# BeagleBone_Blue.net
KiCad netlist of a schematic drawn in EAGLE
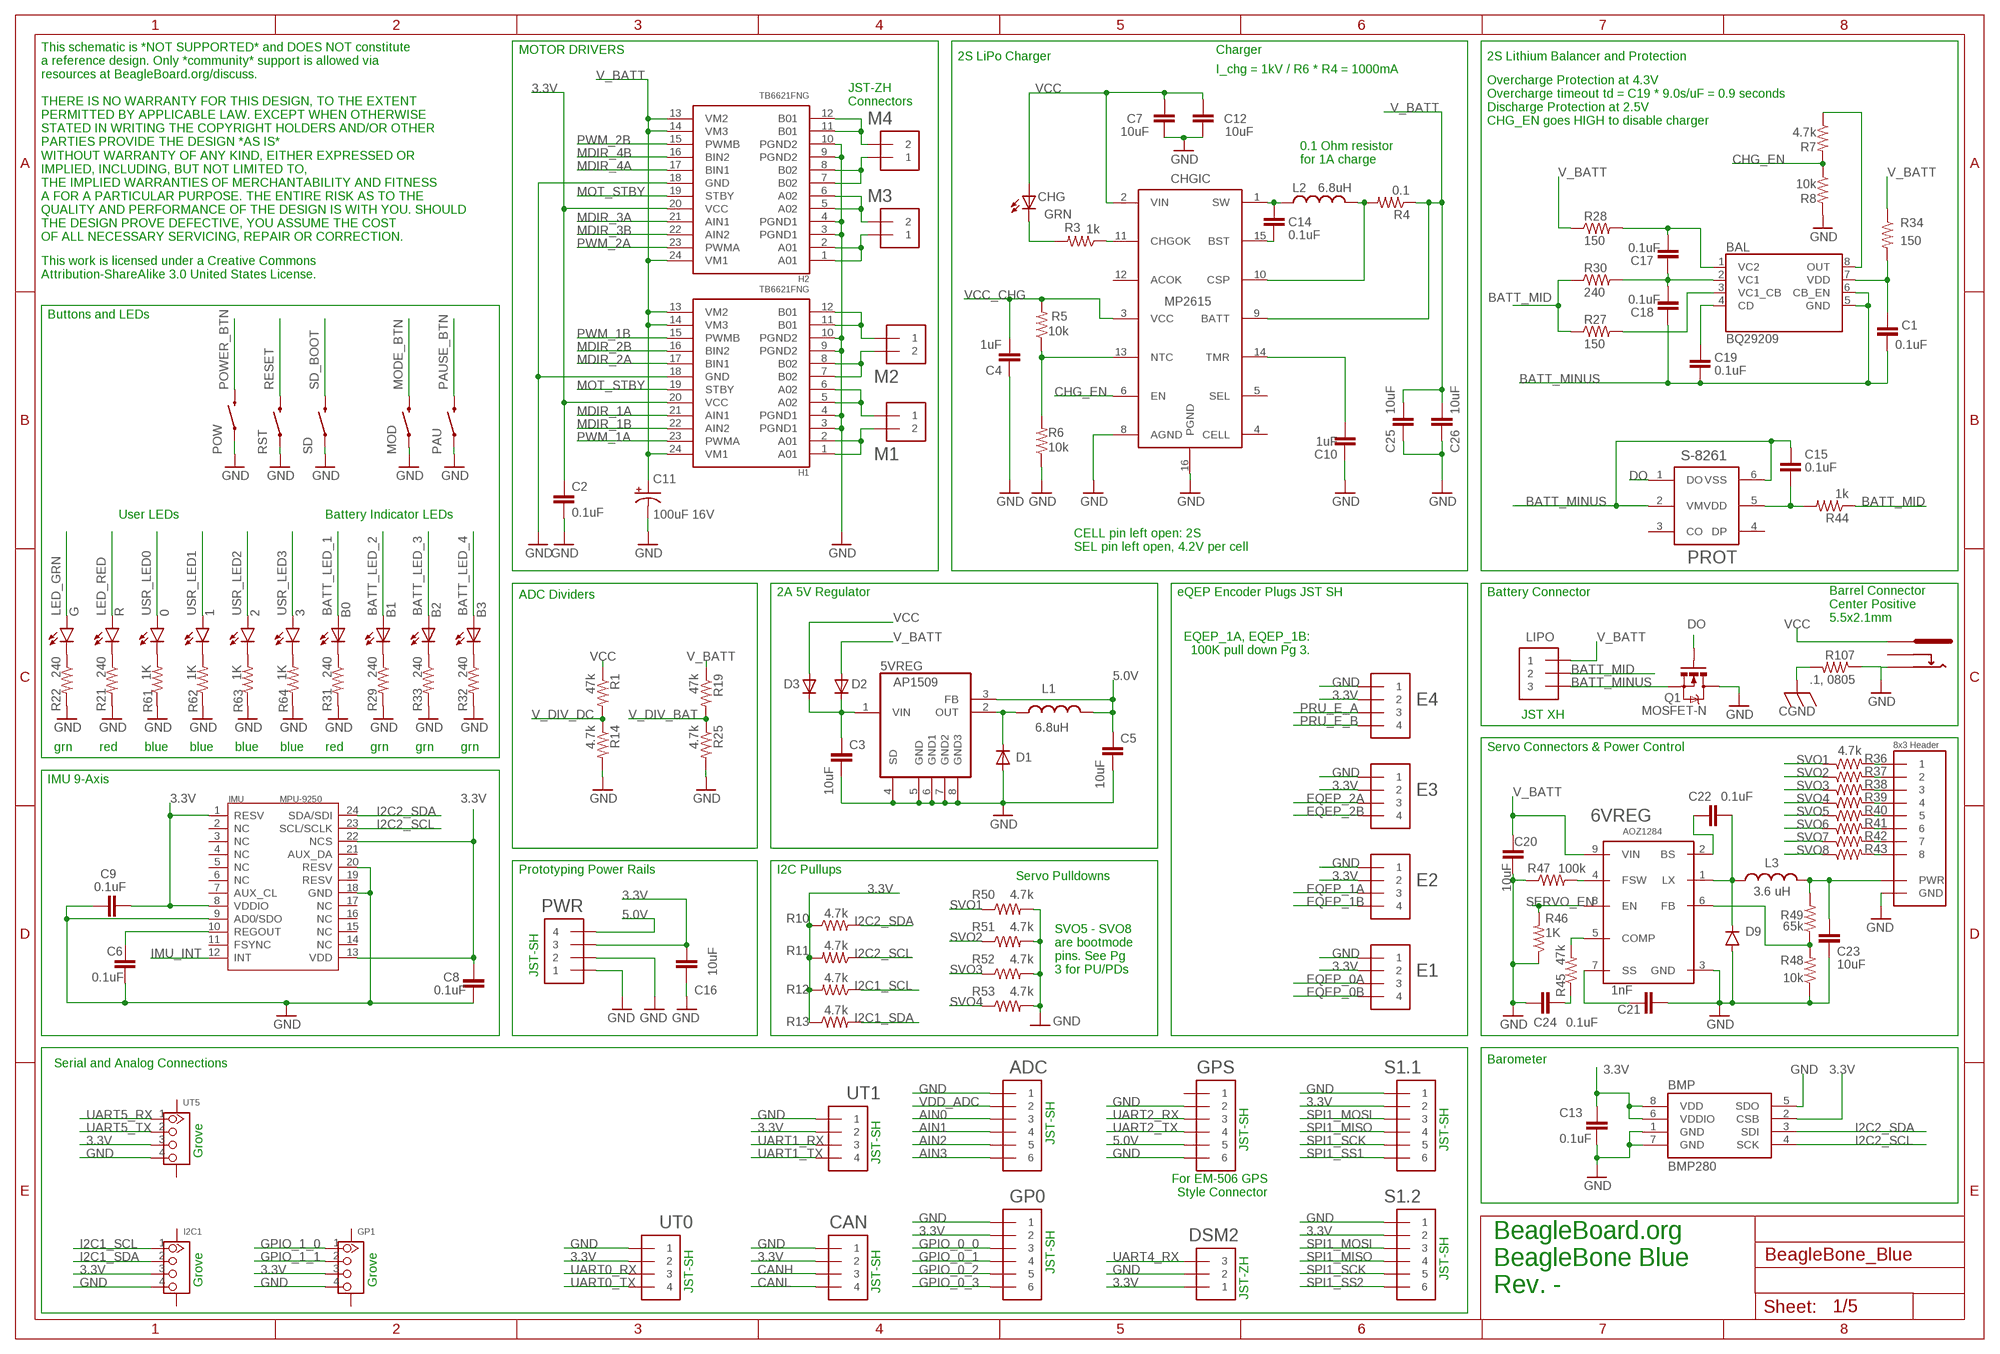
[diagram p0: schematic, sheet 1]
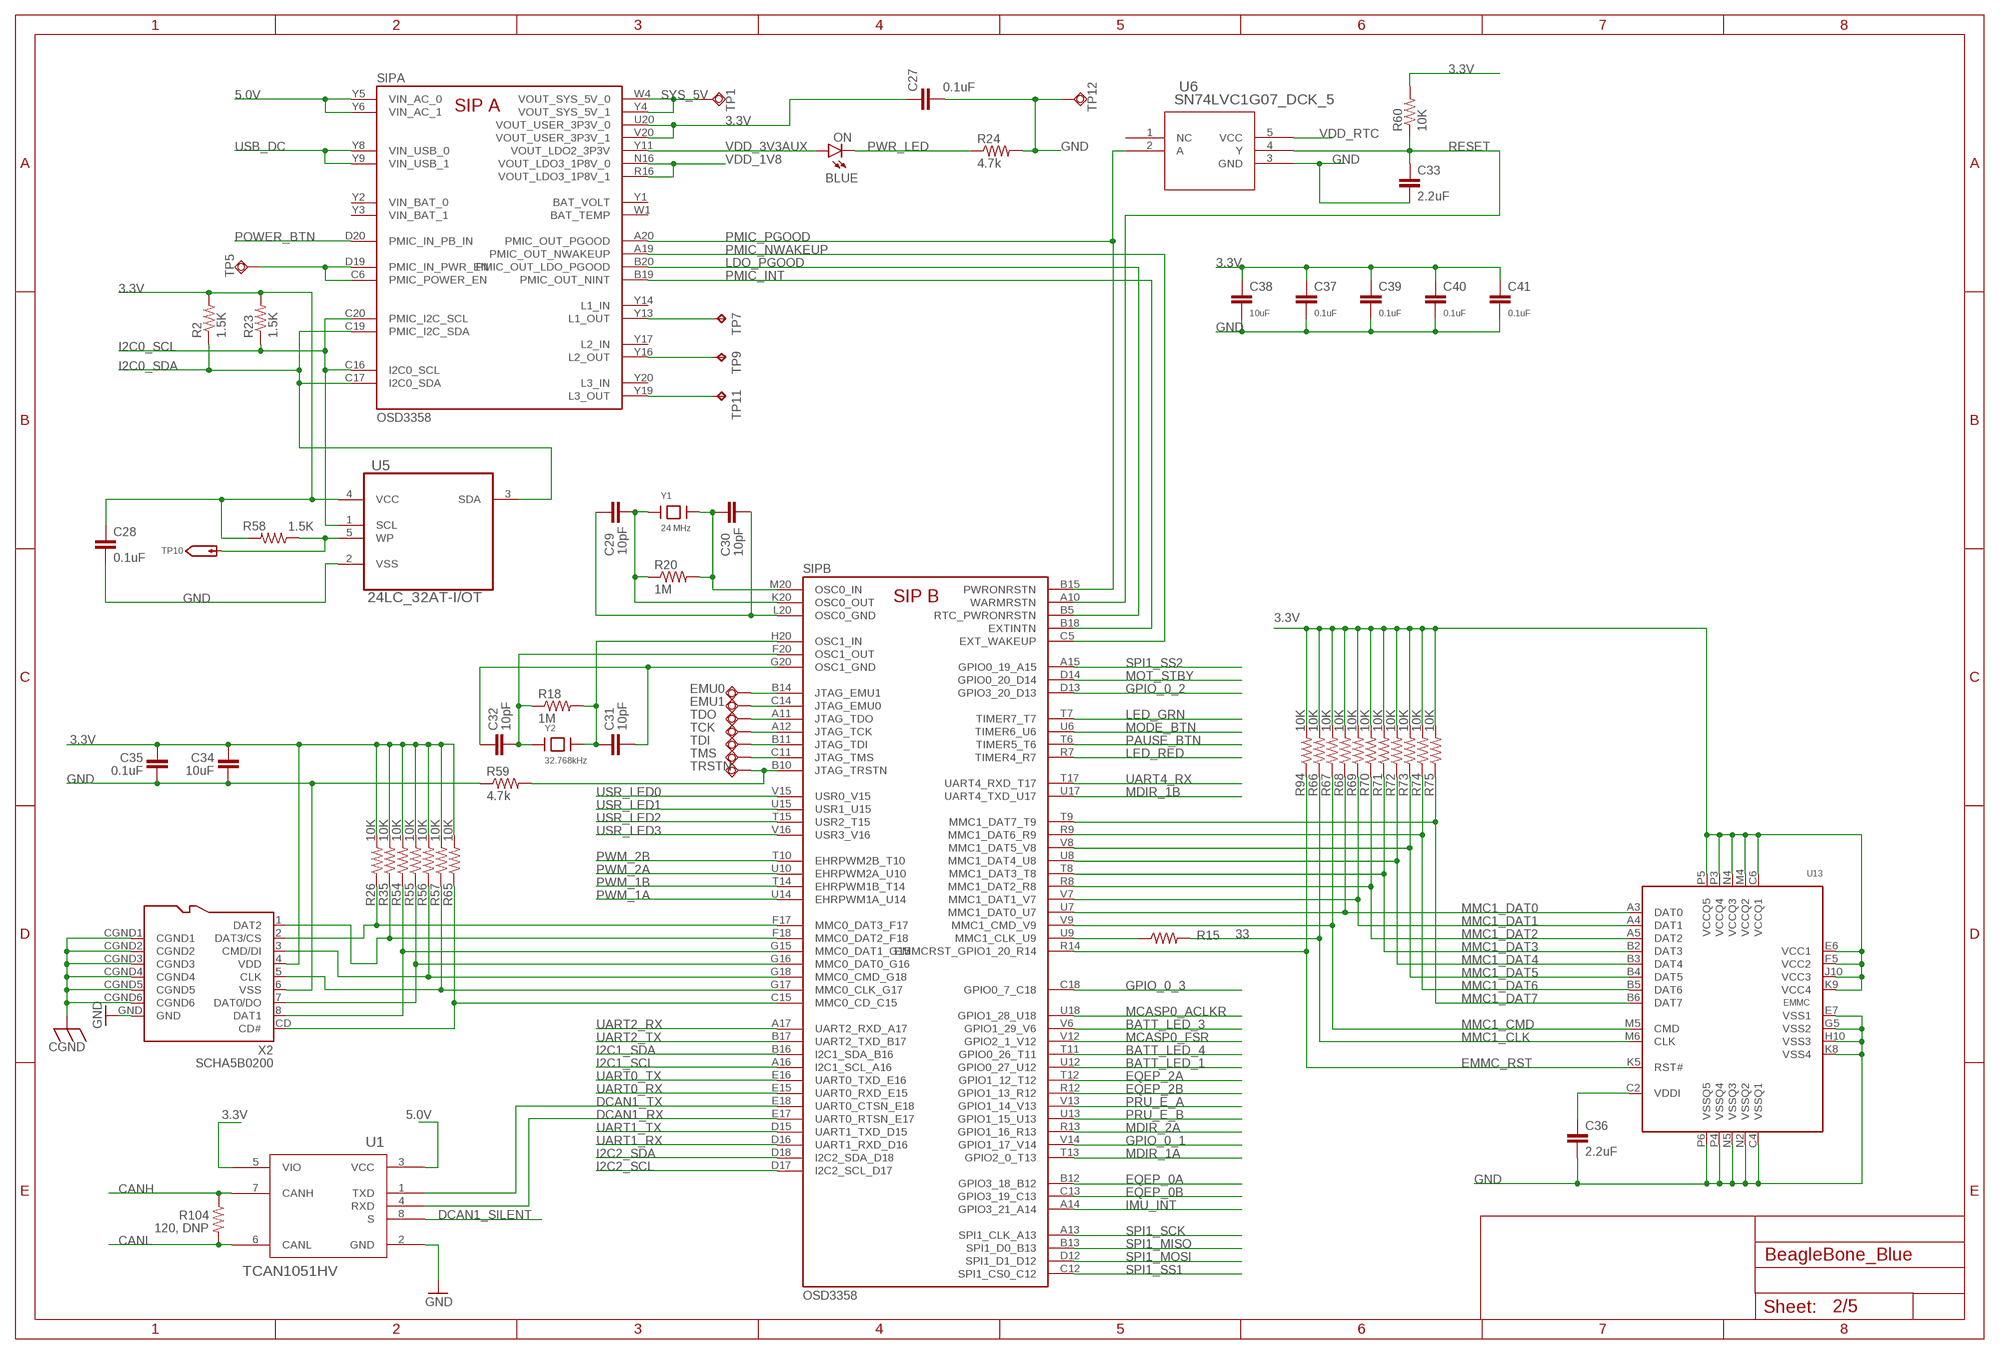
[diagram p1: schematic, sheet 2]
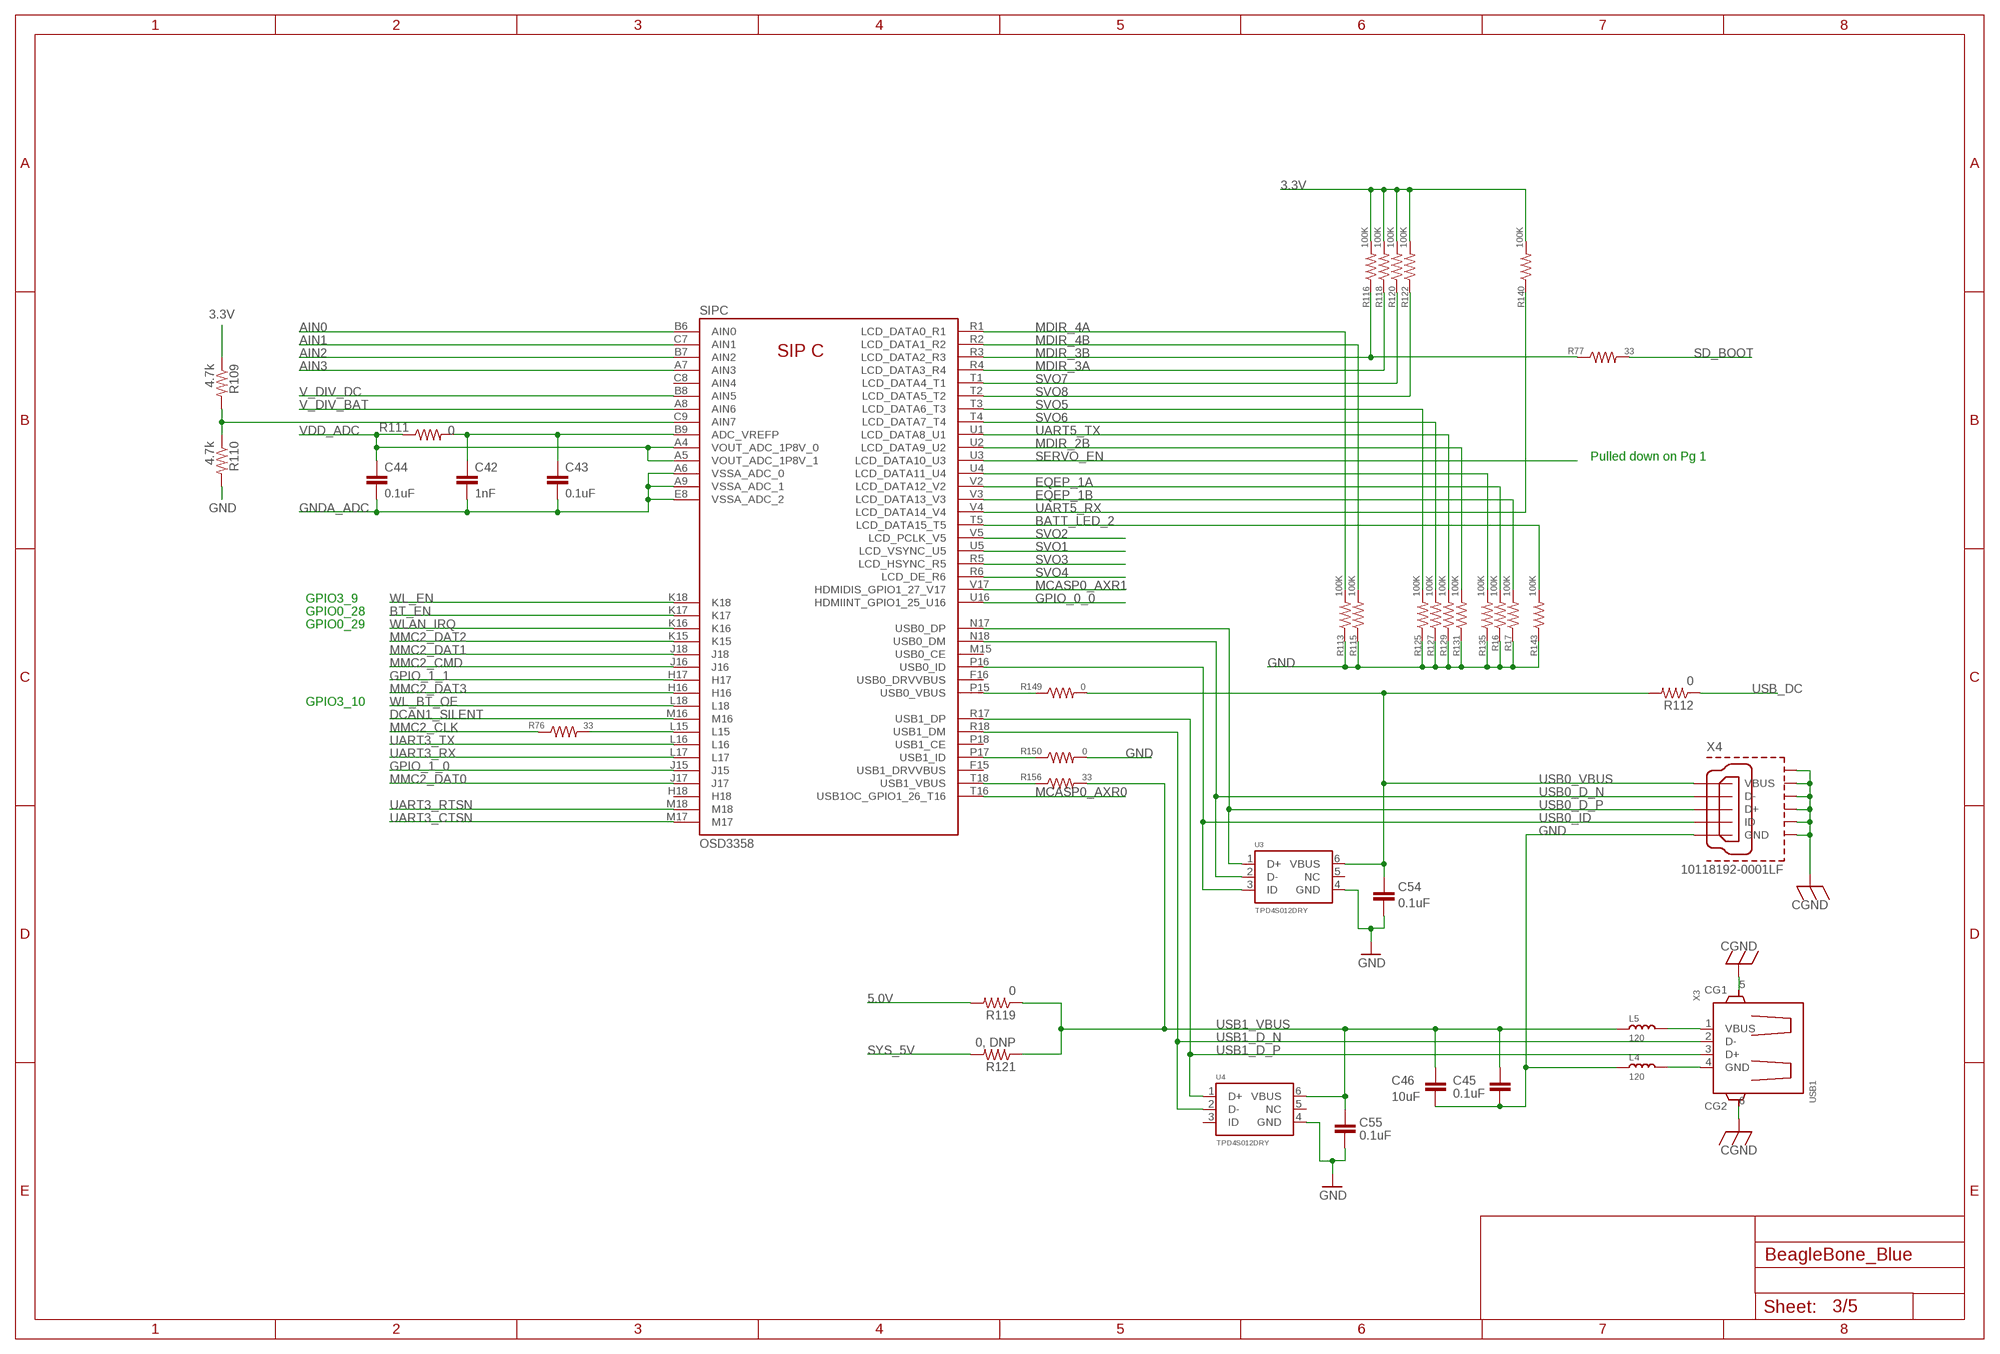
[diagram p2: schematic, sheet 3]
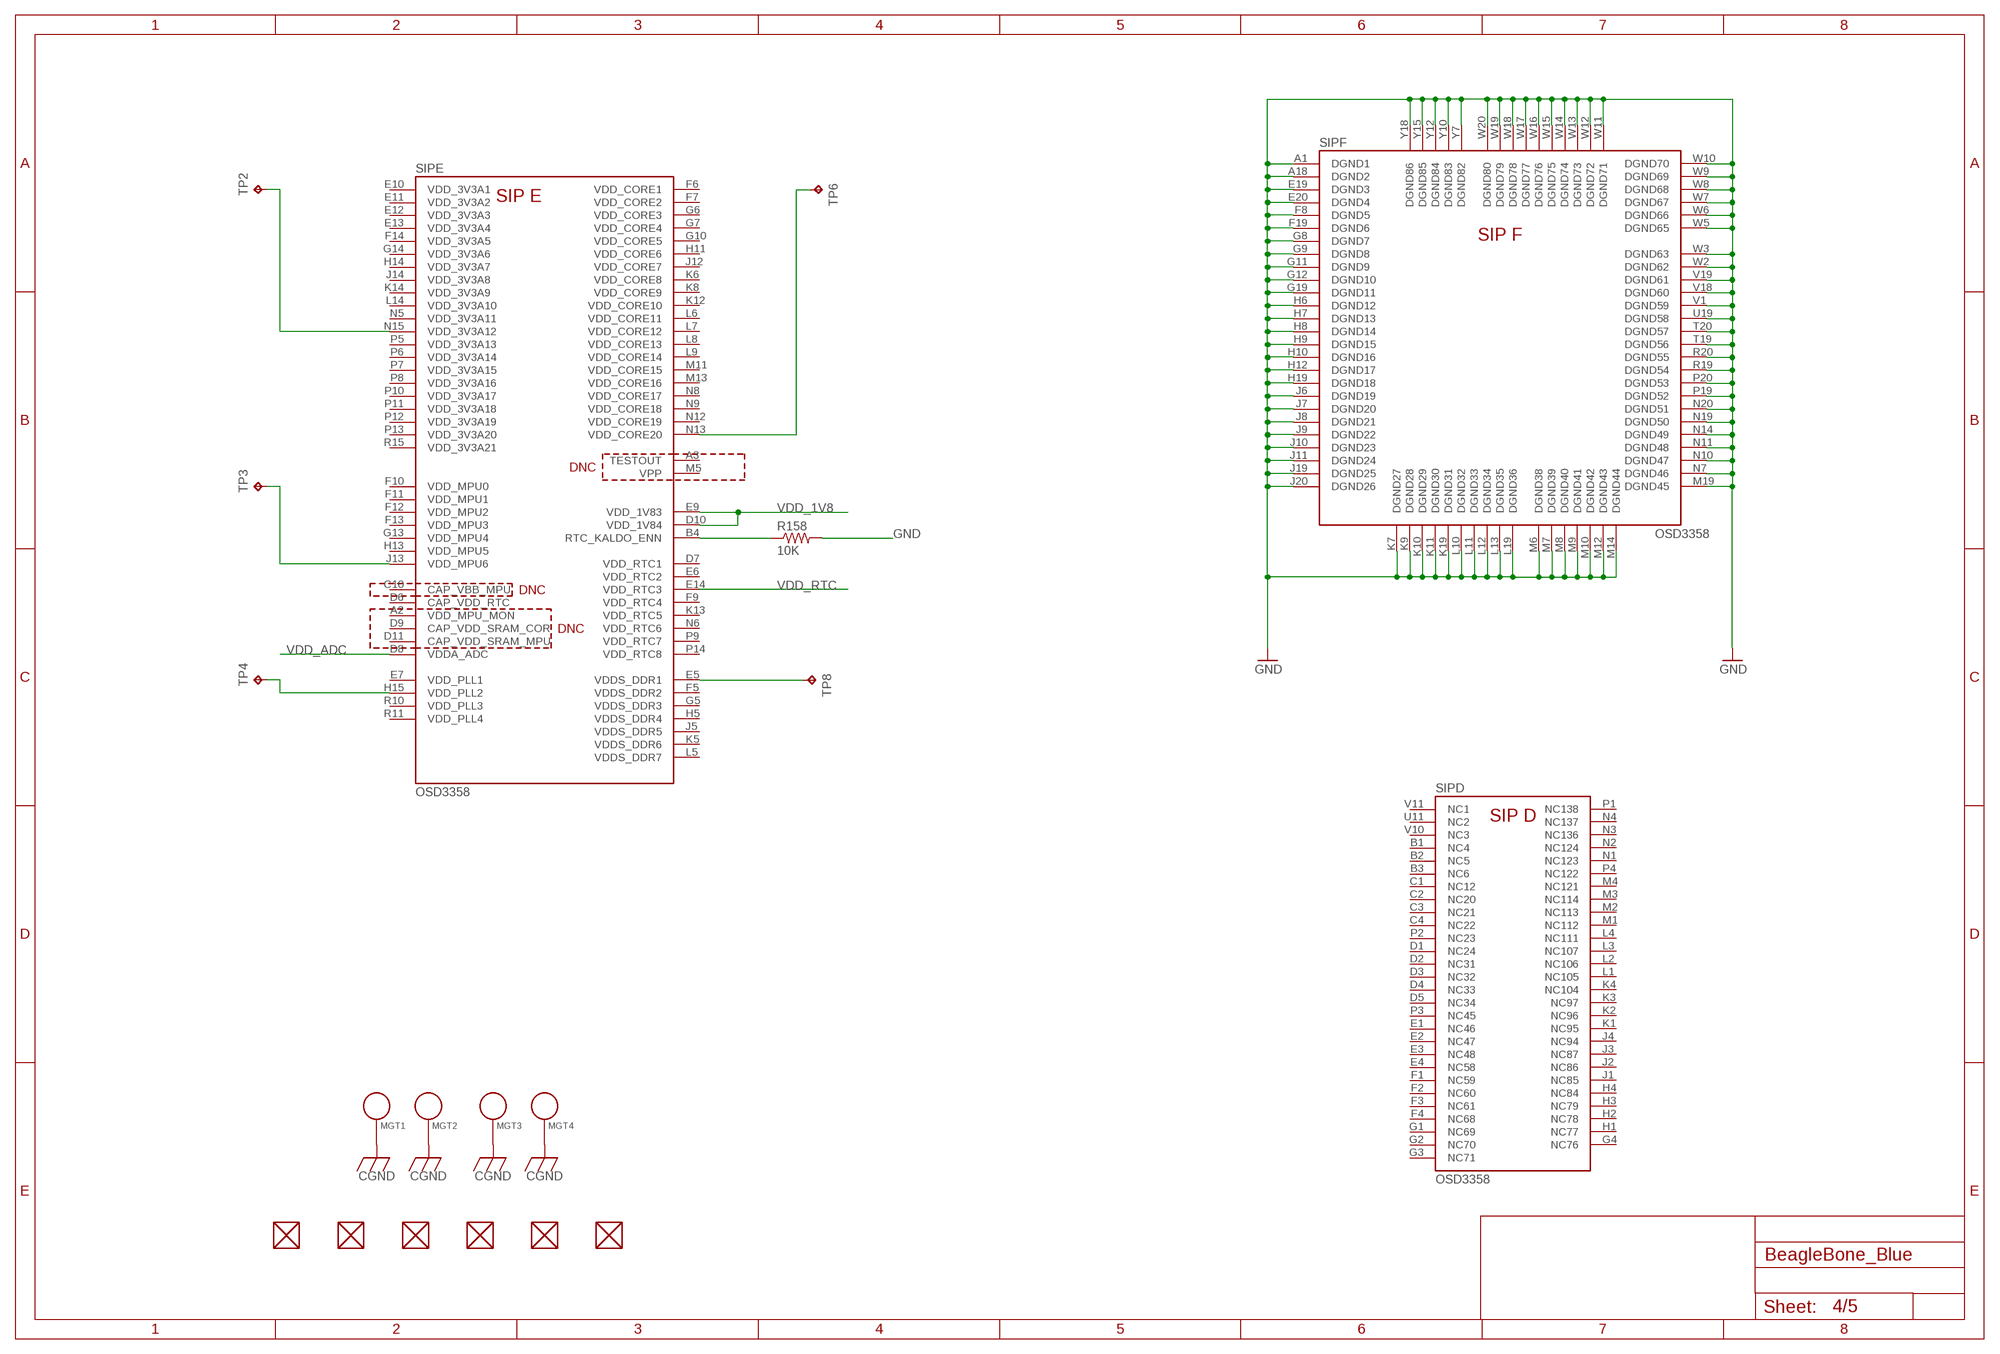
[diagram p3: schematic, sheet 4]
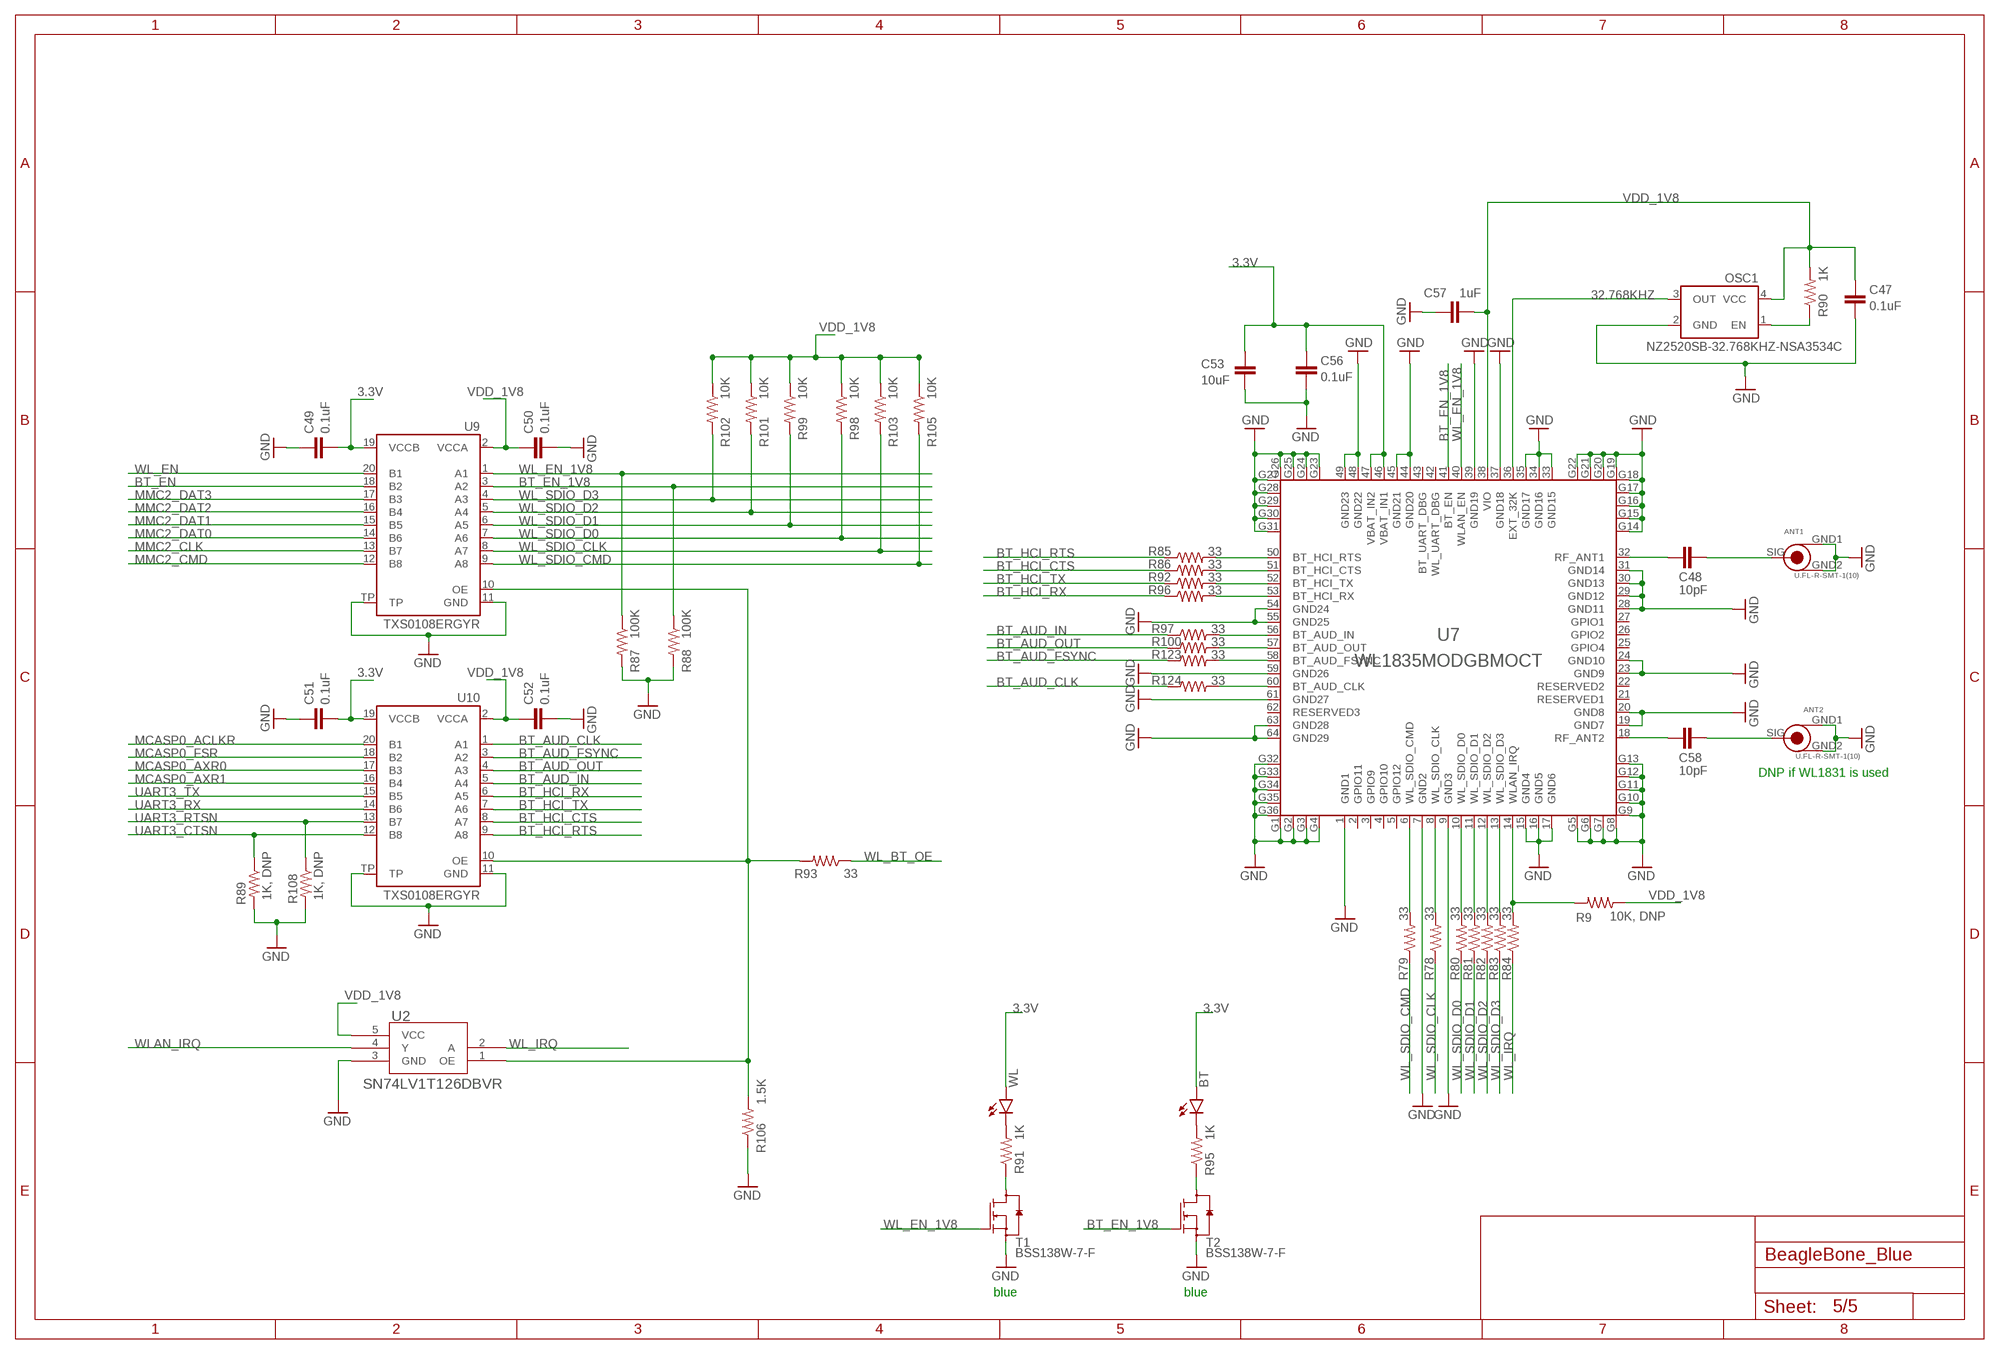
[diagram p4: schematic, sheet 5]

(export (version "E")
  (design (tool "Eeschema 10.0.6"))
  (components
    (comp (ref "0")
      (value "BLUE")
      (footprint "eagle-import:LED-0603")
      (libsource (lib "eagle-import") (part "LED0603"))
    )
    (comp (ref "1")
      (value "BLUE")
      (footprint "eagle-import:LED-0603")
      (libsource (lib "eagle-import") (part "LED0603"))
    )
    (comp (ref "2")
      (value "BLUE")
      (footprint "eagle-import:LED-0603")
      (libsource (lib "eagle-import") (part "LED0603"))
    )
    (comp (ref "3")
      (value "BLUE")
      (footprint "eagle-import:LED-0603")
      (libsource (lib "eagle-import") (part "LED0603"))
    )
    (comp (ref "5VREG")
      (value "AP1509SOIC-8-TIGHT")
      (footprint "eagle-import:SO08-TIGHT")
      (libsource (lib "eagle-import") (part "AP1509SOIC-8-TIGHT"))
    )
    (comp (ref "6VREG")
      (value "AOZ1284")
      (footprint "eagle-import:SO08-EXPOSED")
      (libsource (lib "eagle-import") (part "AOZ1284"))
    )
    (comp (ref "12V")
      (value "PJ-102B_POWER_CON")
      (footprint "eagle-import:PJ-102B_POWER_CON")
      (libsource (lib "eagle-import") (part "PJ-102B_POWER_CON"))
    )
    (comp (ref "ADC")
      (value "JST_SH_6")
      (footprint "eagle-import:JST_SH_6")
      (libsource (lib "eagle-import") (part "JST_SH_6"))
    )
    (comp (ref "B0")
      (value "RED")
      (footprint "eagle-import:LED-0603")
      (libsource (lib "eagle-import") (part "SparkFun-LED_LED0603"))
    )
    (comp (ref "B1")
      (value "GREEN")
      (footprint "eagle-import:LED-0603")
      (libsource (lib "eagle-import") (part "SparkFun-LED_LED0603"))
    )
    (comp (ref "B2")
      (value "GREEN")
      (footprint "eagle-import:LED-0603")
      (libsource (lib "eagle-import") (part "SparkFun-LED_LED0603"))
    )
    (comp (ref "B3")
      (value "GREEN")
      (footprint "eagle-import:LED-0603")
      (libsource (lib "eagle-import") (part "SparkFun-LED_LED0603"))
    )
    (comp (ref "BAL")
      (value "BQ29209")
      (footprint "eagle-import:8-SON_3X3MM")
      (libsource (lib "eagle-import") (part "BQ29209"))
    )
    (comp (ref "BMP")
      (value "BMP280")
      (footprint "eagle-import:BMP280")
      (libsource (lib "eagle-import") (part "BMP280"))
    )
    (comp (ref "C1")
      (value "0.1uF")
      (footprint "eagle-import:0402-CAP")
      (libsource (lib "eagle-import") (part "Strawson_Eagle_Lib_CAP0402-CAP"))
    )
    (comp (ref "C2")
      (value "0.1uF")
      (footprint "eagle-import:0402-CAP")
      (libsource (lib "eagle-import") (part "Strawson_Eagle_Lib_CAP0402-CAP"))
    )
    (comp (ref "C3")
      (value "10uF")
      (footprint "eagle-import:0805")
      (libsource (lib "eagle-import") (part "CAP0805"))
    )
    (comp (ref "C4")
      (value "1uF")
      (footprint "eagle-import:0402-CAP")
      (libsource (lib "eagle-import") (part "Strawson_Eagle_Lib_CAP0402-CAP"))
    )
    (comp (ref "C5")
      (value "10uF")
      (footprint "eagle-import:0805")
      (libsource (lib "eagle-import") (part "CAP0805"))
    )
    (comp (ref "C6")
      (value "0.1uF")
      (footprint "eagle-import:0402-CAP")
      (libsource (lib "eagle-import") (part "Strawson_Eagle_Lib_CAP0402-CAP"))
    )
    (comp (ref "C7")
      (value "10uF")
      (footprint "eagle-import:0805")
      (libsource (lib "eagle-import") (part "CAP0805"))
    )
    (comp (ref "C8")
      (value "0.1uF")
      (footprint "eagle-import:0402-CAP")
      (libsource (lib "eagle-import") (part "Strawson_Eagle_Lib_CAP0402-CAP"))
    )
    (comp (ref "C9")
      (value "0.1uF")
      (footprint "eagle-import:0402-CAP")
      (libsource (lib "eagle-import") (part "Strawson_Eagle_Lib_CAP0402-CAP"))
    )
    (comp (ref "C10")
      (value "1uF")
      (footprint "eagle-import:0402-CAP")
      (libsource (lib "eagle-import") (part "Strawson_Eagle_Lib_CAP0402-CAP"))
    )
    (comp (ref "C11")
      (value "100uF 16V")
      (footprint "eagle-import:PANASONIC_D")
      (libsource (lib "eagle-import") (part "CPOL-USD"))
    )
    (comp (ref "C12")
      (value "10uF")
      (footprint "eagle-import:0805")
      (libsource (lib "eagle-import") (part "CAP0805"))
    )
    (comp (ref "C13")
      (value "0.1uF")
      (footprint "eagle-import:0402-CAP")
      (libsource (lib "eagle-import") (part "Strawson_Eagle_Lib_CAP0402-CAP"))
    )
    (comp (ref "C14")
      (value "0.1uF")
      (footprint "eagle-import:0402-CAP")
      (libsource (lib "eagle-import") (part "Strawson_Eagle_Lib_CAP0402-CAP"))
    )
    (comp (ref "C15")
      (value "0.1uF")
      (footprint "eagle-import:0402-CAP")
      (libsource (lib "eagle-import") (part "Strawson_Eagle_Lib_CAP0402-CAP"))
    )
    (comp (ref "C16")
      (value "10uF")
      (footprint "eagle-import:0805")
      (libsource (lib "eagle-import") (part "CAP0805"))
    )
    (comp (ref "C17")
      (value "0.1uF")
      (footprint "eagle-import:0402-CAP")
      (libsource (lib "eagle-import") (part "Strawson_Eagle_Lib_CAP0402-CAP"))
    )
    (comp (ref "C18")
      (value "0.1uF")
      (footprint "eagle-import:0402-CAP")
      (libsource (lib "eagle-import") (part "Strawson_Eagle_Lib_CAP0402-CAP"))
    )
    (comp (ref "C19")
      (value "0.1uF")
      (footprint "eagle-import:0402-CAP")
      (libsource (lib "eagle-import") (part "Strawson_Eagle_Lib_CAP0402-CAP"))
    )
    (comp (ref "C20")
      (value "10uF")
      (footprint "eagle-import:0805")
      (libsource (lib "eagle-import") (part "CAP0805"))
    )
    (comp (ref "C21")
      (value "1nF")
      (footprint "eagle-import:0402-CAP")
      (libsource (lib "eagle-import") (part "Strawson_Eagle_Lib_CAP0402-CAP"))
    )
    (comp (ref "C22")
      (value "0.1uF")
      (footprint "eagle-import:0402-CAP")
      (libsource (lib "eagle-import") (part "Strawson_Eagle_Lib_CAP0402-CAP"))
    )
    (comp (ref "C23")
      (value "10uF")
      (footprint "eagle-import:0805")
      (libsource (lib "eagle-import") (part "CAP0805"))
    )
    (comp (ref "C24")
      (value "0.1uF")
      (footprint "eagle-import:0402-CAP")
      (libsource (lib "eagle-import") (part "Strawson_Eagle_Lib_CAP0402-CAP"))
    )
    (comp (ref "C25")
      (value "10uF")
      (footprint "eagle-import:0805")
      (libsource (lib "eagle-import") (part "CAP0805"))
    )
    (comp (ref "C26")
      (value "10uF")
      (footprint "eagle-import:0805")
      (libsource (lib "eagle-import") (part "CAP0805"))
    )
    (comp (ref "CAN")
      (value "JST_SH_4")
      (footprint "eagle-import:JST_SH_4_SMD")
      (libsource (lib "eagle-import") (part "JST_SH_4"))
    )
    (comp (ref "CHG")
      (value "GRN")
      (footprint "eagle-import:LED-0603")
      (libsource (lib "eagle-import") (part "SparkFun-LED_LED0603"))
    )
    (comp (ref "CHGIC")
      (value "MP2615")
      (footprint "eagle-import:MP2615")
      (libsource (lib "eagle-import") (part "MP2615"))
    )
    (comp (ref "D1")
      (value "DIODESOD-123")
      (footprint "eagle-import:SOD-123")
      (libsource (lib "eagle-import") (part "DIODESOD-123"))
    )
    (comp (ref "D2")
      (value "DIODESOD-123")
      (footprint "eagle-import:SOD-123")
      (libsource (lib "eagle-import") (part "DIODESOD-123"))
    )
    (comp (ref "D3")
      (value "DIODESOD-123")
      (footprint "eagle-import:SOD-123")
      (libsource (lib "eagle-import") (part "DIODESOD-123"))
    )
    (comp (ref "D9")
      (value "DIODEDO214AA")
      (footprint "eagle-import:DO-214AA")
      (libsource (lib "eagle-import") (part "DIODEDO214AA"))
    )
    (comp (ref "DSM2")
      (value "JST_ZH_3")
      (footprint "eagle-import:JST_ZH_3")
      (libsource (lib "eagle-import") (part "JST_ZH_3"))
    )
    (comp (ref "E1")
      (value "JST_SH_4")
      (footprint "eagle-import:JST_SH_4_SMD")
      (libsource (lib "eagle-import") (part "JST_SH_4"))
    )
    (comp (ref "E2")
      (value "JST_SH_4")
      (footprint "eagle-import:JST_SH_4_SMD")
      (libsource (lib "eagle-import") (part "JST_SH_4"))
    )
    (comp (ref "E3")
      (value "JST_SH_4")
      (footprint "eagle-import:JST_SH_4_SMD")
      (libsource (lib "eagle-import") (part "JST_SH_4"))
    )
    (comp (ref "E4")
      (value "JST_SH_4")
      (footprint "eagle-import:JST_SH_4_SMD")
      (libsource (lib "eagle-import") (part "JST_SH_4"))
    )
    (comp (ref "G")
      (value "GREEN")
      (footprint "eagle-import:LED-0603")
      (libsource (lib "eagle-import") (part "LED0603"))
    )
    (comp (ref "GP0")
      (value "JST_SH_6")
      (footprint "eagle-import:JST_SH_6")
      (libsource (lib "eagle-import") (part "JST_SH_6"))
    )
    (comp (ref "GP1")
      (value "H4P-SMD-2.0")
      (footprint "eagle-import:HW4-SMD-2.0")
      (libsource (lib "eagle-import") (part "GROVE-CONNECTOR-SMD(4+2P-2.0)"))
    )
    (comp (ref "GPS")
      (value "JST_SH_6")
      (footprint "eagle-import:JST_SH_6")
      (libsource (lib "eagle-import") (part "JST_SH_6"))
    )
    (comp (ref "H1")
      (value "TB6621FNG")
      (footprint "eagle-import:SSOP24")
      (libsource (lib "eagle-import") (part "TB6621FNG"))
    )
    (comp (ref "H2")
      (value "TB6621FNG")
      (footprint "eagle-import:SSOP24")
      (libsource (lib "eagle-import") (part "TB6621FNG"))
    )
    (comp (ref "I2C1")
      (value "H4P-SMD-2.0")
      (footprint "eagle-import:HW4-SMD-2.0")
      (libsource (lib "eagle-import") (part "GROVE-CONNECTOR-SMD(4+2P-2.0)"))
    )
    (comp (ref "IMU")
      (value "MPU-9250")
      (footprint "eagle-import:QFN24G-0.4-3X3MM")
      (libsource (lib "eagle-import") (part "MPU-9250"))
    )
    (comp (ref "J2")
      (value "SERVO_HEADERS_8X")
      (footprint "eagle-import:3X8_0.1__HEADER")
      (libsource (lib "eagle-import") (part "SERVO_HEADERS_8X"))
    )
    (comp (ref "L1")
      (value "6.8uH")
      (footprint "eagle-import:SRN6045")
      (libsource (lib "eagle-import") (part "INDUCTORBOURNS_SRN6045"))
    )
    (comp (ref "L2")
      (value "6.8uH")
      (footprint "eagle-import:SRN6045")
      (libsource (lib "eagle-import") (part "INDUCTORBOURNS_SRN6045"))
    )
    (comp (ref "L3")
      (value "3.6 uH")
      (footprint "eagle-import:8X8MM_INDUCTOR")
      (libsource (lib "eagle-import") (part "INDUCTOR"))
    )
    (comp (ref "LIPO")
      (value "BATTERY")
      (footprint "eagle-import:JST_XH_3-PIN")
      (libsource (lib "eagle-import") (part "JST_XH_3-PIN"))
    )
    (comp (ref "M1")
      (value "JST_ZH_2")
      (footprint "eagle-import:JST_ZH_2")
      (libsource (lib "eagle-import") (part "JST_ZH_2"))
    )
    (comp (ref "M2")
      (value "JST_ZH_2")
      (footprint "eagle-import:JST_ZH_2")
      (libsource (lib "eagle-import") (part "JST_ZH_2"))
    )
    (comp (ref "M3")
      (value "JST_ZH_2")
      (footprint "eagle-import:JST_ZH_2")
      (libsource (lib "eagle-import") (part "JST_ZH_2"))
    )
    (comp (ref "M4")
      (value "JST_ZH_2")
      (footprint "eagle-import:JST_ZH_2")
      (libsource (lib "eagle-import") (part "JST_ZH_2"))
    )
    (comp (ref "MOD")
      (value "SWITCH-MOMENTARY-2SMD-1101NE")
      (footprint "eagle-import:TACTILE-SWITCH-1101NE")
      (libsource (lib "eagle-import") (part "SWITCH-MOMENTARY-2SMD-1101NE"))
    )
    (comp (ref "PAU")
      (value "SWITCH-MOMENTARY-2SMD-1101NE")
      (footprint "eagle-import:TACTILE-SWITCH-1101NE")
      (libsource (lib "eagle-import") (part "SWITCH-MOMENTARY-2SMD-1101NE"))
    )
    (comp (ref "POW")
      (value "SWITCH-MOMENTARY-2SMD-1101NE")
      (footprint "eagle-import:TACTILE-SWITCH-1101NE")
      (libsource (lib "eagle-import") (part "SWITCH-MOMENTARY-2SMD-1101NE"))
    )
    (comp (ref "PROT")
      (value "S-8261")
      (footprint "eagle-import:SOT-236")
      (libsource (lib "eagle-import") (part "S-8261"))
    )
    (comp (ref "PWR")
      (value "JST_SH_4")
      (footprint "eagle-import:JST_SH_4_SMD")
      (libsource (lib "eagle-import") (part "JST_SH_4"))
    )
    (comp (ref "Q1")
      (value "MOSFET-N")
      (footprint "eagle-import:SO08-TIGHT")
      (libsource (lib "eagle-import") (part "MOSFET-NCHANNEL"))
    )
    (comp (ref "R")
      (value "RED")
      (footprint "eagle-import:LED-0603")
      (libsource (lib "eagle-import") (part "LED0603"))
    )
    (comp (ref "R1")
      (value "47k")
      (footprint "eagle-import:0402-RES")
      (libsource (lib "eagle-import") (part "RESISTOR0402-RES"))
    )
    (comp (ref "R3")
      (value "1k")
      (footprint "eagle-import:0402-RES")
      (libsource (lib "eagle-import") (part "RESISTOR0402-RES"))
    )
    (comp (ref "R4")
      (value "0.1")
      (footprint "eagle-import:0603-RES")
      (libsource (lib "eagle-import") (part "RESISTOR0603"))
    )
    (comp (ref "R5")
      (value "10k")
      (footprint "eagle-import:0402-RES")
      (libsource (lib "eagle-import") (part "RESISTOR0402-RES"))
    )
    (comp (ref "R6")
      (value "10k")
      (footprint "eagle-import:0402-RES")
      (libsource (lib "eagle-import") (part "RESISTOR0402-RES"))
    )
    (comp (ref "R7")
      (value "4.7k")
      (footprint "eagle-import:0402-RES")
      (libsource (lib "eagle-import") (part "RESISTOR0402-RES"))
    )
    (comp (ref "R8")
      (value "10k")
      (footprint "eagle-import:0402-RES")
      (libsource (lib "eagle-import") (part "RESISTOR0402-RES"))
    )
    (comp (ref "R10")
      (value "4.7k")
      (footprint "eagle-import:0402-RES")
      (libsource (lib "eagle-import") (part "RESISTOR0402-RES"))
    )
    (comp (ref "R11")
      (value "4.7k")
      (footprint "eagle-import:0402-RES")
      (libsource (lib "eagle-import") (part "RESISTOR0402-RES"))
    )
    (comp (ref "R12")
      (value "4.7k")
      (footprint "eagle-import:0402-RES")
      (libsource (lib "eagle-import") (part "RESISTOR0402-RES"))
    )
    (comp (ref "R13")
      (value "4.7k")
      (footprint "eagle-import:0402-RES")
      (libsource (lib "eagle-import") (part "RESISTOR0402-RES"))
    )
    (comp (ref "R14")
      (value "4.7k")
      (footprint "eagle-import:0402-RES")
      (libsource (lib "eagle-import") (part "RESISTOR0402-RES"))
    )
    (comp (ref "R19")
      (value "47k")
      (footprint "eagle-import:0402-RES")
      (libsource (lib "eagle-import") (part "RESISTOR0402-RES"))
    )
    (comp (ref "R21")
      (value "240")
      (footprint "eagle-import:0402-RES")
      (libsource (lib "eagle-import") (part "RESISTOR0402-RES"))
    )
    (comp (ref "R22")
      (value "240")
      (footprint "eagle-import:0402-RES")
      (libsource (lib "eagle-import") (part "RESISTOR0402-RES"))
    )
    (comp (ref "R25")
      (value "4.7k")
      (footprint "eagle-import:0402-RES")
      (libsource (lib "eagle-import") (part "RESISTOR0402-RES"))
    )
    (comp (ref "R27")
      (value "150")
      (footprint "eagle-import:0402-RES")
      (libsource (lib "eagle-import") (part "RESISTOR0402-RES"))
    )
    (comp (ref "R28")
      (value "150")
      (footprint "eagle-import:0402-RES")
      (libsource (lib "eagle-import") (part "RESISTOR0402-RES"))
    )
    (comp (ref "R29")
      (value "240")
      (footprint "eagle-import:0402-RES")
      (libsource (lib "eagle-import") (part "RESISTOR0402-RES"))
    )
    (comp (ref "R30")
      (value "240")
      (footprint "eagle-import:0402-RES")
      (libsource (lib "eagle-import") (part "RESISTOR0402-RES"))
    )
    (comp (ref "R31")
      (value "240")
      (footprint "eagle-import:0402-RES")
      (libsource (lib "eagle-import") (part "RESISTOR0402-RES"))
    )
    (comp (ref "R32")
      (value "240")
      (footprint "eagle-import:0402-RES")
      (libsource (lib "eagle-import") (part "RESISTOR0402-RES"))
    )
    (comp (ref "R33")
      (value "240")
      (footprint "eagle-import:0402-RES")
      (libsource (lib "eagle-import") (part "RESISTOR0402-RES"))
    )
    (comp (ref "R34")
      (value "150")
      (footprint "eagle-import:0402-RES")
      (libsource (lib "eagle-import") (part "RESISTOR0402-RES"))
    )
    (comp (ref "R36")
      (value "4.7k")
      (footprint "eagle-import:0402-RES")
      (libsource (lib "eagle-import") (part "RESISTOR0402-RES"))
    )
    (comp (ref "R37")
      (value "4.7k")
      (footprint "eagle-import:0402-RES")
      (libsource (lib "eagle-import") (part "RESISTOR0402-RES"))
    )
    (comp (ref "R38")
      (value "4.7k")
      (footprint "eagle-import:0402-RES")
      (libsource (lib "eagle-import") (part "RESISTOR0402-RES"))
    )
    (comp (ref "R39")
      (value "4.7k")
      (footprint "eagle-import:0402-RES")
      (libsource (lib "eagle-import") (part "RESISTOR0402-RES"))
    )
    (comp (ref "R40")
      (value "4.7k")
      (footprint "eagle-import:0402-RES")
      (libsource (lib "eagle-import") (part "RESISTOR0402-RES"))
    )
    (comp (ref "R41")
      (value "4.7k")
      (footprint "eagle-import:0402-RES")
      (libsource (lib "eagle-import") (part "RESISTOR0402-RES"))
    )
    (comp (ref "R42")
      (value "4.7k")
      (footprint "eagle-import:0402-RES")
      (libsource (lib "eagle-import") (part "RESISTOR0402-RES"))
    )
    (comp (ref "R43")
      (value "4.7k")
      (footprint "eagle-import:0402-RES")
      (libsource (lib "eagle-import") (part "RESISTOR0402-RES"))
    )
    (comp (ref "R44")
      (value "1k")
      (footprint "eagle-import:0402-RES")
      (libsource (lib "eagle-import") (part "RESISTOR0402-RES"))
    )
    (comp (ref "R45")
      (value "47k")
      (footprint "eagle-import:0402-RES")
      (libsource (lib "eagle-import") (part "RESISTOR0402-RES"))
    )
    (comp (ref "R46")
      (value "1K")
      (footprint "eagle-import:0402-RES")
      (libsource (lib "eagle-import") (part "RESISTOR0402-RES"))
    )
    (comp (ref "R47")
      (value "100k")
      (footprint "eagle-import:0402-RES")
      (libsource (lib "eagle-import") (part "RESISTOR0402-RES"))
    )
    (comp (ref "R48")
      (value "10k")
      (footprint "eagle-import:0402-RES")
      (libsource (lib "eagle-import") (part "RESISTOR0402-RES"))
    )
    (comp (ref "R49")
      (value "65k")
      (footprint "eagle-import:0402-RES")
      (libsource (lib "eagle-import") (part "RESISTOR0402-RES"))
    )
    (comp (ref "R50")
      (value "4.7k")
      (footprint "eagle-import:0402-RES")
      (libsource (lib "eagle-import") (part "RESISTOR0402-RES"))
    )
    (comp (ref "R51")
      (value "4.7k")
      (footprint "eagle-import:0402-RES")
      (libsource (lib "eagle-import") (part "RESISTOR0402-RES"))
    )
    (comp (ref "R52")
      (value "4.7k")
      (footprint "eagle-import:0402-RES")
      (libsource (lib "eagle-import") (part "RESISTOR0402-RES"))
    )
    (comp (ref "R53")
      (value "4.7k")
      (footprint "eagle-import:0402-RES")
      (libsource (lib "eagle-import") (part "RESISTOR0402-RES"))
    )
    (comp (ref "R61")
      (value "1K")
      (footprint "eagle-import:0402-RES")
      (libsource (lib "eagle-import") (part "RESISTOR0402-RES"))
    )
    (comp (ref "R62")
      (value "1K")
      (footprint "eagle-import:0402-RES")
      (libsource (lib "eagle-import") (part "RESISTOR0402-RES"))
    )
    (comp (ref "R63")
      (value "1K")
      (footprint "eagle-import:0402-RES")
      (libsource (lib "eagle-import") (part "RESISTOR0402-RES"))
    )
    (comp (ref "R64")
      (value "1K")
      (footprint "eagle-import:0402-RES")
      (libsource (lib "eagle-import") (part "RESISTOR0402-RES"))
    )
    (comp (ref "R107")
      (value ".1, 0805")
      (footprint "eagle-import:R0805")
      (libsource (lib "eagle-import") (part "R-US_R0805"))
    )
    (comp (ref "RST")
      (value "SWITCH-MOMENTARY-2SMD-1101NE")
      (footprint "eagle-import:TACTILE-SWITCH-1101NE")
      (libsource (lib "eagle-import") (part "SWITCH-MOMENTARY-2SMD-1101NE"))
    )
    (comp (ref "S1.1")
      (value "JST_SH_6")
      (footprint "eagle-import:JST_SH_6")
      (libsource (lib "eagle-import") (part "JST_SH_6"))
    )
    (comp (ref "S1.2")
      (value "JST_SH_6")
      (footprint "eagle-import:JST_SH_6")
      (libsource (lib "eagle-import") (part "JST_SH_6"))
    )
    (comp (ref "SD")
      (value "SWITCH-MOMENTARY-2SMD-1101NE")
      (footprint "eagle-import:TACTILE-SWITCH-1101NE")
      (libsource (lib "eagle-import") (part "SWITCH-MOMENTARY-2SMD-1101NE"))
    )
    (comp (ref "UT0")
      (value "JST_SH_4")
      (footprint "eagle-import:JST_SH_4_SMD")
      (libsource (lib "eagle-import") (part "JST_SH_4"))
    )
    (comp (ref "UT1")
      (value "JST_SH_4")
      (footprint "eagle-import:JST_SH_4_SMD")
      (libsource (lib "eagle-import") (part "JST_SH_4"))
    )
    (comp (ref "UT5")
      (value "H4P-SMD-2.0")
      (footprint "eagle-import:HW4-SMD-2.0")
      (libsource (lib "eagle-import") (part "GROVE-CONNECTOR-SMD(4+2P-2.0)"))
    )
    (comp (ref "FUD1")
      (value "FIDUCIAL")
      (footprint "eagle-import:FIDUCIAL_40MIL")
      (libsource (lib "eagle-import") (part "FIDUCIAL"))
    )
    (comp (ref "FUD2")
      (value "FIDUCIAL")
      (footprint "eagle-import:FIDUCIAL_40MIL")
      (libsource (lib "eagle-import") (part "FIDUCIAL"))
    )
    (comp (ref "FUD3")
      (value "FIDUCIAL")
      (footprint "eagle-import:FIDUCIAL_40MIL")
      (libsource (lib "eagle-import") (part "FIDUCIAL"))
    )
    (comp (ref "FUD4")
      (value "FIDUCIAL")
      (footprint "eagle-import:FIDUCIAL_40MIL")
      (libsource (lib "eagle-import") (part "FIDUCIAL"))
    )
    (comp (ref "FUD5")
      (value "FIDUCIAL")
      (footprint "eagle-import:FIDUCIAL_40MIL")
      (libsource (lib "eagle-import") (part "FIDUCIAL"))
    )
    (comp (ref "FUD6")
      (value "FIDUCIAL")
      (footprint "eagle-import:FIDUCIAL_40MIL")
      (libsource (lib "eagle-import") (part "FIDUCIAL"))
    )
    (comp (ref "MGT1")
      (value "MOUNTING_HOLE")
      (footprint "eagle-import:MOUNTING_HOLE")
      (libsource (lib "eagle-import") (part "MOUNTING_HOLE"))
    )
    (comp (ref "MGT2")
      (value "MOUNTING_HOLE")
      (footprint "eagle-import:MOUNTING_HOLE")
      (libsource (lib "eagle-import") (part "MOUNTING_HOLE"))
    )
    (comp (ref "MGT3")
      (value "MOUNTING_HOLE")
      (footprint "eagle-import:MOUNTING_HOLE")
      (libsource (lib "eagle-import") (part "MOUNTING_HOLE"))
    )
    (comp (ref "MGT4")
      (value "MOUNTING_HOLE")
      (footprint "eagle-import:MOUNTING_HOLE")
      (libsource (lib "eagle-import") (part "MOUNTING_HOLE"))
    )
    (comp (ref "R158")
      (value "10K")
      (footprint "eagle-import:0402-RES")
      (libsource (lib "eagle-import") (part "RESISTOR0402-RES"))
    )
    (comp (ref "SIP")
      (value "OSD3358")
      (footprint "eagle-import:OSD3358")
      (libsource (lib "eagle-import") (part "OSD3358"))
    )
    (comp (ref "TP2")
      (value "TPB0,65")
      (footprint "eagle-import:B0,65")
      (libsource (lib "eagle-import") (part "TPB0,65"))
    )
    (comp (ref "TP3")
      (value "TPB0,65")
      (footprint "eagle-import:B0,65")
      (libsource (lib "eagle-import") (part "TPB0,65"))
    )
    (comp (ref "TP4")
      (value "TPB0,65")
      (footprint "eagle-import:B0,65")
      (libsource (lib "eagle-import") (part "TPB0,65"))
    )
    (comp (ref "TP6")
      (value "TPB0,65")
      (footprint "eagle-import:B0,65")
      (libsource (lib "eagle-import") (part "TPB0,65"))
    )
    (comp (ref "TP8")
      (value "TPB0,65")
      (footprint "eagle-import:B0,65")
      (libsource (lib "eagle-import") (part "TPB0,65"))
    )
    (comp (ref "C27")
      (value "0.1uF")
      (footprint "eagle-import:0402-CAP")
      (libsource (lib "eagle-import") (part "Strawson_Eagle_Lib_CAP0402-CAP"))
    )
    (comp (ref "C28")
      (value "0.1uF")
      (footprint "eagle-import:0402-CAP")
      (libsource (lib "eagle-import") (part "Strawson_Eagle_Lib_CAP0402-CAP"))
    )
    (comp (ref "C29")
      (value "10pF")
      (footprint "eagle-import:0402-CAP")
      (libsource (lib "eagle-import") (part "Strawson_Eagle_Lib_CAP0402-CAP"))
    )
    (comp (ref "C30")
      (value "10pF")
      (footprint "eagle-import:0402-CAP")
      (libsource (lib "eagle-import") (part "Strawson_Eagle_Lib_CAP0402-CAP"))
    )
    (comp (ref "C31")
      (value "10pF")
      (footprint "eagle-import:0402-CAP")
      (libsource (lib "eagle-import") (part "Strawson_Eagle_Lib_CAP0402-CAP"))
    )
    (comp (ref "C32")
      (value "10pF")
      (footprint "eagle-import:0402-CAP")
      (libsource (lib "eagle-import") (part "Strawson_Eagle_Lib_CAP0402-CAP"))
    )
    (comp (ref "C33")
      (value "2.2uF")
      (footprint "eagle-import:0402-CAP")
      (libsource (lib "eagle-import") (part "Strawson_Eagle_Lib_CAP0402-CAP"))
    )
    (comp (ref "C34")
      (value "10uF")
      (footprint "eagle-import:0805")
      (libsource (lib "eagle-import") (part "Strawson_Eagle_Lib_CAP0805"))
    )
    (comp (ref "C35")
      (value "0.1uF")
      (footprint "eagle-import:0402-CAP")
      (libsource (lib "eagle-import") (part "Strawson_Eagle_Lib_CAP0402-CAP"))
    )
    (comp (ref "C36")
      (value "2.2uF")
      (footprint "eagle-import:0402-CAP")
      (libsource (lib "eagle-import") (part "Strawson_Eagle_Lib_CAP0402-CAP"))
    )
    (comp (ref "C37")
      (value "0.1uF")
      (footprint "eagle-import:0402-CAP")
      (libsource (lib "eagle-import") (part "Strawson_Eagle_Lib_CAP0402-CAP"))
    )
    (comp (ref "C38")
      (value "10uF")
      (footprint "eagle-import:0805")
      (libsource (lib "eagle-import") (part "Strawson_Eagle_Lib_CAP0805"))
    )
    (comp (ref "C39")
      (value "0.1uF")
      (footprint "eagle-import:0402-CAP")
      (libsource (lib "eagle-import") (part "Strawson_Eagle_Lib_CAP0402-CAP"))
    )
    (comp (ref "C40")
      (value "0.1uF")
      (footprint "eagle-import:0402-CAP")
      (libsource (lib "eagle-import") (part "Strawson_Eagle_Lib_CAP0402-CAP"))
    )
    (comp (ref "C41")
      (value "0.1uF")
      (footprint "eagle-import:0402-CAP")
      (libsource (lib "eagle-import") (part "Strawson_Eagle_Lib_CAP0402-CAP"))
    )
    (comp (ref "EMU0")
      (value "TPSQB1,27")
      (footprint "eagle-import:B1,27")
      (libsource (lib "eagle-import") (part "TPSQB1,27"))
    )
    (comp (ref "EMU1")
      (value "TPSQB1,27")
      (footprint "eagle-import:B1,27")
      (libsource (lib "eagle-import") (part "TPSQB1,27"))
    )
    (comp (ref "ON")
      (value "BLUE")
      (footprint "eagle-import:LED-0603")
      (libsource (lib "eagle-import") (part "LED0603"))
    )
    (comp (ref "R2")
      (value "1.5K")
      (footprint "eagle-import:0402-RES")
      (libsource (lib "eagle-import") (part "RESISTOR0402-RES"))
    )
    (comp (ref "R15")
      (value "33")
      (footprint "eagle-import:0402-RES")
      (libsource (lib "eagle-import") (part "RESISTOR0402-RES"))
    )
    (comp (ref "R18")
      (value "1M")
      (footprint "eagle-import:0402-RES")
      (libsource (lib "eagle-import") (part "RESISTOR0402-RES"))
    )
    (comp (ref "R20")
      (value "1M")
      (footprint "eagle-import:0402-RES")
      (libsource (lib "eagle-import") (part "RESISTOR0402-RES"))
    )
    (comp (ref "R23")
      (value "1.5K")
      (footprint "eagle-import:0402-RES")
      (libsource (lib "eagle-import") (part "RESISTOR0402-RES"))
    )
    (comp (ref "R24")
      (value "4.7k")
      (footprint "eagle-import:0402-RES")
      (libsource (lib "eagle-import") (part "RESISTOR0402-RES"))
    )
    (comp (ref "R26")
      (value "10K")
      (footprint "eagle-import:0402-RES")
      (libsource (lib "eagle-import") (part "RESISTOR0402-RES"))
    )
    (comp (ref "R35")
      (value "10K")
      (footprint "eagle-import:0402-RES")
      (libsource (lib "eagle-import") (part "RESISTOR0402-RES"))
    )
    (comp (ref "R54")
      (value "10K")
      (footprint "eagle-import:0402-RES")
      (libsource (lib "eagle-import") (part "RESISTOR0402-RES"))
    )
    (comp (ref "R55")
      (value "10K")
      (footprint "eagle-import:0402-RES")
      (libsource (lib "eagle-import") (part "RESISTOR0402-RES"))
    )
    (comp (ref "R56")
      (value "10K")
      (footprint "eagle-import:0402-RES")
      (libsource (lib "eagle-import") (part "RESISTOR0402-RES"))
    )
    (comp (ref "R57")
      (value "10K")
      (footprint "eagle-import:0402-RES")
      (libsource (lib "eagle-import") (part "RESISTOR0402-RES"))
    )
    (comp (ref "R58")
      (value "1.5K")
      (footprint "eagle-import:0402-RES")
      (libsource (lib "eagle-import") (part "RESISTOR0402-RES"))
    )
    (comp (ref "R59")
      (value "4.7k")
      (footprint "eagle-import:0402-RES")
      (libsource (lib "eagle-import") (part "RESISTOR0402-RES"))
    )
    (comp (ref "R60")
      (value "10K")
      (footprint "eagle-import:0402-RES")
      (libsource (lib "eagle-import") (part "RESISTOR0402-RES"))
    )
    (comp (ref "R65")
      (value "10K")
      (footprint "eagle-import:0402-RES")
      (libsource (lib "eagle-import") (part "RESISTOR0402-RES"))
    )
    (comp (ref "R66")
      (value "10K")
      (footprint "eagle-import:0402-RES")
      (libsource (lib "eagle-import") (part "RESISTOR0402-RES"))
    )
    (comp (ref "R67")
      (value "10K")
      (footprint "eagle-import:0402-RES")
      (libsource (lib "eagle-import") (part "RESISTOR0402-RES"))
    )
    (comp (ref "R68")
      (value "10K")
      (footprint "eagle-import:0402-RES")
      (libsource (lib "eagle-import") (part "RESISTOR0402-RES"))
    )
    (comp (ref "R69")
      (value "10K")
      (footprint "eagle-import:0402-RES")
      (libsource (lib "eagle-import") (part "RESISTOR0402-RES"))
    )
    (comp (ref "R70")
      (value "10K")
      (footprint "eagle-import:0402-RES")
      (libsource (lib "eagle-import") (part "RESISTOR0402-RES"))
    )
    (comp (ref "R71")
      (value "10K")
      (footprint "eagle-import:0402-RES")
      (libsource (lib "eagle-import") (part "RESISTOR0402-RES"))
    )
    (comp (ref "R72")
      (value "10K")
      (footprint "eagle-import:0402-RES")
      (libsource (lib "eagle-import") (part "RESISTOR0402-RES"))
    )
    (comp (ref "R73")
      (value "10K")
      (footprint "eagle-import:0402-RES")
      (libsource (lib "eagle-import") (part "RESISTOR0402-RES"))
    )
    (comp (ref "R74")
      (value "10K")
      (footprint "eagle-import:0402-RES")
      (libsource (lib "eagle-import") (part "RESISTOR0402-RES"))
    )
    (comp (ref "R75")
      (value "10K")
      (footprint "eagle-import:0402-RES")
      (libsource (lib "eagle-import") (part "RESISTOR0402-RES"))
    )
    (comp (ref "R94")
      (value "10K")
      (footprint "eagle-import:0402-RES")
      (libsource (lib "eagle-import") (part "RESISTOR0402-RES"))
    )
    (comp (ref "R104")
      (value "120, DNP")
      (footprint "eagle-import:0603-RES")
      (libsource (lib "eagle-import") (part "RESISTOR0603"))
    )
    (comp (ref "TCK")
      (value "TPSQB1,27")
      (footprint "eagle-import:B1,27")
      (libsource (lib "eagle-import") (part "TPSQB1,27"))
    )
    (comp (ref "TDI")
      (value "TPSQB1,27")
      (footprint "eagle-import:B1,27")
      (libsource (lib "eagle-import") (part "TPSQB1,27"))
    )
    (comp (ref "TDO")
      (value "TPSQB1,27")
      (footprint "eagle-import:B1,27")
      (libsource (lib "eagle-import") (part "TPSQB1,27"))
    )
    (comp (ref "TMS")
      (value "TPSQB1,27")
      (footprint "eagle-import:B1,27")
      (libsource (lib "eagle-import") (part "TPSQB1,27"))
    )
    (comp (ref "TP1")
      (value "TPSQB1,27")
      (footprint "eagle-import:B1,27")
      (libsource (lib "eagle-import") (part "TPSQB1,27"))
    )
    (comp (ref "TP5")
      (value "TPSQB1,27")
      (footprint "eagle-import:B1,27")
      (libsource (lib "eagle-import") (part "TPSQB1,27"))
    )
    (comp (ref "TP7")
      (value "TPB0,65")
      (footprint "eagle-import:B0,65")
      (libsource (lib "eagle-import") (part "TPB0,65"))
    )
    (comp (ref "TP9")
      (value "TPB0,65")
      (footprint "eagle-import:B0,65")
      (libsource (lib "eagle-import") (part "TPB0,65"))
    )
    (comp (ref "TP10")
      (value "TESTPAD/W_HOLE_1X1")
      (footprint "eagle-import:TESTPAD_W_HOLE_1X1")
      (libsource (lib "eagle-import") (part "TESTPAD/W_HOLE_1X1"))
    )
    (comp (ref "TP11")
      (value "TPB0,65")
      (footprint "eagle-import:B0,65")
      (libsource (lib "eagle-import") (part "TPB0,65"))
    )
    (comp (ref "TP12")
      (value "TPSQB1,27")
      (footprint "eagle-import:B1,27")
      (libsource (lib "eagle-import") (part "TPSQB1,27"))
    )
    (comp (ref "TRSTN")
      (value "TPSQB1,27")
      (footprint "eagle-import:B1,27")
      (libsource (lib "eagle-import") (part "TPSQB1,27"))
    )
    (comp (ref "U1")
      (value "TCAN1051HV")
      (footprint "eagle-import:D8")
      (fields
        (field (name "MANUFACTURER") "Texas Instruments")
        (field (name "MANUFACTURER_PART_NUMBER") "TCAN1051HVD")
      )
      (libsource (lib "eagle-import") (part "TCAN1051HV"))
    )
    (comp (ref "U5")
      (value "24LC_32AT-I/OT")
      (footprint "eagle-import:SOT95P290X145-5N")
      (fields (field (name "MPN") "24LC32AT-I/OT"))
      (libsource (lib "eagle-import") (part "24LC_32AT-I/OT"))
    )
    (comp (ref "U6")
      (value "SN74LVC1G07_DCK_5")
      (footprint "eagle-import:DCK5")
      (fields
        (field (name "GENERIC_PART_NUMBER") "SN74LVC1G07")
        (field (name "MANUFACTURER") "Texas Instruments")
        (field (name "MANUFACTURER_PART_NUMBER") "sn74lvc1g07_dck_5")
      )
      (libsource (lib "eagle-import") (part "SN74LVC1G07_DCK_5"))
    )
    (comp (ref "U13")
      (value "EMMC")
      (footprint "eagle-import:MICRON_EMMC_153")
      (libsource (lib "eagle-import") (part "EMMC04G-S100-B08U"))
    )
    (comp (ref "X2")
      (value "SCHA5B0200")
      (footprint "eagle-import:SCHA5B0200")
      (libsource (lib "eagle-import") (part "SCHA5B0200(ALPS_USD)"))
    )
    (comp (ref "Y1")
      (value "24 MHz")
      (footprint "eagle-import:CRYSTAL_5X3.2MM")
      (libsource (lib "eagle-import") (part "CRYSTAL_5X3.2MM"))
    )
    (comp (ref "Y2")
      (value "32.768kHz")
      (footprint "eagle-import:CRYSTAL_3.2X1.5")
      (libsource (lib "eagle-import") (part "CRYSTAL_3.2X1.5"))
    )
    (comp (ref "C42")
      (value "1nF")
      (footprint "eagle-import:0402-CAP")
      (libsource (lib "eagle-import") (part "Strawson_Eagle_Lib_CAP0402-CAP"))
    )
    (comp (ref "C43")
      (value "0.1uF")
      (footprint "eagle-import:0402-CAP")
      (libsource (lib "eagle-import") (part "Strawson_Eagle_Lib_CAP0402-CAP"))
    )
    (comp (ref "C44")
      (value "0.1uF")
      (footprint "eagle-import:0402-CAP")
      (libsource (lib "eagle-import") (part "Strawson_Eagle_Lib_CAP0402-CAP"))
    )
    (comp (ref "C45")
      (value "0.1uF")
      (footprint "eagle-import:0402-CAP")
      (libsource (lib "eagle-import") (part "Strawson_Eagle_Lib_CAP0402-CAP"))
    )
    (comp (ref "C46")
      (value "10uF")
      (footprint "eagle-import:0805")
      (libsource (lib "eagle-import") (part "Strawson_Eagle_Lib_CAP0805"))
    )
    (comp (ref "C54")
      (value "0.1uF")
      (footprint "eagle-import:0402-CAP")
      (libsource (lib "eagle-import") (part "Strawson_Eagle_Lib_CAP0402-CAP"))
    )
    (comp (ref "C55")
      (value "0.1uF")
      (footprint "eagle-import:0402-CAP")
      (libsource (lib "eagle-import") (part "Strawson_Eagle_Lib_CAP0402-CAP"))
    )
    (comp (ref "L4")
      (value "120")
      (footprint "eagle-import:L0603")
      (libsource (lib "eagle-import") (part "INDUCTOR/FERRITE-BEAD'0603'"))
    )
    (comp (ref "L5")
      (value "120")
      (footprint "eagle-import:L0603")
      (libsource (lib "eagle-import") (part "INDUCTOR/FERRITE-BEAD'0603'"))
    )
    (comp (ref "R16")
      (value "100K")
      (footprint "eagle-import:0402-RES")
      (libsource (lib "eagle-import") (part "RESISTOR0402-RES"))
    )
    (comp (ref "R17")
      (value "100K")
      (footprint "eagle-import:0402-RES")
      (libsource (lib "eagle-import") (part "RESISTOR0402-RES"))
    )
    (comp (ref "R76")
      (value "33")
      (footprint "eagle-import:0402-RES")
      (libsource (lib "eagle-import") (part "RESISTOR0402-RES"))
    )
    (comp (ref "R77")
      (value "33")
      (footprint "eagle-import:0402-RES")
      (libsource (lib "eagle-import") (part "RESISTOR0402-RES"))
    )
    (comp (ref "R109")
      (value "4.7k")
      (footprint "eagle-import:0402-RES")
      (libsource (lib "eagle-import") (part "RESISTOR0402-RES"))
    )
    (comp (ref "R110")
      (value "4.7k")
      (footprint "eagle-import:0402-RES")
      (libsource (lib "eagle-import") (part "RESISTOR0402-RES"))
    )
    (comp (ref "R111")
      (value "0")
      (footprint "eagle-import:0402-RES")
      (libsource (lib "eagle-import") (part "RESISTOR0402-RES"))
    )
    (comp (ref "R112")
      (value "0")
      (footprint "eagle-import:0603-RES")
      (libsource (lib "eagle-import") (part "RESISTOR0603"))
    )
    (comp (ref "R113")
      (value "100K")
      (footprint "eagle-import:0402-RES")
      (libsource (lib "eagle-import") (part "RESISTOR0402-RES"))
    )
    (comp (ref "R115")
      (value "100K")
      (footprint "eagle-import:0402-RES")
      (libsource (lib "eagle-import") (part "RESISTOR0402-RES"))
    )
    (comp (ref "R116")
      (value "100K")
      (footprint "eagle-import:0402-RES")
      (libsource (lib "eagle-import") (part "RESISTOR0402-RES"))
    )
    (comp (ref "R118")
      (value "100K")
      (footprint "eagle-import:0402-RES")
      (libsource (lib "eagle-import") (part "RESISTOR0402-RES"))
    )
    (comp (ref "R119")
      (value "0")
      (footprint "eagle-import:0603-RES")
      (libsource (lib "eagle-import") (part "RESISTOR0603"))
    )
    (comp (ref "R120")
      (value "100K")
      (footprint "eagle-import:0402-RES")
      (libsource (lib "eagle-import") (part "RESISTOR0402-RES"))
    )
    (comp (ref "R121")
      (value "0, DNP")
      (footprint "eagle-import:0603-RES")
      (libsource (lib "eagle-import") (part "RESISTOR0603"))
    )
    (comp (ref "R122")
      (value "100K")
      (footprint "eagle-import:0402-RES")
      (libsource (lib "eagle-import") (part "RESISTOR0402-RES"))
    )
    (comp (ref "R125")
      (value "100K")
      (footprint "eagle-import:0402-RES")
      (libsource (lib "eagle-import") (part "RESISTOR0402-RES"))
    )
    (comp (ref "R127")
      (value "100K")
      (footprint "eagle-import:0402-RES")
      (libsource (lib "eagle-import") (part "RESISTOR0402-RES"))
    )
    (comp (ref "R129")
      (value "100K")
      (footprint "eagle-import:0402-RES")
      (libsource (lib "eagle-import") (part "RESISTOR0402-RES"))
    )
    (comp (ref "R131")
      (value "100K")
      (footprint "eagle-import:0402-RES")
      (libsource (lib "eagle-import") (part "RESISTOR0402-RES"))
    )
    (comp (ref "R135")
      (value "100K")
      (footprint "eagle-import:0402-RES")
      (libsource (lib "eagle-import") (part "RESISTOR0402-RES"))
    )
    (comp (ref "R140")
      (value "100K")
      (footprint "eagle-import:0402-RES")
      (libsource (lib "eagle-import") (part "RESISTOR0402-RES"))
    )
    (comp (ref "R143")
      (value "100K")
      (footprint "eagle-import:0402-RES")
      (libsource (lib "eagle-import") (part "RESISTOR0402-RES"))
    )
    (comp (ref "R149")
      (value "0")
      (footprint "eagle-import:0402-RES")
      (libsource (lib "eagle-import") (part "RESISTOR0402-RES"))
    )
    (comp (ref "R150")
      (value "0")
      (footprint "eagle-import:0402-RES")
      (libsource (lib "eagle-import") (part "RESISTOR0402-RES"))
    )
    (comp (ref "R156")
      (value "33")
      (footprint "eagle-import:0402-RES")
      (libsource (lib "eagle-import") (part "RESISTOR0402-RES"))
    )
    (comp (ref "U3")
      (value "TPD4S012DRY")
      (footprint "eagle-import:SON-6(TI)-DRY")
      (libsource (lib "eagle-import") (part "TPD4S012DRYR"))
    )
    (comp (ref "U4")
      (value "TPD4S012DRY")
      (footprint "eagle-import:SON-6(TI)-DRY")
      (libsource (lib "eagle-import") (part "TPD4S012DRYR"))
    )
    (comp (ref "X3")
      (value "USB1")
      (footprint "eagle-import:USB_HOST_HORIZONTAL_W_CHASSIS_GND")
      (libsource (lib "eagle-import") (part "USB_HOST_W/CHASSIS_GND"))
    )
    (comp (ref "X4")
      (value "10118192-0001LF")
      (footprint "eagle-import:10118192-0001LF(MICRO-USB-B-AMPHENOL-FCI)")
      (libsource (lib "eagle-import") (part "10118192-0001LF"))
    )
    (comp (ref "ANT1")
      (value "U.FL-R-SMT-1(10)")
      (footprint "eagle-import:U.FL-R-SMT-1")
      (libsource (lib "eagle-import") (part "U.FL-R-SMT-1"))
    )
    (comp (ref "ANT2")
      (value "U.FL-R-SMT-1(10)")
      (footprint "eagle-import:U.FL-R-SMT-1")
      (libsource (lib "eagle-import") (part "U.FL-R-SMT-1"))
    )
    (comp (ref "BT")
      (value "BLUE")
      (footprint "eagle-import:LED-0603")
      (libsource (lib "eagle-import") (part "LED0603"))
    )
    (comp (ref "C47")
      (value "0.1uF")
      (footprint "eagle-import:0402-CAP")
      (libsource (lib "eagle-import") (part "Strawson_Eagle_Lib_CAP0402-CAP"))
    )
    (comp (ref "C48")
      (value "10pF")
      (footprint "eagle-import:0402-CAP")
      (libsource (lib "eagle-import") (part "Strawson_Eagle_Lib_CAP0402-CAP"))
    )
    (comp (ref "C49")
      (value "0.1uF")
      (footprint "eagle-import:0402-CAP")
      (libsource (lib "eagle-import") (part "Strawson_Eagle_Lib_CAP0402-CAP"))
    )
    (comp (ref "C50")
      (value "0.1uF")
      (footprint "eagle-import:0402-CAP")
      (libsource (lib "eagle-import") (part "Strawson_Eagle_Lib_CAP0402-CAP"))
    )
    (comp (ref "C51")
      (value "0.1uF")
      (footprint "eagle-import:0402-CAP")
      (libsource (lib "eagle-import") (part "Strawson_Eagle_Lib_CAP0402-CAP"))
    )
    (comp (ref "C52")
      (value "0.1uF")
      (footprint "eagle-import:0402-CAP")
      (libsource (lib "eagle-import") (part "Strawson_Eagle_Lib_CAP0402-CAP"))
    )
    (comp (ref "C53")
      (value "10uF")
      (footprint "eagle-import:0805")
      (libsource (lib "eagle-import") (part "CAP0805"))
    )
    (comp (ref "C56")
      (value "0.1uF")
      (footprint "eagle-import:0402-CAP")
      (libsource (lib "eagle-import") (part "Strawson_Eagle_Lib_CAP0402-CAP"))
    )
    (comp (ref "C57")
      (value "1uF")
      (footprint "eagle-import:0402-CAP")
      (libsource (lib "eagle-import") (part "Strawson_Eagle_Lib_CAP0402-CAP"))
    )
    (comp (ref "C58")
      (value "10pF")
      (footprint "eagle-import:0402-CAP")
      (libsource (lib "eagle-import") (part "Strawson_Eagle_Lib_CAP0402-CAP"))
    )
    (comp (ref "OSC1")
      (value "NZ2520SB-32.768KHZ-NSA3534C")
      (footprint "eagle-import:NZ2520S")
      (libsource (lib "eagle-import") (part "OSCILLATOR"))
    )
    (comp (ref "R9")
      (value "10K, DNP")
      (footprint "eagle-import:0402-RES")
      (libsource (lib "eagle-import") (part "RESISTOR0402-RES"))
    )
    (comp (ref "R78")
      (value "33")
      (footprint "eagle-import:0402-RES")
      (libsource (lib "eagle-import") (part "RESISTOR0402-RES"))
    )
    (comp (ref "R79")
      (value "33")
      (footprint "eagle-import:0402-RES")
      (libsource (lib "eagle-import") (part "RESISTOR0402-RES"))
    )
    (comp (ref "R80")
      (value "33")
      (footprint "eagle-import:0402-RES")
      (libsource (lib "eagle-import") (part "RESISTOR0402-RES"))
    )
    (comp (ref "R81")
      (value "33")
      (footprint "eagle-import:0402-RES")
      (libsource (lib "eagle-import") (part "RESISTOR0402-RES"))
    )
    (comp (ref "R82")
      (value "33")
      (footprint "eagle-import:0402-RES")
      (libsource (lib "eagle-import") (part "RESISTOR0402-RES"))
    )
    (comp (ref "R83")
      (value "33")
      (footprint "eagle-import:0402-RES")
      (libsource (lib "eagle-import") (part "RESISTOR0402-RES"))
    )
    (comp (ref "R84")
      (value "33")
      (footprint "eagle-import:0402-RES")
      (libsource (lib "eagle-import") (part "RESISTOR0402-RES"))
    )
    (comp (ref "R85")
      (value "33")
      (footprint "eagle-import:0402-RES")
      (libsource (lib "eagle-import") (part "RESISTOR0402-RES"))
    )
    (comp (ref "R86")
      (value "33")
      (footprint "eagle-import:0402-RES")
      (libsource (lib "eagle-import") (part "RESISTOR0402-RES"))
    )
    (comp (ref "R87")
      (value "100K")
      (footprint "eagle-import:0402-RES")
      (libsource (lib "eagle-import") (part "RESISTOR0402-RES"))
    )
    (comp (ref "R88")
      (value "100K")
      (footprint "eagle-import:0402-RES")
      (libsource (lib "eagle-import") (part "RESISTOR0402-RES"))
    )
    (comp (ref "R89")
      (value "1K, DNP")
      (footprint "eagle-import:0402-RES")
      (libsource (lib "eagle-import") (part "RESISTOR0402-RES"))
    )
    (comp (ref "R90")
      (value "1K")
      (footprint "eagle-import:0402-RES")
      (libsource (lib "eagle-import") (part "RESISTOR0402-RES"))
    )
    (comp (ref "R91")
      (value "1K")
      (footprint "eagle-import:0402-RES")
      (libsource (lib "eagle-import") (part "RESISTOR0402-RES"))
    )
    (comp (ref "R92")
      (value "33")
      (footprint "eagle-import:0402-RES")
      (libsource (lib "eagle-import") (part "RESISTOR0402-RES"))
    )
    (comp (ref "R93")
      (value "33")
      (footprint "eagle-import:0402-RES")
      (libsource (lib "eagle-import") (part "RESISTOR0402-RES"))
    )
    (comp (ref "R95")
      (value "1K")
      (footprint "eagle-import:0402-RES")
      (libsource (lib "eagle-import") (part "RESISTOR0402-RES"))
    )
    (comp (ref "R96")
      (value "33")
      (footprint "eagle-import:0402-RES")
      (libsource (lib "eagle-import") (part "RESISTOR0402-RES"))
    )
    (comp (ref "R97")
      (value "33")
      (footprint "eagle-import:0402-RES")
      (libsource (lib "eagle-import") (part "RESISTOR0402-RES"))
    )
    (comp (ref "R98")
      (value "10K")
      (footprint "eagle-import:0402-RES")
      (libsource (lib "eagle-import") (part "RESISTOR0402-RES"))
    )
    (comp (ref "R99")
      (value "10K")
      (footprint "eagle-import:0402-RES")
      (libsource (lib "eagle-import") (part "RESISTOR0402-RES"))
    )
    (comp (ref "R100")
      (value "33")
      (footprint "eagle-import:0402-RES")
      (libsource (lib "eagle-import") (part "RESISTOR0402-RES"))
    )
    (comp (ref "R101")
      (value "10K")
      (footprint "eagle-import:0402-RES")
      (libsource (lib "eagle-import") (part "RESISTOR0402-RES"))
    )
    (comp (ref "R102")
      (value "10K")
      (footprint "eagle-import:0402-RES")
      (libsource (lib "eagle-import") (part "RESISTOR0402-RES"))
    )
    (comp (ref "R103")
      (value "10K")
      (footprint "eagle-import:0402-RES")
      (libsource (lib "eagle-import") (part "RESISTOR0402-RES"))
    )
    (comp (ref "R105")
      (value "10K")
      (footprint "eagle-import:0402-RES")
      (libsource (lib "eagle-import") (part "RESISTOR0402-RES"))
    )
    (comp (ref "R106")
      (value "1.5K")
      (footprint "eagle-import:0402-RES")
      (libsource (lib "eagle-import") (part "RESISTOR0402-RES"))
    )
    (comp (ref "R108")
      (value "1K, DNP")
      (footprint "eagle-import:0402-RES")
      (libsource (lib "eagle-import") (part "RESISTOR0402-RES"))
    )
    (comp (ref "R123")
      (value "33")
      (footprint "eagle-import:0402-RES")
      (libsource (lib "eagle-import") (part "RESISTOR0402-RES"))
    )
    (comp (ref "R124")
      (value "33")
      (footprint "eagle-import:0402-RES")
      (libsource (lib "eagle-import") (part "RESISTOR0402-RES"))
    )
    (comp (ref "T1")
      (value "BSS138W-7-F")
      (footprint "eagle-import:SOT-323(DIODES)")
      (libsource (lib "eagle-import") (part "BSS138W-7-F"))
    )
    (comp (ref "T2")
      (value "BSS138W-7-F")
      (footprint "eagle-import:SOT-323(DIODES)")
      (libsource (lib "eagle-import") (part "BSS138W-7-F"))
    )
    (comp (ref "U2")
      (value "SN74LV1T126DBVR")
      (footprint "eagle-import:SOT23-5")
      (libsource (lib "eagle-import") (part "SN74LV1T126DBVR"))
    )
    (comp (ref "U7")
      (value "WL1835MODGBMOCT")
      (footprint "eagle-import:MOC-100(TI)")
      (libsource (lib "eagle-import") (part "WL1835MOD"))
    )
    (comp (ref "U9")
      (value "TXS0108ERGYR")
      (footprint "eagle-import:R-PVQFN-N20(TI)")
      (libsource (lib "eagle-import") (part "TXS0108ERGYR"))
    )
    (comp (ref "U10")
      (value "TXS0108ERGYR")
      (footprint "eagle-import:R-PVQFN-N20(TI)")
      (libsource (lib "eagle-import") (part "TXS0108ERGYR"))
    )
    (comp (ref "WL")
      (value "BLUE")
      (footprint "eagle-import:LED-0603")
      (libsource (lib "eagle-import") (part "LED0603"))
    )
  )
  (nets
    (net (code "1") (name "3.3V") (class "Default")
      (node (ref "BMP") (pin "2") (pinfunction "CSB_2") (pintype "input"))
      (node (ref "BMP") (pin "6") (pinfunction "VDDIO_6") (pintype "input"))
      (node (ref "BMP") (pin "8") (pinfunction "VDD_8") (pintype "power_in"))
      (node (ref "BT") (pin "A") (pinfunction "A_A") (pintype "passive"))
      (node (ref "C13") (pin "1") (pinfunction "1_1") (pintype "passive"))
      (node (ref "C16") (pin "1") (pinfunction "1_1") (pintype "passive"))
      (node (ref "C2") (pin "2") (pinfunction "2_2") (pintype "passive"))
      (node (ref "C27") (pin "1") (pinfunction "1_1") (pintype "passive"))
      (node (ref "C28") (pin "1") (pinfunction "1_1") (pintype "passive"))
      (node (ref "C34") (pin "2") (pinfunction "2_2") (pintype "passive"))
      (node (ref "C35") (pin "2") (pinfunction "2_2") (pintype "passive"))
      (node (ref "C37") (pin "1") (pinfunction "1_1") (pintype "passive"))
      (node (ref "C38") (pin "1") (pinfunction "1_1") (pintype "passive"))
      (node (ref "C39") (pin "1") (pinfunction "1_1") (pintype "passive"))
      (node (ref "C40") (pin "1") (pinfunction "1_1") (pintype "passive"))
      (node (ref "C41") (pin "1") (pinfunction "1_1") (pintype "passive"))
      (node (ref "C49") (pin "2") (pinfunction "2_2") (pintype "passive"))
      (node (ref "C51") (pin "2") (pinfunction "2_2") (pintype "passive"))
      (node (ref "C53") (pin "1") (pinfunction "1_1") (pintype "passive"))
      (node (ref "C56") (pin "1") (pinfunction "1_1") (pintype "passive"))
      (node (ref "C8") (pin "1") (pinfunction "1_1") (pintype "passive"))
      (node (ref "C9") (pin "2") (pinfunction "2_2") (pintype "passive"))
      (node (ref "CAN") (pin "2") (pinfunction "2_2") (pintype "bidirectional"))
      (node (ref "DSM2") (pin "P$1") (pinfunction "1_P$1") (pintype "bidirectional"))
      (node (ref "E1") (pin "2") (pinfunction "2_2") (pintype "bidirectional"))
      (node (ref "E2") (pin "2") (pinfunction "2_2") (pintype "bidirectional"))
      (node (ref "E3") (pin "2") (pinfunction "2_2") (pintype "bidirectional"))
      (node (ref "E4") (pin "2") (pinfunction "2_2") (pintype "bidirectional"))
      (node (ref "GP0") (pin "2") (pinfunction "2_2") (pintype "bidirectional"))
      (node (ref "GP1") (pin "3") (pinfunction "3_3") (pintype "bidirectional"))
      (node (ref "H1") (pin "20") (pinfunction "VCC_20") (pintype "bidirectional"))
      (node (ref "H2") (pin "20") (pinfunction "VCC_20") (pintype "bidirectional"))
      (node (ref "I2C1") (pin "3") (pinfunction "3_3") (pintype "bidirectional"))
      (node (ref "IMU") (pin "1") (pinfunction "RESV_1") (pintype "bidirectional"))
      (node (ref "IMU") (pin "13") (pinfunction "VDD_13") (pintype "bidirectional"))
      (node (ref "IMU") (pin "22") (pinfunction "NCS_22") (pintype "bidirectional"))
      (node (ref "IMU") (pin "8") (pinfunction "VDDIO_8") (pintype "bidirectional"))
      (node (ref "PWR") (pin "3") (pinfunction "3_3") (pintype "bidirectional"))
      (node (ref "R10") (pin "1") (pinfunction "1_1") (pintype "passive"))
      (node (ref "R109") (pin "1") (pinfunction "1_1") (pintype "passive"))
      (node (ref "R11") (pin "2") (pinfunction "2_2") (pintype "passive"))
      (node (ref "R116") (pin "2") (pinfunction "2_2") (pintype "passive"))
      (node (ref "R118") (pin "2") (pinfunction "2_2") (pintype "passive"))
      (node (ref "R12") (pin "2") (pinfunction "2_2") (pintype "passive"))
      (node (ref "R120") (pin "2") (pinfunction "2_2") (pintype "passive"))
      (node (ref "R122") (pin "2") (pinfunction "2_2") (pintype "passive"))
      (node (ref "R13") (pin "1") (pinfunction "1_1") (pintype "passive"))
      (node (ref "R140") (pin "2") (pinfunction "2_2") (pintype "passive"))
      (node (ref "R2") (pin "2") (pinfunction "2_2") (pintype "passive"))
      (node (ref "R23") (pin "2") (pinfunction "2_2") (pintype "passive"))
      (node (ref "R26") (pin "2") (pinfunction "2_2") (pintype "passive"))
      (node (ref "R35") (pin "2") (pinfunction "2_2") (pintype "passive"))
      (node (ref "R54") (pin "2") (pinfunction "2_2") (pintype "passive"))
      (node (ref "R55") (pin "2") (pinfunction "2_2") (pintype "passive"))
      (node (ref "R56") (pin "2") (pinfunction "2_2") (pintype "passive"))
      (node (ref "R57") (pin "2") (pinfunction "2_2") (pintype "passive"))
      (node (ref "R58") (pin "2") (pinfunction "2_2") (pintype "passive"))
      (node (ref "R60") (pin "2") (pinfunction "2_2") (pintype "passive"))
      (node (ref "R65") (pin "2") (pinfunction "2_2") (pintype "passive"))
      (node (ref "R66") (pin "2") (pinfunction "2_2") (pintype "passive"))
      (node (ref "R67") (pin "2") (pinfunction "2_2") (pintype "passive"))
      (node (ref "R68") (pin "2") (pinfunction "2_2") (pintype "passive"))
      (node (ref "R69") (pin "2") (pinfunction "2_2") (pintype "passive"))
      (node (ref "R70") (pin "2") (pinfunction "2_2") (pintype "passive"))
      (node (ref "R71") (pin "2") (pinfunction "2_2") (pintype "passive"))
      (node (ref "R72") (pin "2") (pinfunction "2_2") (pintype "passive"))
      (node (ref "R73") (pin "2") (pinfunction "2_2") (pintype "passive"))
      (node (ref "R74") (pin "2") (pinfunction "2_2") (pintype "passive"))
      (node (ref "R75") (pin "2") (pinfunction "2_2") (pintype "passive"))
      (node (ref "R94") (pin "2") (pinfunction "2_2") (pintype "passive"))
      (node (ref "S1.1") (pin "2") (pinfunction "2_2") (pintype "bidirectional"))
      (node (ref "S1.2") (pin "2") (pinfunction "2_2") (pintype "bidirectional"))
      (node (ref "SIP") (pin "U20") (pinfunction "VOUT_USER_3P3V_0_U20") (pintype "power_in"))
      (node (ref "SIP") (pin "V20") (pinfunction "VOUT_USER_3P3V_1_V20") (pintype "power_in"))
      (node (ref "U1") (pin "5") (pinfunction "VIO_5") (pintype "power_in"))
      (node (ref "U10") (pin "19") (pinfunction "VCCB_19") (pintype "bidirectional"))
      (node (ref "U13") (pin "C6") (pinfunction "VCCQ1_C6") (pintype "bidirectional"))
      (node (ref "U13") (pin "E6") (pinfunction "VCC1_E6") (pintype "bidirectional"))
      (node (ref "U13") (pin "F5") (pinfunction "VCC2_F5") (pintype "bidirectional"))
      (node (ref "U13") (pin "J10") (pinfunction "VCC3_J10") (pintype "bidirectional"))
      (node (ref "U13") (pin "K9") (pinfunction "VCC4_K9") (pintype "bidirectional"))
      (node (ref "U13") (pin "M4") (pinfunction "VCCQ2_M4") (pintype "bidirectional"))
      (node (ref "U13") (pin "N4") (pinfunction "VCCQ3_N4") (pintype "bidirectional"))
      (node (ref "U13") (pin "P3") (pinfunction "VCCQ4_P3") (pintype "bidirectional"))
      (node (ref "U13") (pin "P5") (pinfunction "VCCQ5_P5") (pintype "bidirectional"))
      (node (ref "U5") (pin "4") (pinfunction "VCC_4") (pintype "power_in"))
      (node (ref "U7") (pin "46") (pinfunction "VBAT_IN1_46") (pintype "bidirectional"))
      (node (ref "U7") (pin "47") (pinfunction "VBAT_IN2_47") (pintype "bidirectional"))
      (node (ref "U9") (pin "19") (pinfunction "VCCB_19") (pintype "bidirectional"))
      (node (ref "UT0") (pin "2") (pinfunction "2_2") (pintype "bidirectional"))
      (node (ref "UT1") (pin "2") (pinfunction "2_2") (pintype "bidirectional"))
      (node (ref "UT5") (pin "3") (pinfunction "3_3") (pintype "bidirectional"))
      (node (ref "WL") (pin "A") (pinfunction "A_A") (pintype "passive"))
      (node (ref "X2") (pin "4") (pinfunction "VDD_4") (pintype "bidirectional"))
    )
    (net (code "2") (name "5.0V") (class "Default")
      (node (ref "5VREG") (pin "3") (pinfunction "FB_3") (pintype "power_in"))
      (node (ref "C5") (pin "1") (pinfunction "1_1") (pintype "passive"))
      (node (ref "GPS") (pin "5") (pinfunction "5_5") (pintype "bidirectional"))
      (node (ref "L1") (pin "2") (pinfunction "2_2") (pintype "passive"))
      (node (ref "PWR") (pin "4") (pinfunction "4_4") (pintype "bidirectional"))
      (node (ref "R119") (pin "2") (pinfunction "2_2") (pintype "passive"))
      (node (ref "SIP") (pin "Y5") (pinfunction "VIN_AC_0_Y5") (pintype "power_in"))
      (node (ref "SIP") (pin "Y6") (pinfunction "VIN_AC_1_Y6") (pintype "power_in"))
      (node (ref "U1") (pin "3") (pinfunction "VCC_3") (pintype "power_in"))
    )
    (net (code "3") (name "32.768KHZ") (class "Default")
      (node (ref "OSC1") (pin "3") (pinfunction "OUT_3") (pintype "bidirectional"))
      (node (ref "U7") (pin "36") (pinfunction "EXT_32K_36") (pintype "bidirectional"))
    )
    (net (code "4") (name "AIN0") (class "Default")
      (node (ref "ADC") (pin "3") (pinfunction "3_3") (pintype "bidirectional"))
      (node (ref "SIP") (pin "B6") (pinfunction "AIN0_B6") (pintype "bidirectional"))
    )
    (net (code "5") (name "AIN1") (class "Default")
      (node (ref "ADC") (pin "4") (pinfunction "4_4") (pintype "bidirectional"))
      (node (ref "SIP") (pin "C7") (pinfunction "AIN1_C7") (pintype "bidirectional"))
    )
    (net (code "6") (name "AIN2") (class "Default")
      (node (ref "ADC") (pin "5") (pinfunction "5_5") (pintype "bidirectional"))
      (node (ref "SIP") (pin "B7") (pinfunction "AIN2_B7") (pintype "bidirectional"))
    )
    (net (code "7") (name "AIN3") (class "Default")
      (node (ref "ADC") (pin "6") (pinfunction "6_6") (pintype "bidirectional"))
      (node (ref "SIP") (pin "A7") (pinfunction "AIN3_A7") (pintype "bidirectional"))
    )
    (net (code "8") (name "BATT_LED_1") (class "Default")
      (node (ref "B0") (pin "A") (pinfunction "A_A") (pintype "passive"))
      (node (ref "SIP") (pin "U12") (pinfunction "GPIO0_27_U12_U12") (pintype "bidirectional"))
    )
    (net (code "9") (name "BATT_LED_2") (class "Default")
      (node (ref "B1") (pin "A") (pinfunction "A_A") (pintype "passive"))
      (node (ref "R143") (pin "2") (pinfunction "2_2") (pintype "passive"))
      (node (ref "SIP") (pin "T5") (pinfunction "LCD_DATA15_T5_T5") (pintype "bidirectional"))
    )
    (net (code "10") (name "BATT_LED_3") (class "Default")
      (node (ref "B2") (pin "A") (pinfunction "A_A") (pintype "passive"))
      (node (ref "SIP") (pin "V6") (pinfunction "GPIO1_29_V6_V6") (pintype "bidirectional"))
    )
    (net (code "11") (name "BATT_LED_4") (class "Default")
      (node (ref "B3") (pin "A") (pinfunction "A_A") (pintype "passive"))
      (node (ref "SIP") (pin "T11") (pinfunction "GPIO0_26_T11_T11") (pintype "bidirectional"))
    )
    (net (code "12") (name "BATT_MID") (class "Default")
      (node (ref "LIPO") (pin "P$2") (pinfunction "2_P$2") (pintype "passive"))
      (node (ref "R27") (pin "1") (pinfunction "1_1") (pintype "passive"))
      (node (ref "R30") (pin "1") (pinfunction "1_1") (pintype "passive"))
      (node (ref "R44") (pin "1") (pinfunction "1_1") (pintype "passive"))
    )
    (net (code "13") (name "BATT_MINUS") (class "Default")
      (node (ref "BAL") (pin "5") (pinfunction "GND_5") (pintype "bidirectional"))
      (node (ref "BAL") (pin "6") (pinfunction "CB_EN_6") (pintype "bidirectional"))
      (node (ref "C1") (pin "2") (pinfunction "2_2") (pintype "passive"))
      (node (ref "C15") (pin "1") (pinfunction "1_1") (pintype "passive"))
      (node (ref "C18") (pin "1") (pinfunction "1_1") (pintype "passive"))
      (node (ref "C19") (pin "2") (pinfunction "2_2") (pintype "passive"))
      (node (ref "LIPO") (pin "P$3") (pinfunction "3_P$3") (pintype "passive"))
      (node (ref "PROT") (pin "2") (pinfunction "VM_2") (pintype "bidirectional"))
      (node (ref "PROT") (pin "6") (pinfunction "VSS_6") (pintype "bidirectional"))
      (node (ref "Q1") (pin "1") (pinfunction "S_1") (pintype "passive"))
      (node (ref "Q1") (pin "2") (pinfunction "S_2") (pintype "passive"))
      (node (ref "Q1") (pin "3") (pinfunction "S_3") (pintype "passive"))
    )
    (net (code "14") (name "BT_AUD_CLK") (class "Default")
      (node (ref "R124") (pin "1") (pinfunction "1_1") (pintype "passive"))
      (node (ref "U10") (pin "1") (pinfunction "A1_1") (pintype "bidirectional"))
    )
    (net (code "15") (name "BT_AUD_FSYNC") (class "Default")
      (node (ref "R123") (pin "1") (pinfunction "1_1") (pintype "passive"))
      (node (ref "U10") (pin "3") (pinfunction "A2_3") (pintype "bidirectional"))
    )
    (net (code "16") (name "BT_AUD_IN") (class "Default")
      (node (ref "R97") (pin "1") (pinfunction "1_1") (pintype "passive"))
      (node (ref "U10") (pin "5") (pinfunction "A4_5") (pintype "bidirectional"))
    )
    (net (code "17") (name "BT_AUD_OUT") (class "Default")
      (node (ref "R100") (pin "1") (pinfunction "1_1") (pintype "passive"))
      (node (ref "U10") (pin "4") (pinfunction "A3_4") (pintype "bidirectional"))
    )
    (net (code "18") (name "BT_EN") (class "Default")
      (node (ref "SIP") (pin "K17") (pinfunction "K17_K17") (pintype "bidirectional"))
      (node (ref "U9") (pin "18") (pinfunction "B2_18") (pintype "bidirectional"))
    )
    (net (code "19") (name "BT_EN_1V8") (class "Default")
      (node (ref "R88") (pin "1") (pinfunction "1_1") (pintype "passive"))
      (node (ref "T2") (pin "G") (pinfunction "G_G") (pintype "bidirectional"))
      (node (ref "U7") (pin "41") (pinfunction "BT_EN_41") (pintype "bidirectional"))
      (node (ref "U9") (pin "3") (pinfunction "A2_3") (pintype "bidirectional"))
    )
    (net (code "20") (name "BT_HCI_CTS") (class "Default")
      (node (ref "R86") (pin "1") (pinfunction "1_1") (pintype "passive"))
      (node (ref "U10") (pin "8") (pinfunction "A7_8") (pintype "bidirectional"))
    )
    (net (code "21") (name "BT_HCI_RTS") (class "Default")
      (node (ref "R85") (pin "1") (pinfunction "1_1") (pintype "passive"))
      (node (ref "U10") (pin "9") (pinfunction "A8_9") (pintype "bidirectional"))
    )
    (net (code "22") (name "BT_HCI_RX") (class "Default")
      (node (ref "R96") (pin "1") (pinfunction "1_1") (pintype "passive"))
      (node (ref "U10") (pin "6") (pinfunction "A5_6") (pintype "bidirectional"))
    )
    (net (code "23") (name "BT_HCI_TX") (class "Default")
      (node (ref "R92") (pin "1") (pinfunction "1_1") (pintype "passive"))
      (node (ref "U10") (pin "7") (pinfunction "A6_7") (pintype "bidirectional"))
    )
    (net (code "24") (name "CANH") (class "Default")
      (node (ref "CAN") (pin "3") (pinfunction "3_3") (pintype "bidirectional"))
      (node (ref "R104") (pin "1") (pinfunction "1_1") (pintype "passive"))
      (node (ref "U1") (pin "7") (pinfunction "CANH_7") (pintype "bidirectional"))
    )
    (net (code "25") (name "CANL") (class "Default")
      (node (ref "CAN") (pin "4") (pinfunction "4_4") (pintype "bidirectional"))
      (node (ref "R104") (pin "2") (pinfunction "2_2") (pintype "passive"))
      (node (ref "U1") (pin "6") (pinfunction "CANL_6") (pintype "bidirectional"))
    )
    (net (code "26") (name "CGND") (class "Default")
      (node (ref "MGT1") (pin "P$1") (pinfunction "P$1_P$1") (pintype "bidirectional"))
      (node (ref "MGT2") (pin "P$1") (pinfunction "P$1_P$1") (pintype "bidirectional"))
      (node (ref "MGT3") (pin "P$1") (pinfunction "P$1_P$1") (pintype "bidirectional"))
      (node (ref "MGT4") (pin "P$1") (pinfunction "P$1_P$1") (pintype "bidirectional"))
      (node (ref "R107") (pin "2") (pinfunction "2_2") (pintype "passive"))
      (node (ref "X2") (pin "CGND1") (pinfunction "CGND1_CGND1") (pintype "bidirectional"))
      (node (ref "X2") (pin "CGND2") (pinfunction "CGND2_CGND2") (pintype "bidirectional"))
      (node (ref "X2") (pin "CGND3") (pinfunction "CGND3_CGND3") (pintype "bidirectional"))
      (node (ref "X2") (pin "CGND4") (pinfunction "CGND4_CGND4") (pintype "bidirectional"))
      (node (ref "X2") (pin "CGND5") (pinfunction "CGND5_CGND5") (pintype "bidirectional"))
      (node (ref "X2") (pin "CGND6") (pinfunction "CGND6_CGND6") (pintype "bidirectional"))
      (node (ref "X3") (pin "5") (pinfunction "CG1_5") (pintype "bidirectional"))
      (node (ref "X3") (pin "6") (pinfunction "CG2_6") (pintype "bidirectional"))
      (node (ref "X4") (pin "CGND1") (pinfunction "SGND1_CGND1") (pintype "bidirectional"))
      (node (ref "X4") (pin "CGND2") (pinfunction "SGND2_CGND2") (pintype "bidirectional"))
      (node (ref "X4") (pin "CGND3") (pinfunction "SGND3_CGND3") (pintype "bidirectional"))
      (node (ref "X4") (pin "CGND4") (pinfunction "SGND4_CGND4") (pintype "bidirectional"))
      (node (ref "X4") (pin "CGND5") (pinfunction "SGND5_CGND5") (pintype "bidirectional"))
      (node (ref "X4") (pin "CGND6") (pinfunction "SGND6_CGND6") (pintype "bidirectional"))
    )
    (net (code "27") (name "CHG_EN") (class "Default")
      (node (ref "CHGIC") (pin "6") (pinfunction "EN_6") (pintype "bidirectional"))
      (node (ref "R7") (pin "2") (pinfunction "2_2") (pintype "passive"))
      (node (ref "R8") (pin "1") (pinfunction "1_1") (pintype "passive"))
    )
    (net (code "28") (name "DCAN1_RX") (class "Default")
      (node (ref "SIP") (pin "E17") (pinfunction "UART0_RTSN_E17_E17") (pintype "bidirectional"))
      (node (ref "U1") (pin "4") (pinfunction "RXD_4") (pintype "output"))
    )
    (net (code "29") (name "DCAN1_SILENT") (class "Default")
      (node (ref "SIP") (pin "M16") (pinfunction "M16_M16") (pintype "bidirectional"))
      (node (ref "U1") (pin "8") (pinfunction "S_8") (pintype "input"))
    )
    (net (code "30") (name "DCAN1_TX") (class "Default")
      (node (ref "SIP") (pin "E18") (pinfunction "UART0_CTSN_E18_E18") (pintype "bidirectional"))
      (node (ref "U1") (pin "1") (pinfunction "TXD_1") (pintype "input"))
    )
    (net (code "31") (name "DO") (class "Default")
      (node (ref "PROT") (pin "1") (pinfunction "DO_1") (pintype "bidirectional"))
      (node (ref "Q1") (pin "4") (pinfunction "G_4") (pintype "passive"))
    )
    (net (code "32") (name "EMMC_RST") (class "Default")
      (node (ref "R94") (pin "1") (pinfunction "1_1") (pintype "passive"))
      (node (ref "SIP") (pin "R14") (pinfunction "EMMCRST_GPIO1_20_R14_R14") (pintype "bidirectional"))
      (node (ref "U13") (pin "K5") (pinfunction "RST#_K5") (pintype "bidirectional"))
    )
    (net (code "33") (name "EQEP_0A") (class "Default")
      (node (ref "E1") (pin "3") (pinfunction "3_3") (pintype "bidirectional"))
      (node (ref "SIP") (pin "B12") (pinfunction "GPIO3_18_B12_B12") (pintype "bidirectional"))
    )
    (net (code "34") (name "EQEP_0B") (class "Default")
      (node (ref "E1") (pin "4") (pinfunction "4_4") (pintype "bidirectional"))
      (node (ref "SIP") (pin "C13") (pinfunction "GPIO3_19_C13_C13") (pintype "bidirectional"))
    )
    (net (code "35") (name "EQEP_1A") (class "Default")
      (node (ref "E2") (pin "3") (pinfunction "3_3") (pintype "bidirectional"))
      (node (ref "R16") (pin "2") (pinfunction "2_2") (pintype "passive"))
      (node (ref "SIP") (pin "V2") (pinfunction "LCD_DATA12_V2_V2") (pintype "bidirectional"))
    )
    (net (code "36") (name "EQEP_1B") (class "Default")
      (node (ref "E2") (pin "4") (pinfunction "4_4") (pintype "bidirectional"))
      (node (ref "R17") (pin "2") (pinfunction "2_2") (pintype "passive"))
      (node (ref "SIP") (pin "V3") (pinfunction "LCD_DATA13_V3_V3") (pintype "bidirectional"))
    )
    (net (code "37") (name "EQEP_2A") (class "Default")
      (node (ref "E3") (pin "3") (pinfunction "3_3") (pintype "bidirectional"))
      (node (ref "SIP") (pin "T12") (pinfunction "GPIO1_12_T12_T12") (pintype "bidirectional"))
    )
    (net (code "38") (name "EQEP_2B") (class "Default")
      (node (ref "E3") (pin "4") (pinfunction "4_4") (pintype "bidirectional"))
      (node (ref "SIP") (pin "R12") (pinfunction "GPIO1_13_R12_R12") (pintype "bidirectional"))
    )
    (net (code "39") (name "GND") (class "Default")
      (node (ref "12V") (pin "OUT") (pinfunction "OUT_OUT") (pintype "bidirectional"))
      (node (ref "5VREG") (pin "4") (pinfunction "SD_4") (pintype "input"))
      (node (ref "5VREG") (pin "5") (pinfunction "GND_5") (pintype "power_in"))
      (node (ref "5VREG") (pin "6") (pinfunction "GND1_6") (pintype "input"))
      (node (ref "5VREG") (pin "7") (pinfunction "GND2_7") (pintype "passive"))
      (node (ref "5VREG") (pin "8") (pinfunction "GND3_8") (pintype "power_in"))
      (node (ref "6VREG") (pin "3") (pinfunction "GND_3") (pintype "bidirectional"))
      (node (ref "ADC") (pin "1") (pinfunction "1_1") (pintype "bidirectional"))
      (node (ref "ANT1") (pin "GND1") (pinfunction "GND1_GND1") (pintype "bidirectional"))
      (node (ref "ANT1") (pin "GND2") (pinfunction "GND2_GND2") (pintype "bidirectional"))
      (node (ref "ANT2") (pin "GND1") (pinfunction "GND1_GND1") (pintype "bidirectional"))
      (node (ref "ANT2") (pin "GND2") (pinfunction "GND2_GND2") (pintype "bidirectional"))
      (node (ref "BMP") (pin "1") (pinfunction "GND_1") (pintype "power_in"))
      (node (ref "BMP") (pin "5") (pinfunction "SDO_5") (pintype "bidirectional"))
      (node (ref "BMP") (pin "7") (pinfunction "GND_7") (pintype "power_in"))
      (node (ref "C10") (pin "1") (pinfunction "1_1") (pintype "passive"))
      (node (ref "C11") (pin "-") (pinfunction "-_-") (pintype "passive"))
      (node (ref "C12") (pin "2") (pinfunction "2_2") (pintype "passive"))
      (node (ref "C13") (pin "2") (pinfunction "2_2") (pintype "passive"))
      (node (ref "C16") (pin "2") (pinfunction "2_2") (pintype "passive"))
      (node (ref "C2") (pin "1") (pinfunction "1_1") (pintype "passive"))
      (node (ref "C20") (pin "1") (pinfunction "1_1") (pintype "passive"))
      (node (ref "C21") (pin "1") (pinfunction "1_1") (pintype "passive"))
      (node (ref "C23") (pin "1") (pinfunction "1_1") (pintype "passive"))
      (node (ref "C24") (pin "1") (pinfunction "1_1") (pintype "passive"))
      (node (ref "C25") (pin "2") (pinfunction "2_2") (pintype "passive"))
      (node (ref "C26") (pin "2") (pinfunction "2_2") (pintype "passive"))
      (node (ref "C27") (pin "2") (pinfunction "2_2") (pintype "passive"))
      (node (ref "C28") (pin "2") (pinfunction "2_2") (pintype "passive"))
      (node (ref "C3") (pin "2") (pinfunction "2_2") (pintype "passive"))
      (node (ref "C33") (pin "2") (pinfunction "2_2") (pintype "passive"))
      (node (ref "C34") (pin "1") (pinfunction "1_1") (pintype "passive"))
      (node (ref "C35") (pin "1") (pinfunction "1_1") (pintype "passive"))
      (node (ref "C36") (pin "2") (pinfunction "2_2") (pintype "passive"))
      (node (ref "C37") (pin "2") (pinfunction "2_2") (pintype "passive"))
      (node (ref "C38") (pin "2") (pinfunction "2_2") (pintype "passive"))
      (node (ref "C39") (pin "2") (pinfunction "2_2") (pintype "passive"))
      (node (ref "C4") (pin "1") (pinfunction "1_1") (pintype "passive"))
      (node (ref "C40") (pin "2") (pinfunction "2_2") (pintype "passive"))
      (node (ref "C41") (pin "2") (pinfunction "2_2") (pintype "passive"))
      (node (ref "C45") (pin "2") (pinfunction "2_2") (pintype "passive"))
      (node (ref "C46") (pin "2") (pinfunction "2_2") (pintype "passive"))
      (node (ref "C47") (pin "2") (pinfunction "2_2") (pintype "passive"))
      (node (ref "C49") (pin "1") (pinfunction "1_1") (pintype "passive"))
      (node (ref "C5") (pin "2") (pinfunction "2_2") (pintype "passive"))
      (node (ref "C50") (pin "2") (pinfunction "2_2") (pintype "passive"))
      (node (ref "C51") (pin "1") (pinfunction "1_1") (pintype "passive"))
      (node (ref "C52") (pin "2") (pinfunction "2_2") (pintype "passive"))
      (node (ref "C53") (pin "2") (pinfunction "2_2") (pintype "passive"))
      (node (ref "C54") (pin "2") (pinfunction "2_2") (pintype "passive"))
      (node (ref "C55") (pin "2") (pinfunction "2_2") (pintype "passive"))
      (node (ref "C56") (pin "2") (pinfunction "2_2") (pintype "passive"))
      (node (ref "C57") (pin "1") (pinfunction "1_1") (pintype "passive"))
      (node (ref "C6") (pin "2") (pinfunction "2_2") (pintype "passive"))
      (node (ref "C7") (pin "2") (pinfunction "2_2") (pintype "passive"))
      (node (ref "C8") (pin "2") (pinfunction "2_2") (pintype "passive"))
      (node (ref "C9") (pin "1") (pinfunction "1_1") (pintype "passive"))
      (node (ref "CAN") (pin "1") (pinfunction "1_1") (pintype "bidirectional"))
      (node (ref "CHGIC") (pin "16") (pinfunction "PGND_16") (pintype "bidirectional"))
      (node (ref "CHGIC") (pin "8") (pinfunction "AGND_8") (pintype "bidirectional"))
      (node (ref "D1") (pin "A") (pinfunction "A_A") (pintype "passive"))
      (node (ref "D9") (pin "A") (pinfunction "A_A") (pintype "passive"))
      (node (ref "DSM2") (pin "P$2") (pinfunction "2_P$2") (pintype "bidirectional"))
      (node (ref "E1") (pin "1") (pinfunction "1_1") (pintype "bidirectional"))
      (node (ref "E2") (pin "1") (pinfunction "1_1") (pintype "bidirectional"))
      (node (ref "E3") (pin "1") (pinfunction "1_1") (pintype "bidirectional"))
      (node (ref "E4") (pin "1") (pinfunction "1_1") (pintype "bidirectional"))
      (node (ref "GP0") (pin "1") (pinfunction "1_1") (pintype "bidirectional"))
      (node (ref "GP1") (pin "4") (pinfunction "4_4") (pintype "bidirectional"))
      (node (ref "GPS") (pin "2") (pinfunction "2_2") (pintype "bidirectional"))
      (node (ref "GPS") (pin "6") (pinfunction "6_6") (pintype "bidirectional"))
      (node (ref "H1") (pin "10") (pinfunction "PGND2_10") (pintype "bidirectional"))
      (node (ref "H1") (pin "18") (pinfunction "GND_18") (pintype "bidirectional"))
      (node (ref "H1") (pin "3") (pinfunction "PGND1_3") (pintype "bidirectional"))
      (node (ref "H1") (pin "4") (pinfunction "PGND1_4") (pintype "bidirectional"))
      (node (ref "H1") (pin "9") (pinfunction "PGND2_9") (pintype "bidirectional"))
      (node (ref "H2") (pin "10") (pinfunction "PGND2_10") (pintype "bidirectional"))
      (node (ref "H2") (pin "18") (pinfunction "GND_18") (pintype "bidirectional"))
      (node (ref "H2") (pin "3") (pinfunction "PGND1_3") (pintype "bidirectional"))
      (node (ref "H2") (pin "4") (pinfunction "PGND1_4") (pintype "bidirectional"))
      (node (ref "H2") (pin "9") (pinfunction "PGND2_9") (pintype "bidirectional"))
      (node (ref "I2C1") (pin "4") (pinfunction "4_4") (pintype "bidirectional"))
      (node (ref "IMU") (pin "18") (pinfunction "GND_18") (pintype "bidirectional"))
      (node (ref "IMU") (pin "20") (pinfunction "RESV_20") (pintype "bidirectional"))
      (node (ref "IMU") (pin "9") (pinfunction "AD0/SDO_9") (pintype "bidirectional"))
      (node (ref "J2") (pin "P$13") (pinfunction "GND_P$13") (pintype "bidirectional"))
      (node (ref "J2") (pin "P$14") (pinfunction "GND_P$14") (pintype "bidirectional"))
      (node (ref "J2") (pin "P$15") (pinfunction "GND_P$15") (pintype "bidirectional"))
      (node (ref "J2") (pin "P$16") (pinfunction "GND_P$16") (pintype "bidirectional"))
      (node (ref "J2") (pin "P$17") (pinfunction "GND_P$17") (pintype "bidirectional"))
      (node (ref "J2") (pin "P$18") (pinfunction "GND_P$18") (pintype "bidirectional"))
      (node (ref "J2") (pin "P$23") (pinfunction "GND_P$23") (pintype "bidirectional"))
      (node (ref "J2") (pin "P$24") (pinfunction "GND_P$24") (pintype "bidirectional"))
      (node (ref "L4") (pin "1") (pinfunction "1_1") (pintype "passive"))
      (node (ref "MOD") (pin "1") (pinfunction "1_1") (pintype "passive"))
      (node (ref "OSC1") (pin "2") (pinfunction "GND_2") (pintype "bidirectional"))
      (node (ref "PAU") (pin "1") (pinfunction "1_1") (pintype "passive"))
      (node (ref "POW") (pin "1") (pinfunction "1_1") (pintype "passive"))
      (node (ref "PWR") (pin "1") (pinfunction "1_1") (pintype "bidirectional"))
      (node (ref "PWR") (pin "2") (pinfunction "2_2") (pintype "bidirectional"))
      (node (ref "Q1") (pin "5") (pinfunction "D_5") (pintype "passive"))
      (node (ref "Q1") (pin "6") (pinfunction "D_6") (pintype "passive"))
      (node (ref "Q1") (pin "7") (pinfunction "D_7") (pintype "passive"))
      (node (ref "Q1") (pin "8") (pinfunction "D_8") (pintype "passive"))
      (node (ref "R106") (pin "1") (pinfunction "1_1") (pintype "passive"))
      (node (ref "R107") (pin "1") (pinfunction "1_1") (pintype "passive"))
      (node (ref "R108") (pin "2") (pinfunction "2_2") (pintype "passive"))
      (node (ref "R110") (pin "2") (pinfunction "2_2") (pintype "passive"))
      (node (ref "R113") (pin "1") (pinfunction "1_1") (pintype "passive"))
      (node (ref "R115") (pin "1") (pinfunction "1_1") (pintype "passive"))
      (node (ref "R125") (pin "1") (pinfunction "1_1") (pintype "passive"))
      (node (ref "R127") (pin "1") (pinfunction "1_1") (pintype "passive"))
      (node (ref "R129") (pin "1") (pinfunction "1_1") (pintype "passive"))
      (node (ref "R131") (pin "1") (pinfunction "1_1") (pintype "passive"))
      (node (ref "R135") (pin "1") (pinfunction "1_1") (pintype "passive"))
      (node (ref "R14") (pin "2") (pinfunction "2_2") (pintype "passive"))
      (node (ref "R143") (pin "1") (pinfunction "1_1") (pintype "passive"))
      (node (ref "R150") (pin "2") (pinfunction "2_2") (pintype "passive"))
      (node (ref "R158") (pin "2") (pinfunction "2_2") (pintype "passive"))
      (node (ref "R16") (pin "1") (pinfunction "1_1") (pintype "passive"))
      (node (ref "R17") (pin "1") (pinfunction "1_1") (pintype "passive"))
      (node (ref "R21") (pin "2") (pinfunction "2_2") (pintype "passive"))
      (node (ref "R22") (pin "2") (pinfunction "2_2") (pintype "passive"))
      (node (ref "R24") (pin "2") (pinfunction "2_2") (pintype "passive"))
      (node (ref "R25") (pin "2") (pinfunction "2_2") (pintype "passive"))
      (node (ref "R29") (pin "2") (pinfunction "2_2") (pintype "passive"))
      (node (ref "R31") (pin "2") (pinfunction "2_2") (pintype "passive"))
      (node (ref "R32") (pin "2") (pinfunction "2_2") (pintype "passive"))
      (node (ref "R33") (pin "2") (pinfunction "2_2") (pintype "passive"))
      (node (ref "R46") (pin "1") (pinfunction "1_1") (pintype "passive"))
      (node (ref "R47") (pin "1") (pinfunction "1_1") (pintype "passive"))
      (node (ref "R48") (pin "1") (pinfunction "1_1") (pintype "passive"))
      (node (ref "R50") (pin "2") (pinfunction "2_2") (pintype "passive"))
      (node (ref "R51") (pin "2") (pinfunction "2_2") (pintype "passive"))
      (node (ref "R52") (pin "2") (pinfunction "2_2") (pintype "passive"))
      (node (ref "R53") (pin "2") (pinfunction "2_2") (pintype "passive"))
      (node (ref "R59") (pin "1") (pinfunction "1_1") (pintype "passive"))
      (node (ref "R6") (pin "1") (pinfunction "1_1") (pintype "passive"))
      (node (ref "R61") (pin "1") (pinfunction "1_1") (pintype "passive"))
      (node (ref "R62") (pin "1") (pinfunction "1_1") (pintype "passive"))
      (node (ref "R63") (pin "1") (pinfunction "1_1") (pintype "passive"))
      (node (ref "R64") (pin "1") (pinfunction "1_1") (pintype "passive"))
      (node (ref "R8") (pin "2") (pinfunction "2_2") (pintype "passive"))
      (node (ref "R87") (pin "2") (pinfunction "2_2") (pintype "passive"))
      (node (ref "R88") (pin "2") (pinfunction "2_2") (pintype "passive"))
      (node (ref "R89") (pin "2") (pinfunction "2_2") (pintype "passive"))
      (node (ref "RST") (pin "1") (pinfunction "1_1") (pintype "passive"))
      (node (ref "S1.1") (pin "1") (pinfunction "1_1") (pintype "bidirectional"))
      (node (ref "S1.2") (pin "1") (pinfunction "1_1") (pintype "bidirectional"))
      (node (ref "SD") (pin "1") (pinfunction "1_1") (pintype "passive"))
      (node (ref "SIP") (pin "A1") (pinfunction "DGND1_A1") (pintype "bidirectional"))
      (node (ref "SIP") (pin "A18") (pinfunction "DGND2_A18") (pintype "bidirectional"))
      (node (ref "SIP") (pin "E19") (pinfunction "DGND3_E19") (pintype "bidirectional"))
      (node (ref "SIP") (pin "E20") (pinfunction "DGND4_E20") (pintype "bidirectional"))
      (node (ref "SIP") (pin "F19") (pinfunction "DGND6_F19") (pintype "bidirectional"))
      (node (ref "SIP") (pin "F8") (pinfunction "DGND5_F8") (pintype "bidirectional"))
      (node (ref "SIP") (pin "G11") (pinfunction "DGND9_G11") (pintype "bidirectional"))
      (node (ref "SIP") (pin "G12") (pinfunction "DGND10_G12") (pintype "bidirectional"))
      (node (ref "SIP") (pin "G19") (pinfunction "DGND11_G19") (pintype "bidirectional"))
      (node (ref "SIP") (pin "G8") (pinfunction "DGND7_G8") (pintype "bidirectional"))
      (node (ref "SIP") (pin "G9") (pinfunction "DGND8_G9") (pintype "bidirectional"))
      (node (ref "SIP") (pin "H10") (pinfunction "DGND16_H10") (pintype "bidirectional"))
      (node (ref "SIP") (pin "H12") (pinfunction "DGND17_H12") (pintype "bidirectional"))
      (node (ref "SIP") (pin "H19") (pinfunction "DGND18_H19") (pintype "bidirectional"))
      (node (ref "SIP") (pin "H6") (pinfunction "DGND12_H6") (pintype "bidirectional"))
      (node (ref "SIP") (pin "H7") (pinfunction "DGND13_H7") (pintype "bidirectional"))
      (node (ref "SIP") (pin "H8") (pinfunction "DGND14_H8") (pintype "bidirectional"))
      (node (ref "SIP") (pin "H9") (pinfunction "DGND15_H9") (pintype "bidirectional"))
      (node (ref "SIP") (pin "J10") (pinfunction "DGND23_J10") (pintype "bidirectional"))
      (node (ref "SIP") (pin "J11") (pinfunction "DGND24_J11") (pintype "bidirectional"))
      (node (ref "SIP") (pin "J19") (pinfunction "DGND25_J19") (pintype "bidirectional"))
      (node (ref "SIP") (pin "J20") (pinfunction "DGND26_J20") (pintype "bidirectional"))
      (node (ref "SIP") (pin "J6") (pinfunction "DGND19_J6") (pintype "bidirectional"))
      (node (ref "SIP") (pin "J7") (pinfunction "DGND20_J7") (pintype "bidirectional"))
      (node (ref "SIP") (pin "J8") (pinfunction "DGND21_J8") (pintype "bidirectional"))
      (node (ref "SIP") (pin "J9") (pinfunction "DGND22_J9") (pintype "bidirectional"))
      (node (ref "SIP") (pin "K10") (pinfunction "DGND29_K10") (pintype "bidirectional"))
      (node (ref "SIP") (pin "K11") (pinfunction "DGND30_K11") (pintype "bidirectional"))
      (node (ref "SIP") (pin "K19") (pinfunction "DGND31_K19") (pintype "bidirectional"))
      (node (ref "SIP") (pin "K7") (pinfunction "DGND27_K7") (pintype "bidirectional"))
      (node (ref "SIP") (pin "K9") (pinfunction "DGND28_K9") (pintype "bidirectional"))
      (node (ref "SIP") (pin "L10") (pinfunction "DGND32_L10") (pintype "bidirectional"))
      (node (ref "SIP") (pin "L11") (pinfunction "DGND33_L11") (pintype "bidirectional"))
      (node (ref "SIP") (pin "L12") (pinfunction "DGND34_L12") (pintype "bidirectional"))
      (node (ref "SIP") (pin "L13") (pinfunction "DGND35_L13") (pintype "bidirectional"))
      (node (ref "SIP") (pin "L19") (pinfunction "DGND36_L19") (pintype "bidirectional"))
      (node (ref "SIP") (pin "M10") (pinfunction "DGND42_M10") (pintype "bidirectional"))
      (node (ref "SIP") (pin "M12") (pinfunction "DGND43_M12") (pintype "bidirectional"))
      (node (ref "SIP") (pin "M14") (pinfunction "DGND44_M14") (pintype "bidirectional"))
      (node (ref "SIP") (pin "M19") (pinfunction "DGND45_M19") (pintype "bidirectional"))
      (node (ref "SIP") (pin "M6") (pinfunction "DGND38_M6") (pintype "bidirectional"))
      (node (ref "SIP") (pin "M7") (pinfunction "DGND39_M7") (pintype "bidirectional"))
      (node (ref "SIP") (pin "M8") (pinfunction "DGND40_M8") (pintype "bidirectional"))
      (node (ref "SIP") (pin "M9") (pinfunction "DGND41_M9") (pintype "bidirectional"))
      (node (ref "SIP") (pin "N10") (pinfunction "DGND47_N10") (pintype "bidirectional"))
      (node (ref "SIP") (pin "N11") (pinfunction "DGND48_N11") (pintype "bidirectional"))
      (node (ref "SIP") (pin "N14") (pinfunction "DGND49_N14") (pintype "bidirectional"))
      (node (ref "SIP") (pin "N19") (pinfunction "DGND50_N19") (pintype "bidirectional"))
      (node (ref "SIP") (pin "N20") (pinfunction "DGND51_N20") (pintype "bidirectional"))
      (node (ref "SIP") (pin "N7") (pinfunction "DGND46_N7") (pintype "bidirectional"))
      (node (ref "SIP") (pin "P19") (pinfunction "DGND52_P19") (pintype "bidirectional"))
      (node (ref "SIP") (pin "P20") (pinfunction "DGND53_P20") (pintype "bidirectional"))
      (node (ref "SIP") (pin "R19") (pinfunction "DGND54_R19") (pintype "bidirectional"))
      (node (ref "SIP") (pin "R20") (pinfunction "DGND55_R20") (pintype "bidirectional"))
      (node (ref "SIP") (pin "T19") (pinfunction "DGND56_T19") (pintype "bidirectional"))
      (node (ref "SIP") (pin "T20") (pinfunction "DGND57_T20") (pintype "bidirectional"))
      (node (ref "SIP") (pin "U19") (pinfunction "DGND58_U19") (pintype "bidirectional"))
      (node (ref "SIP") (pin "V1") (pinfunction "DGND59_V1") (pintype "bidirectional"))
      (node (ref "SIP") (pin "V18") (pinfunction "DGND60_V18") (pintype "bidirectional"))
      (node (ref "SIP") (pin "V19") (pinfunction "DGND61_V19") (pintype "bidirectional"))
      (node (ref "SIP") (pin "W10") (pinfunction "DGND70_W10") (pintype "bidirectional"))
      (node (ref "SIP") (pin "W11") (pinfunction "DGND71_W11") (pintype "bidirectional"))
      (node (ref "SIP") (pin "W12") (pinfunction "DGND72_W12") (pintype "bidirectional"))
      (node (ref "SIP") (pin "W13") (pinfunction "DGND73_W13") (pintype "bidirectional"))
      (node (ref "SIP") (pin "W14") (pinfunction "DGND74_W14") (pintype "bidirectional"))
      (node (ref "SIP") (pin "W15") (pinfunction "DGND75_W15") (pintype "bidirectional"))
      (node (ref "SIP") (pin "W16") (pinfunction "DGND76_W16") (pintype "bidirectional"))
      (node (ref "SIP") (pin "W17") (pinfunction "DGND77_W17") (pintype "bidirectional"))
      (node (ref "SIP") (pin "W18") (pinfunction "DGND78_W18") (pintype "bidirectional"))
      (node (ref "SIP") (pin "W19") (pinfunction "DGND79_W19") (pintype "bidirectional"))
      (node (ref "SIP") (pin "W2") (pinfunction "DGND62_W2") (pintype "bidirectional"))
      (node (ref "SIP") (pin "W20") (pinfunction "DGND80_W20") (pintype "bidirectional"))
      (node (ref "SIP") (pin "W3") (pinfunction "DGND63_W3") (pintype "bidirectional"))
      (node (ref "SIP") (pin "W5") (pinfunction "DGND65_W5") (pintype "bidirectional"))
      (node (ref "SIP") (pin "W6") (pinfunction "DGND66_W6") (pintype "bidirectional"))
      (node (ref "SIP") (pin "W7") (pinfunction "DGND67_W7") (pintype "bidirectional"))
      (node (ref "SIP") (pin "W8") (pinfunction "DGND68_W8") (pintype "bidirectional"))
      (node (ref "SIP") (pin "W9") (pinfunction "DGND69_W9") (pintype "bidirectional"))
      (node (ref "SIP") (pin "Y10") (pinfunction "DGND83_Y10") (pintype "bidirectional"))
      (node (ref "SIP") (pin "Y12") (pinfunction "DGND84_Y12") (pintype "bidirectional"))
      (node (ref "SIP") (pin "Y15") (pinfunction "DGND85_Y15") (pintype "bidirectional"))
      (node (ref "SIP") (pin "Y18") (pinfunction "DGND86_Y18") (pintype "bidirectional"))
      (node (ref "SIP") (pin "Y7") (pinfunction "DGND82_Y7") (pintype "bidirectional"))
      (node (ref "T1") (pin "S") (pinfunction "S_S") (pintype "bidirectional"))
      (node (ref "T2") (pin "S") (pinfunction "S_S") (pintype "bidirectional"))
      (node (ref "TP12") (pin "TP") (pinfunction "TP_TP") (pintype "input"))
      (node (ref "U1") (pin "2") (pinfunction "GND_2") (pintype "power_in"))
      (node (ref "U10") (pin "11") (pinfunction "GND_11") (pintype "bidirectional"))
      (node (ref "U10") (pin "TP") (pinfunction "TP_TP") (pintype "bidirectional"))
      (node (ref "U13") (pin "C4") (pinfunction "VSSQ1_C4") (pintype "bidirectional"))
      (node (ref "U13") (pin "E7") (pinfunction "VSS1_E7") (pintype "bidirectional"))
      (node (ref "U13") (pin "G5") (pinfunction "VSS2_G5") (pintype "bidirectional"))
      (node (ref "U13") (pin "H10") (pinfunction "VSS3_H10") (pintype "bidirectional"))
      (node (ref "U13") (pin "K8") (pinfunction "VSS4_K8") (pintype "bidirectional"))
      (node (ref "U13") (pin "N2") (pinfunction "VSSQ2_N2") (pintype "bidirectional"))
      (node (ref "U13") (pin "N5") (pinfunction "VSSQ3_N5") (pintype "bidirectional"))
      (node (ref "U13") (pin "P4") (pinfunction "VSSQ4_P4") (pintype "bidirectional"))
      (node (ref "U13") (pin "P6") (pinfunction "VSSQ5_P6") (pintype "bidirectional"))
      (node (ref "U2") (pin "3") (pinfunction "GND_3") (pintype "power_in"))
      (node (ref "U3") (pin "4") (pinfunction "GND_4") (pintype "bidirectional"))
      (node (ref "U4") (pin "4") (pinfunction "GND_4") (pintype "bidirectional"))
      (node (ref "U5") (pin "2") (pinfunction "VSS_2") (pintype "passive"))
      (node (ref "U6") (pin "3") (pinfunction "GND_3") (pintype "power_in"))
      (node (ref "U7") (pin "1") (pinfunction "GND1_1") (pintype "bidirectional"))
      (node (ref "U7") (pin "15") (pinfunction "GND4_15") (pintype "bidirectional"))
      (node (ref "U7") (pin "16") (pinfunction "GND5_16") (pintype "bidirectional"))
      (node (ref "U7") (pin "17") (pinfunction "GND6_17") (pintype "bidirectional"))
      (node (ref "U7") (pin "19") (pinfunction "GND7_19") (pintype "bidirectional"))
      (node (ref "U7") (pin "20") (pinfunction "GND8_20") (pintype "bidirectional"))
      (node (ref "U7") (pin "23") (pinfunction "GND9_23") (pintype "bidirectional"))
      (node (ref "U7") (pin "24") (pinfunction "GND10_24") (pintype "bidirectional"))
      (node (ref "U7") (pin "28") (pinfunction "GND11_28") (pintype "bidirectional"))
      (node (ref "U7") (pin "29") (pinfunction "GND12_29") (pintype "bidirectional"))
      (node (ref "U7") (pin "30") (pinfunction "GND13_30") (pintype "bidirectional"))
      (node (ref "U7") (pin "31") (pinfunction "GND14_31") (pintype "bidirectional"))
      (node (ref "U7") (pin "33") (pinfunction "GND15_33") (pintype "bidirectional"))
      (node (ref "U7") (pin "34") (pinfunction "GND16_34") (pintype "bidirectional"))
      (node (ref "U7") (pin "35") (pinfunction "GND17_35") (pintype "bidirectional"))
      (node (ref "U7") (pin "37") (pinfunction "GND18_37") (pintype "bidirectional"))
      (node (ref "U7") (pin "39") (pinfunction "GND19_39") (pintype "bidirectional"))
      (node (ref "U7") (pin "44") (pinfunction "GND20_44") (pintype "bidirectional"))
      (node (ref "U7") (pin "45") (pinfunction "GND21_45") (pintype "bidirectional"))
      (node (ref "U7") (pin "48") (pinfunction "GND22_48") (pintype "bidirectional"))
      (node (ref "U7") (pin "49") (pinfunction "GND23_49") (pintype "bidirectional"))
      (node (ref "U7") (pin "54") (pinfunction "GND24_54") (pintype "bidirectional"))
      (node (ref "U7") (pin "55") (pinfunction "GND25_55") (pintype "bidirectional"))
      (node (ref "U7") (pin "59") (pinfunction "GND26_59") (pintype "bidirectional"))
      (node (ref "U7") (pin "61") (pinfunction "GND27_61") (pintype "bidirectional"))
      (node (ref "U7") (pin "63") (pinfunction "GND28_63") (pintype "bidirectional"))
      (node (ref "U7") (pin "64") (pinfunction "GND29_64") (pintype "bidirectional"))
      (node (ref "U7") (pin "7") (pinfunction "GND2_7") (pintype "bidirectional"))
      (node (ref "U7") (pin "9") (pinfunction "GND3_9") (pintype "bidirectional"))
      (node (ref "U7") (pin "G1") (pinfunction "G1_G1") (pintype "bidirectional"))
      (node (ref "U7") (pin "G10") (pinfunction "G10_G10") (pintype "bidirectional"))
      (node (ref "U7") (pin "G11") (pinfunction "G11_G11") (pintype "bidirectional"))
      (node (ref "U7") (pin "G12") (pinfunction "G12_G12") (pintype "bidirectional"))
      (node (ref "U7") (pin "G13") (pinfunction "G13_G13") (pintype "bidirectional"))
      (node (ref "U7") (pin "G14") (pinfunction "G14_G14") (pintype "bidirectional"))
      (node (ref "U7") (pin "G15") (pinfunction "G15_G15") (pintype "bidirectional"))
      (node (ref "U7") (pin "G16") (pinfunction "G16_G16") (pintype "bidirectional"))
      (node (ref "U7") (pin "G17") (pinfunction "G17_G17") (pintype "bidirectional"))
      (node (ref "U7") (pin "G18") (pinfunction "G18_G18") (pintype "bidirectional"))
      (node (ref "U7") (pin "G19") (pinfunction "G19_G19") (pintype "bidirectional"))
      (node (ref "U7") (pin "G2") (pinfunction "G2_G2") (pintype "bidirectional"))
      (node (ref "U7") (pin "G20") (pinfunction "G20_G20") (pintype "bidirectional"))
      (node (ref "U7") (pin "G21") (pinfunction "G21_G21") (pintype "bidirectional"))
      (node (ref "U7") (pin "G22") (pinfunction "G22_G22") (pintype "bidirectional"))
      (node (ref "U7") (pin "G23") (pinfunction "G23_G23") (pintype "bidirectional"))
      (node (ref "U7") (pin "G24") (pinfunction "G24_G24") (pintype "bidirectional"))
      (node (ref "U7") (pin "G25") (pinfunction "G25_G25") (pintype "bidirectional"))
      (node (ref "U7") (pin "G26") (pinfunction "G26_G26") (pintype "bidirectional"))
      (node (ref "U7") (pin "G27") (pinfunction "G27_G27") (pintype "bidirectional"))
      (node (ref "U7") (pin "G28") (pinfunction "G28_G28") (pintype "bidirectional"))
      (node (ref "U7") (pin "G29") (pinfunction "G29_G29") (pintype "bidirectional"))
      (node (ref "U7") (pin "G3") (pinfunction "G3_G3") (pintype "bidirectional"))
      (node (ref "U7") (pin "G30") (pinfunction "G30_G30") (pintype "bidirectional"))
      (node (ref "U7") (pin "G31") (pinfunction "G31_G31") (pintype "bidirectional"))
      (node (ref "U7") (pin "G32") (pinfunction "G32_G32") (pintype "bidirectional"))
      (node (ref "U7") (pin "G33") (pinfunction "G33_G33") (pintype "bidirectional"))
      (node (ref "U7") (pin "G34") (pinfunction "G34_G34") (pintype "bidirectional"))
      (node (ref "U7") (pin "G35") (pinfunction "G35_G35") (pintype "bidirectional"))
      (node (ref "U7") (pin "G36") (pinfunction "G36_G36") (pintype "bidirectional"))
      (node (ref "U7") (pin "G4") (pinfunction "G4_G4") (pintype "bidirectional"))
      (node (ref "U7") (pin "G5") (pinfunction "G5_G5") (pintype "bidirectional"))
      (node (ref "U7") (pin "G6") (pinfunction "G6_G6") (pintype "bidirectional"))
      (node (ref "U7") (pin "G7") (pinfunction "G7_G7") (pintype "bidirectional"))
      (node (ref "U7") (pin "G8") (pinfunction "G8_G8") (pintype "bidirectional"))
      (node (ref "U7") (pin "G9") (pinfunction "G9_G9") (pintype "bidirectional"))
      (node (ref "U9") (pin "11") (pinfunction "GND_11") (pintype "bidirectional"))
      (node (ref "U9") (pin "TP") (pinfunction "TP_TP") (pintype "bidirectional"))
      (node (ref "UT0") (pin "1") (pinfunction "1_1") (pintype "bidirectional"))
      (node (ref "UT1") (pin "1") (pinfunction "1_1") (pintype "bidirectional"))
      (node (ref "UT5") (pin "4") (pinfunction "4_4") (pintype "bidirectional"))
      (node (ref "X2") (pin "6") (pinfunction "VSS_6") (pintype "bidirectional"))
      (node (ref "X2") (pin "GND") (pinfunction "GND_GND") (pintype "bidirectional"))
      (node (ref "X4") (pin "GND") (pinfunction "GND_GND") (pintype "input"))
    )
    (net (code "40") (name "GNDA_ADC") (class "Default")
      (node (ref "C42") (pin "2") (pinfunction "2_2") (pintype "passive"))
      (node (ref "C43") (pin "2") (pinfunction "2_2") (pintype "passive"))
      (node (ref "C44") (pin "2") (pinfunction "2_2") (pintype "passive"))
      (node (ref "SIP") (pin "A6") (pinfunction "VSSA_ADC_0_A6") (pintype "bidirectional"))
      (node (ref "SIP") (pin "A9") (pinfunction "VSSA_ADC_1_A9") (pintype "bidirectional"))
      (node (ref "SIP") (pin "E8") (pinfunction "VSSA_ADC_2_E8") (pintype "bidirectional"))
    )
    (net (code "41") (name "GPIO_0_0") (class "Default")
      (node (ref "GP0") (pin "3") (pinfunction "3_3") (pintype "bidirectional"))
      (node (ref "SIP") (pin "U16") (pinfunction "HDMIINT_GPIO1_25_U16_U16") (pintype "bidirectional"))
    )
    (net (code "42") (name "GPIO_0_1") (class "Default")
      (node (ref "GP0") (pin "4") (pinfunction "4_4") (pintype "bidirectional"))
      (node (ref "SIP") (pin "V14") (pinfunction "GPIO1_17_V14_V14") (pintype "bidirectional"))
    )
    (net (code "43") (name "GPIO_0_2") (class "Default")
      (node (ref "GP0") (pin "5") (pinfunction "5_5") (pintype "bidirectional"))
      (node (ref "SIP") (pin "D13") (pinfunction "GPIO3_20_D13_D13") (pintype "bidirectional"))
    )
    (net (code "44") (name "GPIO_0_3") (class "Default")
      (node (ref "GP0") (pin "6") (pinfunction "6_6") (pintype "bidirectional"))
      (node (ref "SIP") (pin "C18") (pinfunction "GPIO0_7_C18_C18") (pintype "bidirectional"))
    )
    (net (code "45") (name "GPIO_1_0") (class "Default")
      (node (ref "GP1") (pin "1") (pinfunction "1_1") (pintype "bidirectional"))
      (node (ref "SIP") (pin "J15") (pinfunction "J15_J15") (pintype "bidirectional"))
    )
    (net (code "46") (name "GPIO_1_1") (class "Default")
      (node (ref "GP1") (pin "2") (pinfunction "2_2") (pintype "bidirectional"))
      (node (ref "SIP") (pin "H17") (pinfunction "H17_H17") (pintype "bidirectional"))
    )
    (net (code "47") (name "I2C0_SCL") (class "Default")
      (node (ref "R23") (pin "1") (pinfunction "1_1") (pintype "passive"))
      (node (ref "SIP") (pin "C16") (pinfunction "I2C0_SCL_C16") (pintype "bidirectional"))
      (node (ref "SIP") (pin "C20") (pinfunction "PMIC_I2C_SCL_C20") (pintype "bidirectional"))
      (node (ref "U5") (pin "1") (pinfunction "SCL_1") (pintype "input"))
    )
    (net (code "48") (name "I2C0_SDA") (class "Default")
      (node (ref "R2") (pin "1") (pinfunction "1_1") (pintype "passive"))
      (node (ref "SIP") (pin "C17") (pinfunction "I2C0_SDA_C17") (pintype "bidirectional"))
      (node (ref "SIP") (pin "C19") (pinfunction "PMIC_I2C_SDA_C19") (pintype "bidirectional"))
      (node (ref "U5") (pin "3") (pinfunction "SDA_3") (pintype "bidirectional"))
    )
    (net (code "49") (name "I2C1_SCL") (class "Default")
      (node (ref "I2C1") (pin "1") (pinfunction "1_1") (pintype "bidirectional"))
      (node (ref "R12") (pin "1") (pinfunction "1_1") (pintype "passive"))
      (node (ref "SIP") (pin "A16") (pinfunction "I2C1_SCL_A16_A16") (pintype "bidirectional"))
    )
    (net (code "50") (name "I2C1_SDA") (class "Default")
      (node (ref "I2C1") (pin "2") (pinfunction "2_2") (pintype "bidirectional"))
      (node (ref "R13") (pin "2") (pinfunction "2_2") (pintype "passive"))
      (node (ref "SIP") (pin "B16") (pinfunction "I2C1_SDA_B16_B16") (pintype "bidirectional"))
    )
    (net (code "51") (name "I2C2_SCL") (class "Default")
      (node (ref "BMP") (pin "4") (pinfunction "SCK_4") (pintype "input"))
      (node (ref "IMU") (pin "23") (pinfunction "SCL/SCLK_23") (pintype "bidirectional"))
      (node (ref "R11") (pin "1") (pinfunction "1_1") (pintype "passive"))
      (node (ref "SIP") (pin "D17") (pinfunction "I2C2_SCL_D17_D17") (pintype "bidirectional"))
    )
    (net (code "52") (name "I2C2_SDA") (class "Default")
      (node (ref "BMP") (pin "3") (pinfunction "SDI_3") (pintype "bidirectional"))
      (node (ref "IMU") (pin "24") (pinfunction "SDA/SDI_24") (pintype "bidirectional"))
      (node (ref "R10") (pin "2") (pinfunction "2_2") (pintype "passive"))
      (node (ref "SIP") (pin "D18") (pinfunction "I2C2_SDA_D18_D18") (pintype "bidirectional"))
    )
    (net (code "53") (name "IMU_INT") (class "Default")
      (node (ref "IMU") (pin "12") (pinfunction "INT_12") (pintype "bidirectional"))
      (node (ref "SIP") (pin "A14") (pinfunction "GPIO3_21_A14_A14") (pintype "bidirectional"))
    )
    (net (code "54") (name "LDO_PGOOD") (class "Default")
      (node (ref "SIP") (pin "B20") (pinfunction "PMIC_OUT_LDO_PGOOD_B20") (pintype "output"))
      (node (ref "SIP") (pin "B5") (pinfunction "RTC_PWRONRSTN_B5") (pintype "bidirectional"))
    )
    (net (code "55") (name "LED_GRN") (class "Default")
      (node (ref "G") (pin "A") (pinfunction "A_A") (pintype "passive"))
      (node (ref "SIP") (pin "T7") (pinfunction "TIMER7_T7_T7") (pintype "bidirectional"))
    )
    (net (code "56") (name "LED_RED") (class "Default")
      (node (ref "R") (pin "A") (pinfunction "A_A") (pintype "passive"))
      (node (ref "SIP") (pin "R7") (pinfunction "TIMER4_R7_R7") (pintype "bidirectional"))
    )
    (net (code "57") (name "MCASP0_ACLKR") (class "Default")
      (node (ref "SIP") (pin "U18") (pinfunction "GPIO1_28_U18_U18") (pintype "bidirectional"))
      (node (ref "U10") (pin "20") (pinfunction "B1_20") (pintype "bidirectional"))
    )
    (net (code "58") (name "MCASP0_AXR0") (class "Default")
      (node (ref "SIP") (pin "T16") (pinfunction "USB1OC_GPIO1_26_T16_T16") (pintype "bidirectional"))
      (node (ref "U10") (pin "17") (pinfunction "B3_17") (pintype "bidirectional"))
    )
    (net (code "59") (name "MCASP0_AXR1") (class "Default")
      (node (ref "SIP") (pin "V17") (pinfunction "HDMIDIS_GPIO1_27_V17_V17") (pintype "bidirectional"))
      (node (ref "U10") (pin "16") (pinfunction "B4_16") (pintype "bidirectional"))
    )
    (net (code "60") (name "MCASP0_FSR") (class "Default")
      (node (ref "SIP") (pin "V12") (pinfunction "GPIO2_1_V12_V12") (pintype "bidirectional"))
      (node (ref "U10") (pin "18") (pinfunction "B2_18") (pintype "bidirectional"))
    )
    (net (code "61") (name "MDIR_1A") (class "Default")
      (node (ref "H1") (pin "21") (pinfunction "AIN1_21") (pintype "bidirectional"))
      (node (ref "SIP") (pin "T13") (pinfunction "GPIO2_0_T13_T13") (pintype "bidirectional"))
    )
    (net (code "62") (name "MDIR_1B") (class "Default")
      (node (ref "H1") (pin "22") (pinfunction "AIN2_22") (pintype "bidirectional"))
      (node (ref "SIP") (pin "U17") (pinfunction "UART4_TXD_U17_U17") (pintype "bidirectional"))
    )
    (net (code "63") (name "MDIR_2A") (class "Default")
      (node (ref "H1") (pin "17") (pinfunction "BIN1_17") (pintype "bidirectional"))
      (node (ref "SIP") (pin "R13") (pinfunction "GPIO1_16_R13_R13") (pintype "bidirectional"))
    )
    (net (code "64") (name "MDIR_2B") (class "Default")
      (node (ref "H1") (pin "16") (pinfunction "BIN2_16") (pintype "bidirectional"))
      (node (ref "R131") (pin "2") (pinfunction "2_2") (pintype "passive"))
      (node (ref "SIP") (pin "U2") (pinfunction "LCD_DATA9_U2_U2") (pintype "bidirectional"))
    )
    (net (code "65") (name "MDIR_3A") (class "Default")
      (node (ref "H2") (pin "21") (pinfunction "AIN1_21") (pintype "bidirectional"))
      (node (ref "R118") (pin "1") (pinfunction "1_1") (pintype "passive"))
      (node (ref "SIP") (pin "R4") (pinfunction "LCD_DATA3_R4_R4") (pintype "bidirectional"))
    )
    (net (code "66") (name "MDIR_3B") (class "Default")
      (node (ref "H2") (pin "22") (pinfunction "AIN2_22") (pintype "bidirectional"))
      (node (ref "R116") (pin "1") (pinfunction "1_1") (pintype "passive"))
      (node (ref "R77") (pin "1") (pinfunction "1_1") (pintype "passive"))
      (node (ref "SIP") (pin "R3") (pinfunction "LCD_DATA2_R3_R3") (pintype "bidirectional"))
    )
    (net (code "67") (name "MDIR_4A") (class "Default")
      (node (ref "H2") (pin "17") (pinfunction "BIN1_17") (pintype "bidirectional"))
      (node (ref "R113") (pin "2") (pinfunction "2_2") (pintype "passive"))
      (node (ref "SIP") (pin "R1") (pinfunction "LCD_DATA0_R1_R1") (pintype "bidirectional"))
    )
    (net (code "68") (name "MDIR_4B") (class "Default")
      (node (ref "H2") (pin "16") (pinfunction "BIN2_16") (pintype "bidirectional"))
      (node (ref "R115") (pin "2") (pinfunction "2_2") (pintype "passive"))
      (node (ref "SIP") (pin "R2") (pinfunction "LCD_DATA1_R2_R2") (pintype "bidirectional"))
    )
    (net (code "69") (name "MMC1_CLK") (class "Default")
      (node (ref "R15") (pin "2") (pinfunction "2_2") (pintype "passive"))
      (node (ref "R66") (pin "1") (pinfunction "1_1") (pintype "passive"))
      (node (ref "U13") (pin "M6") (pinfunction "CLK_M6") (pintype "bidirectional"))
    )
    (net (code "70") (name "MMC1_CMD") (class "Default")
      (node (ref "R67") (pin "1") (pinfunction "1_1") (pintype "passive"))
      (node (ref "SIP") (pin "V9") (pinfunction "MMC1_CMD_V9_V9") (pintype "bidirectional"))
      (node (ref "U13") (pin "M5") (pinfunction "CMD_M5") (pintype "bidirectional"))
    )
    (net (code "71") (name "MMC1_DAT0") (class "Default")
      (node (ref "R68") (pin "1") (pinfunction "1_1") (pintype "passive"))
      (node (ref "SIP") (pin "U7") (pinfunction "MMC1_DAT0_U7_U7") (pintype "bidirectional"))
      (node (ref "U13") (pin "A3") (pinfunction "DAT0_A3") (pintype "bidirectional"))
    )
    (net (code "72") (name "MMC1_DAT1") (class "Default")
      (node (ref "R69") (pin "1") (pinfunction "1_1") (pintype "passive"))
      (node (ref "SIP") (pin "V7") (pinfunction "MMC1_DAT1_V7_V7") (pintype "bidirectional"))
      (node (ref "U13") (pin "A4") (pinfunction "DAT1_A4") (pintype "bidirectional"))
    )
    (net (code "73") (name "MMC1_DAT2") (class "Default")
      (node (ref "R70") (pin "1") (pinfunction "1_1") (pintype "passive"))
      (node (ref "SIP") (pin "R8") (pinfunction "MMC1_DAT2_R8_R8") (pintype "bidirectional"))
      (node (ref "U13") (pin "A5") (pinfunction "DAT2_A5") (pintype "bidirectional"))
    )
    (net (code "74") (name "MMC1_DAT3") (class "Default")
      (node (ref "R71") (pin "1") (pinfunction "1_1") (pintype "passive"))
      (node (ref "SIP") (pin "T8") (pinfunction "MMC1_DAT3_T8_T8") (pintype "bidirectional"))
      (node (ref "U13") (pin "B2") (pinfunction "DAT3_B2") (pintype "bidirectional"))
    )
    (net (code "75") (name "MMC1_DAT4") (class "Default")
      (node (ref "R72") (pin "1") (pinfunction "1_1") (pintype "passive"))
      (node (ref "SIP") (pin "U8") (pinfunction "MMC1_DAT4_U8_U8") (pintype "bidirectional"))
      (node (ref "U13") (pin "B3") (pinfunction "DAT4_B3") (pintype "bidirectional"))
    )
    (net (code "76") (name "MMC1_DAT5") (class "Default")
      (node (ref "R73") (pin "1") (pinfunction "1_1") (pintype "passive"))
      (node (ref "SIP") (pin "V8") (pinfunction "MMC1_DAT5_V8_V8") (pintype "bidirectional"))
      (node (ref "U13") (pin "B4") (pinfunction "DAT5_B4") (pintype "bidirectional"))
    )
    (net (code "77") (name "MMC1_DAT6") (class "Default")
      (node (ref "R74") (pin "1") (pinfunction "1_1") (pintype "passive"))
      (node (ref "SIP") (pin "R9") (pinfunction "MMC1_DAT6_R9_R9") (pintype "bidirectional"))
      (node (ref "U13") (pin "B5") (pinfunction "DAT6_B5") (pintype "bidirectional"))
    )
    (net (code "78") (name "MMC1_DAT7") (class "Default")
      (node (ref "R75") (pin "1") (pinfunction "1_1") (pintype "passive"))
      (node (ref "SIP") (pin "T9") (pinfunction "MMC1_DAT7_T9_T9") (pintype "bidirectional"))
      (node (ref "U13") (pin "B6") (pinfunction "DAT7_B6") (pintype "bidirectional"))
    )
    (net (code "79") (name "MMC2_CLK") (class "Default")
      (node (ref "R76") (pin "1") (pinfunction "1_1") (pintype "passive"))
      (node (ref "U9") (pin "13") (pinfunction "B7_13") (pintype "bidirectional"))
    )
    (net (code "80") (name "MMC2_CMD") (class "Default")
      (node (ref "SIP") (pin "J16") (pinfunction "J16_J16") (pintype "bidirectional"))
      (node (ref "U9") (pin "12") (pinfunction "B8_12") (pintype "bidirectional"))
    )
    (net (code "81") (name "MMC2_DAT0") (class "Default")
      (node (ref "SIP") (pin "J17") (pinfunction "J17_J17") (pintype "bidirectional"))
      (node (ref "U9") (pin "14") (pinfunction "B6_14") (pintype "bidirectional"))
    )
    (net (code "82") (name "MMC2_DAT1") (class "Default")
      (node (ref "SIP") (pin "J18") (pinfunction "J18_J18") (pintype "bidirectional"))
      (node (ref "U9") (pin "15") (pinfunction "B5_15") (pintype "bidirectional"))
    )
    (net (code "83") (name "MMC2_DAT2") (class "Default")
      (node (ref "SIP") (pin "K15") (pinfunction "K15_K15") (pintype "bidirectional"))
      (node (ref "U9") (pin "16") (pinfunction "B4_16") (pintype "bidirectional"))
    )
    (net (code "84") (name "MMC2_DAT3") (class "Default")
      (node (ref "SIP") (pin "H16") (pinfunction "H16_H16") (pintype "bidirectional"))
      (node (ref "U9") (pin "17") (pinfunction "B3_17") (pintype "bidirectional"))
    )
    (net (code "85") (name "MODE_BTN") (class "Default")
      (node (ref "MOD") (pin "2") (pinfunction "2_2") (pintype "passive"))
      (node (ref "SIP") (pin "U6") (pinfunction "TIMER6_U6_U6") (pintype "bidirectional"))
    )
    (net (code "86") (name "MOT_STBY") (class "Default")
      (node (ref "H1") (pin "19") (pinfunction "STBY_19") (pintype "bidirectional"))
      (node (ref "H2") (pin "19") (pinfunction "STBY_19") (pintype "bidirectional"))
      (node (ref "SIP") (pin "D14") (pinfunction "GPIO0_20_D14_D14") (pintype "bidirectional"))
    )
    (net (code "87") (name "Net-(0-PadC)") (class "Default")
      (node (ref "0") (pin "C") (pinfunction "C_C") (pintype "passive"))
      (node (ref "R61") (pin "2") (pinfunction "2_2") (pintype "passive"))
    )
    (net (code "88") (name "Net-(1-PadC)") (class "Default")
      (node (ref "1") (pin "C") (pinfunction "C_C") (pintype "passive"))
      (node (ref "R62") (pin "2") (pinfunction "2_2") (pintype "passive"))
    )
    (net (code "89") (name "Net-(2-PadC)") (class "Default")
      (node (ref "2") (pin "C") (pinfunction "C_C") (pintype "passive"))
      (node (ref "R63") (pin "2") (pinfunction "2_2") (pintype "passive"))
    )
    (net (code "90") (name "Net-(3-PadC)") (class "Default")
      (node (ref "3") (pin "C") (pinfunction "C_C") (pintype "passive"))
      (node (ref "R64") (pin "2") (pinfunction "2_2") (pintype "passive"))
    )
    (net (code "91") (name "Net-(5VREG-OUT)") (class "Default")
      (node (ref "5VREG") (pin "2") (pinfunction "OUT_2") (pintype "power_in"))
      (node (ref "D1") (pin "C") (pinfunction "C_C") (pintype "passive"))
      (node (ref "L1") (pin "1") (pinfunction "1_1") (pintype "passive"))
    )
    (net (code "92") (name "Net-(5VREG-VIN)") (class "Default")
      (node (ref "5VREG") (pin "1") (pinfunction "VIN_1") (pintype "input"))
      (node (ref "C3") (pin "1") (pinfunction "1_1") (pintype "passive"))
      (node (ref "D2") (pin "C") (pinfunction "C_C") (pintype "passive"))
      (node (ref "D3") (pin "C") (pinfunction "C_C") (pintype "passive"))
    )
    (net (code "93") (name "Net-(6VREG-BS)") (class "Default")
      (node (ref "6VREG") (pin "2") (pinfunction "BS_2") (pintype "bidirectional"))
      (node (ref "C22") (pin "1") (pinfunction "1_1") (pintype "passive"))
    )
    (net (code "94") (name "Net-(6VREG-COMP)") (class "Default")
      (node (ref "6VREG") (pin "5") (pinfunction "COMP_5") (pintype "bidirectional"))
      (node (ref "R45") (pin "2") (pinfunction "2_2") (pintype "passive"))
    )
    (net (code "95") (name "Net-(6VREG-FB)") (class "Default")
      (node (ref "6VREG") (pin "6") (pinfunction "FB_6") (pintype "bidirectional"))
      (node (ref "R48") (pin "2") (pinfunction "2_2") (pintype "passive"))
      (node (ref "R49") (pin "1") (pinfunction "1_1") (pintype "passive"))
    )
    (net (code "96") (name "Net-(6VREG-FSW)") (class "Default")
      (node (ref "6VREG") (pin "4") (pinfunction "FSW_4") (pintype "bidirectional"))
      (node (ref "R47") (pin "2") (pinfunction "2_2") (pintype "passive"))
    )
    (net (code "97") (name "Net-(6VREG-LX)") (class "Default")
      (node (ref "6VREG") (pin "1") (pinfunction "LX_1") (pintype "bidirectional"))
      (node (ref "C22") (pin "2") (pinfunction "2_2") (pintype "passive"))
      (node (ref "D9") (pin "C") (pinfunction "C_C") (pintype "passive"))
      (node (ref "L3") (pin "1") (pinfunction "1_1") (pintype "passive"))
    )
    (net (code "98") (name "Net-(6VREG-SS)") (class "Default")
      (node (ref "6VREG") (pin "7") (pinfunction "SS_7") (pintype "bidirectional"))
      (node (ref "C21") (pin "2") (pinfunction "2_2") (pintype "passive"))
    )
    (net (code "99") (name "Net-(ANT1-PadSIG)") (class "Default")
      (node (ref "ANT1") (pin "SIG") (pinfunction "SIG_SIG") (pintype "bidirectional"))
      (node (ref "C48") (pin "1") (pinfunction "1_1") (pintype "passive"))
    )
    (net (code "100") (name "Net-(ANT2-PadSIG)") (class "Default")
      (node (ref "ANT2") (pin "SIG") (pinfunction "SIG_SIG") (pintype "bidirectional"))
      (node (ref "C58") (pin "1") (pinfunction "1_1") (pintype "passive"))
    )
    (net (code "101") (name "Net-(B0-PadC)") (class "Default")
      (node (ref "B0") (pin "C") (pinfunction "C_C") (pintype "passive"))
      (node (ref "R31") (pin "1") (pinfunction "1_1") (pintype "passive"))
    )
    (net (code "102") (name "Net-(B1-PadC)") (class "Default")
      (node (ref "B1") (pin "C") (pinfunction "C_C") (pintype "passive"))
      (node (ref "R29") (pin "1") (pinfunction "1_1") (pintype "passive"))
    )
    (net (code "103") (name "Net-(B2-PadC)") (class "Default")
      (node (ref "B2") (pin "C") (pinfunction "C_C") (pintype "passive"))
      (node (ref "R33") (pin "1") (pinfunction "1_1") (pintype "passive"))
    )
    (net (code "104") (name "Net-(B3-PadC)") (class "Default")
      (node (ref "B3") (pin "C") (pinfunction "C_C") (pintype "passive"))
      (node (ref "R32") (pin "1") (pinfunction "1_1") (pintype "passive"))
    )
    (net (code "105") (name "Net-(BAL-CD)") (class "Default")
      (node (ref "BAL") (pin "4") (pinfunction "CD_4") (pintype "bidirectional"))
      (node (ref "C19") (pin "1") (pinfunction "1_1") (pintype "passive"))
    )
    (net (code "106") (name "Net-(BAL-OUT)") (class "Default")
      (node (ref "BAL") (pin "8") (pinfunction "OUT_8") (pintype "bidirectional"))
      (node (ref "R7") (pin "1") (pinfunction "1_1") (pintype "passive"))
    )
    (net (code "107") (name "Net-(BAL-VC1)") (class "Default")
      (node (ref "BAL") (pin "2") (pinfunction "VC1_2") (pintype "bidirectional"))
      (node (ref "C17") (pin "1") (pinfunction "1_1") (pintype "passive"))
      (node (ref "C18") (pin "2") (pinfunction "2_2") (pintype "passive"))
      (node (ref "R30") (pin "2") (pinfunction "2_2") (pintype "passive"))
    )
    (net (code "108") (name "Net-(BAL-VC1_CB)") (class "Default")
      (node (ref "BAL") (pin "3") (pinfunction "VC1_CB_3") (pintype "bidirectional"))
      (node (ref "R27") (pin "2") (pinfunction "2_2") (pintype "passive"))
    )
    (net (code "109") (name "Net-(BAL-VC2)") (class "Default")
      (node (ref "BAL") (pin "1") (pinfunction "VC2_1") (pintype "bidirectional"))
      (node (ref "C17") (pin "2") (pinfunction "2_2") (pintype "passive"))
      (node (ref "R28") (pin "2") (pinfunction "2_2") (pintype "passive"))
    )
    (net (code "110") (name "Net-(BAL-VDD)") (class "Default")
      (node (ref "BAL") (pin "7") (pinfunction "VDD_7") (pintype "bidirectional"))
      (node (ref "C1") (pin "1") (pinfunction "1_1") (pintype "passive"))
      (node (ref "R34") (pin "2") (pinfunction "2_2") (pintype "passive"))
    )
    (net (code "111") (name "Net-(BT-PadC)") (class "Default")
      (node (ref "BT") (pin "C") (pinfunction "C_C") (pintype "passive"))
      (node (ref "R95") (pin "2") (pinfunction "2_2") (pintype "passive"))
    )
    (net (code "112") (name "Net-(C23-Pad2)") (class "Default")
      (node (ref "C23") (pin "2") (pinfunction "2_2") (pintype "passive"))
      (node (ref "J2") (pin "P$10") (pinfunction "PWR_P$10") (pintype "bidirectional"))
      (node (ref "J2") (pin "P$11") (pinfunction "PWR_P$11") (pintype "bidirectional"))
      (node (ref "J2") (pin "P$12") (pinfunction "PWR_P$12") (pintype "bidirectional"))
      (node (ref "J2") (pin "P$21") (pinfunction "PWR_P$21") (pintype "bidirectional"))
      (node (ref "J2") (pin "P$22") (pinfunction "PWR_P$22") (pintype "bidirectional"))
      (node (ref "J2") (pin "P$7") (pinfunction "PWR_P$7") (pintype "bidirectional"))
      (node (ref "J2") (pin "P$8") (pinfunction "PWR_P$8") (pintype "bidirectional"))
      (node (ref "J2") (pin "P$9") (pinfunction "PWR_P$9") (pintype "bidirectional"))
      (node (ref "L3") (pin "2") (pinfunction "2_2") (pintype "passive"))
      (node (ref "R49") (pin "2") (pinfunction "2_2") (pintype "passive"))
    )
    (net (code "113") (name "Net-(C24-Pad2)") (class "Default")
      (node (ref "C24") (pin "2") (pinfunction "2_2") (pintype "passive"))
      (node (ref "R45") (pin "1") (pinfunction "1_1") (pintype "passive"))
    )
    (net (code "114") (name "Net-(CHG-PadC)") (class "Default")
      (node (ref "CHG") (pin "C") (pinfunction "C_C") (pintype "passive"))
      (node (ref "R3") (pin "2") (pinfunction "2_2") (pintype "passive"))
    )
    (net (code "115") (name "Net-(CHGIC-BST)") (class "Default")
      (node (ref "C14") (pin "1") (pinfunction "1_1") (pintype "passive"))
      (node (ref "CHGIC") (pin "15") (pinfunction "BST_15") (pintype "bidirectional"))
    )
    (net (code "116") (name "Net-(CHGIC-CHGOK)") (class "Default")
      (node (ref "CHGIC") (pin "11") (pinfunction "CHGOK_11") (pintype "bidirectional"))
      (node (ref "R3") (pin "1") (pinfunction "1_1") (pintype "passive"))
    )
    (net (code "117") (name "Net-(CHGIC-CSP)") (class "Default")
      (node (ref "CHGIC") (pin "10") (pinfunction "CSP_10") (pintype "bidirectional"))
      (node (ref "L2") (pin "2") (pinfunction "2_2") (pintype "passive"))
      (node (ref "R4") (pin "2") (pinfunction "2_2") (pintype "passive"))
    )
    (net (code "118") (name "Net-(CHGIC-NTC)") (class "Default")
      (node (ref "CHGIC") (pin "13") (pinfunction "NTC_13") (pintype "bidirectional"))
      (node (ref "R5") (pin "1") (pinfunction "1_1") (pintype "passive"))
      (node (ref "R6") (pin "2") (pinfunction "2_2") (pintype "passive"))
    )
    (net (code "119") (name "Net-(CHGIC-SW)") (class "Default")
      (node (ref "C14") (pin "2") (pinfunction "2_2") (pintype "passive"))
      (node (ref "CHGIC") (pin "1") (pinfunction "SW_1") (pintype "bidirectional"))
      (node (ref "L2") (pin "1") (pinfunction "1_1") (pintype "passive"))
    )
    (net (code "120") (name "Net-(CHGIC-TMR)") (class "Default")
      (node (ref "C10") (pin "2") (pinfunction "2_2") (pintype "passive"))
      (node (ref "CHGIC") (pin "14") (pinfunction "TMR_14") (pintype "bidirectional"))
    )
    (net (code "121") (name "Net-(G-PadC)") (class "Default")
      (node (ref "G") (pin "C") (pinfunction "C_C") (pintype "passive"))
      (node (ref "R22") (pin "1") (pinfunction "1_1") (pintype "passive"))
    )
    (net (code "122") (name "Net-(IMU-REGOUT)") (class "Default")
      (node (ref "C6") (pin "1") (pinfunction "1_1") (pintype "passive"))
      (node (ref "IMU") (pin "10") (pinfunction "REGOUT_10") (pintype "bidirectional"))
    )
    (net (code "123") (name "Net-(J2-1)") (class "Default")
      (node (ref "J2") (pin "P$1") (pinfunction "1_P$1") (pintype "bidirectional"))
      (node (ref "R36") (pin "2") (pinfunction "2_2") (pintype "passive"))
    )
    (net (code "124") (name "Net-(J2-2)") (class "Default")
      (node (ref "J2") (pin "P$2") (pinfunction "2_P$2") (pintype "bidirectional"))
      (node (ref "R37") (pin "2") (pinfunction "2_2") (pintype "passive"))
    )
    (net (code "125") (name "Net-(J2-3)") (class "Default")
      (node (ref "J2") (pin "P$3") (pinfunction "3_P$3") (pintype "bidirectional"))
      (node (ref "R38") (pin "2") (pinfunction "2_2") (pintype "passive"))
    )
    (net (code "126") (name "Net-(J2-4)") (class "Default")
      (node (ref "J2") (pin "P$4") (pinfunction "4_P$4") (pintype "bidirectional"))
      (node (ref "R39") (pin "2") (pinfunction "2_2") (pintype "passive"))
    )
    (net (code "127") (name "Net-(J2-5)") (class "Default")
      (node (ref "J2") (pin "P$5") (pinfunction "5_P$5") (pintype "bidirectional"))
      (node (ref "R40") (pin "2") (pinfunction "2_2") (pintype "passive"))
    )
    (net (code "128") (name "Net-(J2-6)") (class "Default")
      (node (ref "J2") (pin "P$6") (pinfunction "6_P$6") (pintype "bidirectional"))
      (node (ref "R41") (pin "2") (pinfunction "2_2") (pintype "passive"))
    )
    (net (code "129") (name "Net-(J2-7)") (class "Default")
      (node (ref "J2") (pin "P$19") (pinfunction "7_P$19") (pintype "bidirectional"))
      (node (ref "R42") (pin "2") (pinfunction "2_2") (pintype "passive"))
    )
    (net (code "130") (name "Net-(J2-8)") (class "Default")
      (node (ref "J2") (pin "P$20") (pinfunction "8_P$20") (pintype "bidirectional"))
      (node (ref "R43") (pin "2") (pinfunction "2_2") (pintype "passive"))
    )
    (net (code "131") (name "Net-(M1-1)") (class "Default")
      (node (ref "H1") (pin "5") (pinfunction "A02_5") (pintype "bidirectional"))
      (node (ref "H1") (pin "6") (pinfunction "A02_6") (pintype "bidirectional"))
      (node (ref "M1") (pin "P$1") (pinfunction "1_P$1") (pintype "bidirectional"))
    )
    (net (code "132") (name "Net-(M1-2)") (class "Default")
      (node (ref "H1") (pin "1") (pinfunction "A01_1") (pintype "bidirectional"))
      (node (ref "H1") (pin "2") (pinfunction "A01_2") (pintype "bidirectional"))
      (node (ref "M1") (pin "P$2") (pinfunction "2_P$2") (pintype "bidirectional"))
    )
    (net (code "133") (name "Net-(M2-1)") (class "Default")
      (node (ref "H1") (pin "11") (pinfunction "B01_11") (pintype "bidirectional"))
      (node (ref "H1") (pin "12") (pinfunction "B01_12") (pintype "bidirectional"))
      (node (ref "M2") (pin "P$1") (pinfunction "1_P$1") (pintype "bidirectional"))
    )
    (net (code "134") (name "Net-(M2-2)") (class "Default")
      (node (ref "H1") (pin "7") (pinfunction "B02_7") (pintype "bidirectional"))
      (node (ref "H1") (pin "8") (pinfunction "B02_8") (pintype "bidirectional"))
      (node (ref "M2") (pin "P$2") (pinfunction "2_P$2") (pintype "bidirectional"))
    )
    (net (code "135") (name "Net-(M3-1)") (class "Default")
      (node (ref "H2") (pin "1") (pinfunction "A01_1") (pintype "bidirectional"))
      (node (ref "H2") (pin "2") (pinfunction "A01_2") (pintype "bidirectional"))
      (node (ref "M3") (pin "P$1") (pinfunction "1_P$1") (pintype "bidirectional"))
    )
    (net (code "136") (name "Net-(M3-2)") (class "Default")
      (node (ref "H2") (pin "5") (pinfunction "A02_5") (pintype "bidirectional"))
      (node (ref "H2") (pin "6") (pinfunction "A02_6") (pintype "bidirectional"))
      (node (ref "M3") (pin "P$2") (pinfunction "2_P$2") (pintype "bidirectional"))
    )
    (net (code "137") (name "Net-(M4-1)") (class "Default")
      (node (ref "H2") (pin "7") (pinfunction "B02_7") (pintype "bidirectional"))
      (node (ref "H2") (pin "8") (pinfunction "B02_8") (pintype "bidirectional"))
      (node (ref "M4") (pin "P$1") (pinfunction "1_P$1") (pintype "bidirectional"))
    )
    (net (code "138") (name "Net-(M4-2)") (class "Default")
      (node (ref "H2") (pin "11") (pinfunction "B01_11") (pintype "bidirectional"))
      (node (ref "H2") (pin "12") (pinfunction "B01_12") (pintype "bidirectional"))
      (node (ref "M4") (pin "P$2") (pinfunction "2_P$2") (pintype "bidirectional"))
    )
    (net (code "139") (name "Net-(OSC1-EN)") (class "Default")
      (node (ref "OSC1") (pin "1") (pinfunction "EN_1") (pintype "bidirectional"))
      (node (ref "R90") (pin "1") (pinfunction "1_1") (pintype "passive"))
    )
    (net (code "140") (name "Net-(PROT-VDD)") (class "Default")
      (node (ref "C15") (pin "2") (pinfunction "2_2") (pintype "passive"))
      (node (ref "PROT") (pin "5") (pinfunction "VDD_5") (pintype "bidirectional"))
      (node (ref "R44") (pin "2") (pinfunction "2_2") (pintype "passive"))
    )
    (net (code "141") (name "Net-(R-PadC)") (class "Default")
      (node (ref "R") (pin "C") (pinfunction "C_C") (pintype "passive"))
      (node (ref "R21") (pin "1") (pinfunction "1_1") (pintype "passive"))
    )
    (net (code "142") (name "Net-(R76-Pad2)") (class "Default")
      (node (ref "R76") (pin "2") (pinfunction "2_2") (pintype "passive"))
      (node (ref "SIP") (pin "L15") (pinfunction "L15_L15") (pintype "bidirectional"))
    )
    (net (code "143") (name "Net-(R91-Pad1)") (class "Default")
      (node (ref "R91") (pin "1") (pinfunction "1_1") (pintype "passive"))
      (node (ref "T1") (pin "D") (pinfunction "D_D") (pintype "bidirectional"))
    )
    (net (code "144") (name "Net-(R91-Pad2)") (class "Default")
      (node (ref "R91") (pin "2") (pinfunction "2_2") (pintype "passive"))
      (node (ref "WL") (pin "C") (pinfunction "C_C") (pintype "passive"))
    )
    (net (code "145") (name "Net-(R95-Pad1)") (class "Default")
      (node (ref "R95") (pin "1") (pinfunction "1_1") (pintype "passive"))
      (node (ref "T2") (pin "D") (pinfunction "D_D") (pintype "bidirectional"))
    )
    (net (code "146") (name "Net-(SIPA-L1_OUT)") (class "Default")
      (node (ref "SIP") (pin "Y13") (pinfunction "L1_OUT_Y13") (pintype "bidirectional"))
      (node (ref "TP7") (pin "TP") (pinfunction "TP_TP") (pintype "input"))
    )
    (net (code "147") (name "Net-(SIPA-L2_OUT)") (class "Default")
      (node (ref "SIP") (pin "Y16") (pinfunction "L2_OUT_Y16") (pintype "bidirectional"))
      (node (ref "TP9") (pin "TP") (pinfunction "TP_TP") (pintype "input"))
    )
    (net (code "148") (name "Net-(SIPA-L3_OUT)") (class "Default")
      (node (ref "SIP") (pin "Y19") (pinfunction "L3_OUT_Y19") (pintype "bidirectional"))
      (node (ref "TP11") (pin "TP") (pinfunction "TP_TP") (pintype "input"))
    )
    (net (code "149") (name "Net-(SIPA-PMIC_IN_PWR_EN)") (class "Default")
      (node (ref "SIP") (pin "C6") (pinfunction "PMIC_POWER_EN_C6") (pintype "output"))
      (node (ref "SIP") (pin "D19") (pinfunction "PMIC_IN_PWR_EN_D19") (pintype "input"))
      (node (ref "TP5") (pin "TP") (pinfunction "TP_TP") (pintype "input"))
    )
    (net (code "150") (name "Net-(SIPB-JTAG_EMU0)") (class "Default")
      (node (ref "EMU1") (pin "TP") (pinfunction "TP_TP") (pintype "input"))
      (node (ref "SIP") (pin "C14") (pinfunction "JTAG_EMU0_C14") (pintype "bidirectional"))
    )
    (net (code "151") (name "Net-(SIPB-JTAG_EMU1)") (class "Default")
      (node (ref "EMU0") (pin "TP") (pinfunction "TP_TP") (pintype "input"))
      (node (ref "SIP") (pin "B14") (pinfunction "JTAG_EMU1_B14") (pintype "bidirectional"))
    )
    (net (code "152") (name "Net-(SIPB-JTAG_TCK)") (class "Default")
      (node (ref "SIP") (pin "A12") (pinfunction "JTAG_TCK_A12") (pintype "bidirectional"))
      (node (ref "TCK") (pin "TP") (pinfunction "TP_TP") (pintype "input"))
    )
    (net (code "153") (name "Net-(SIPB-JTAG_TDI)") (class "Default")
      (node (ref "SIP") (pin "B11") (pinfunction "JTAG_TDI_B11") (pintype "bidirectional"))
      (node (ref "TDI") (pin "TP") (pinfunction "TP_TP") (pintype "input"))
    )
    (net (code "154") (name "Net-(SIPB-JTAG_TDO)") (class "Default")
      (node (ref "SIP") (pin "A11") (pinfunction "JTAG_TDO_A11") (pintype "bidirectional"))
      (node (ref "TDO") (pin "TP") (pinfunction "TP_TP") (pintype "input"))
    )
    (net (code "155") (name "Net-(SIPB-JTAG_TMS)") (class "Default")
      (node (ref "SIP") (pin "C11") (pinfunction "JTAG_TMS_C11") (pintype "bidirectional"))
      (node (ref "TMS") (pin "TP") (pinfunction "TP_TP") (pintype "input"))
    )
    (net (code "156") (name "Net-(SIPB-JTAG_TRSTN)") (class "Default")
      (node (ref "R59") (pin "2") (pinfunction "2_2") (pintype "passive"))
      (node (ref "SIP") (pin "B10") (pinfunction "JTAG_TRSTN_B10") (pintype "bidirectional"))
      (node (ref "TRSTN") (pin "TP") (pinfunction "TP_TP") (pintype "input"))
    )
    (net (code "157") (name "Net-(SIPB-MMC0_CD_C15)") (class "Default")
      (node (ref "R65") (pin "1") (pinfunction "1_1") (pintype "passive"))
      (node (ref "SIP") (pin "C15") (pinfunction "MMC0_CD_C15_C15") (pintype "bidirectional"))
      (node (ref "X2") (pin "CD") (pinfunction "CD#_CD") (pintype "bidirectional"))
    )
    (net (code "158") (name "Net-(SIPB-MMC0_CLK_G17)") (class "Default")
      (node (ref "R57") (pin "1") (pinfunction "1_1") (pintype "passive"))
      (node (ref "SIP") (pin "G17") (pinfunction "MMC0_CLK_G17_G17") (pintype "bidirectional"))
      (node (ref "X2") (pin "5") (pinfunction "CLK_5") (pintype "bidirectional"))
    )
    (net (code "159") (name "Net-(SIPB-MMC0_CMD_G18)") (class "Default")
      (node (ref "R56") (pin "1") (pinfunction "1_1") (pintype "passive"))
      (node (ref "SIP") (pin "G18") (pinfunction "MMC0_CMD_G18_G18") (pintype "bidirectional"))
      (node (ref "X2") (pin "3") (pinfunction "CMD/DI_3") (pintype "bidirectional"))
    )
    (net (code "160") (name "Net-(SIPB-MMC0_DAT0_G16)") (class "Default")
      (node (ref "R55") (pin "1") (pinfunction "1_1") (pintype "passive"))
      (node (ref "SIP") (pin "G16") (pinfunction "MMC0_DAT0_G16_G16") (pintype "bidirectional"))
      (node (ref "X2") (pin "7") (pinfunction "DAT0/DO_7") (pintype "bidirectional"))
    )
    (net (code "161") (name "Net-(SIPB-MMC0_DAT1_G15)") (class "Default")
      (node (ref "R54") (pin "1") (pinfunction "1_1") (pintype "passive"))
      (node (ref "SIP") (pin "G15") (pinfunction "MMC0_DAT1_G15_G15") (pintype "bidirectional"))
      (node (ref "X2") (pin "8") (pinfunction "DAT1_8") (pintype "bidirectional"))
    )
    (net (code "162") (name "Net-(SIPB-MMC0_DAT2_F18)") (class "Default")
      (node (ref "R35") (pin "1") (pinfunction "1_1") (pintype "passive"))
      (node (ref "SIP") (pin "F18") (pinfunction "MMC0_DAT2_F18_F18") (pintype "bidirectional"))
      (node (ref "X2") (pin "1") (pinfunction "DAT2_1") (pintype "bidirectional"))
    )
    (net (code "163") (name "Net-(SIPB-MMC0_DAT3_F17)") (class "Default")
      (node (ref "R26") (pin "1") (pinfunction "1_1") (pintype "passive"))
      (node (ref "SIP") (pin "F17") (pinfunction "MMC0_DAT3_F17_F17") (pintype "bidirectional"))
      (node (ref "X2") (pin "2") (pinfunction "DAT3/CS_2") (pintype "bidirectional"))
    )
    (net (code "164") (name "Net-(SIPB-MMC1_CLK_U9)") (class "Default")
      (node (ref "R15") (pin "1") (pinfunction "1_1") (pintype "passive"))
      (node (ref "SIP") (pin "U9") (pinfunction "MMC1_CLK_U9_U9") (pintype "bidirectional"))
    )
    (net (code "165") (name "Net-(SIPB-OSC0_GND)") (class "Default")
      (node (ref "C29") (pin "2") (pinfunction "2_2") (pintype "passive"))
      (node (ref "C30") (pin "2") (pinfunction "2_2") (pintype "passive"))
      (node (ref "SIP") (pin "L20") (pinfunction "OSC0_GND_L20") (pintype "bidirectional"))
    )
    (net (code "166") (name "Net-(SIPB-OSC0_IN)") (class "Default")
      (node (ref "C30") (pin "1") (pinfunction "1_1") (pintype "passive"))
      (node (ref "R20") (pin "2") (pinfunction "2_2") (pintype "passive"))
      (node (ref "SIP") (pin "M20") (pinfunction "OSC0_IN_M20") (pintype "bidirectional"))
      (node (ref "Y1") (pin "2") (pinfunction "P$2_2") (pintype "passive"))
    )
    (net (code "167") (name "Net-(SIPB-OSC0_OUT)") (class "Default")
      (node (ref "C29") (pin "1") (pinfunction "1_1") (pintype "passive"))
      (node (ref "R20") (pin "1") (pinfunction "1_1") (pintype "passive"))
      (node (ref "SIP") (pin "K20") (pinfunction "OSC0_OUT_K20") (pintype "bidirectional"))
      (node (ref "Y1") (pin "1") (pinfunction "P$1_1") (pintype "passive"))
    )
    (net (code "168") (name "Net-(SIPB-OSC1_GND)") (class "Default")
      (node (ref "C31") (pin "2") (pinfunction "2_2") (pintype "passive"))
      (node (ref "C32") (pin "1") (pinfunction "1_1") (pintype "passive"))
      (node (ref "SIP") (pin "G20") (pinfunction "OSC1_GND_G20") (pintype "bidirectional"))
    )
    (net (code "169") (name "Net-(SIPB-OSC1_IN)") (class "Default")
      (node (ref "C31") (pin "1") (pinfunction "1_1") (pintype "passive"))
      (node (ref "R18") (pin "2") (pinfunction "2_2") (pintype "passive"))
      (node (ref "SIP") (pin "H20") (pinfunction "OSC1_IN_H20") (pintype "bidirectional"))
      (node (ref "Y2") (pin "P$2") (pinfunction "P$2_P$2") (pintype "passive"))
    )
    (net (code "170") (name "Net-(SIPB-OSC1_OUT)") (class "Default")
      (node (ref "C32") (pin "2") (pinfunction "2_2") (pintype "passive"))
      (node (ref "R18") (pin "1") (pinfunction "1_1") (pintype "passive"))
      (node (ref "SIP") (pin "F20") (pinfunction "OSC1_OUT_F20") (pintype "bidirectional"))
      (node (ref "Y2") (pin "P$1") (pinfunction "P$1_P$1") (pintype "passive"))
    )
    (net (code "171") (name "Net-(SIPC-ADC_VREFP)") (class "Default")
      (node (ref "C42") (pin "1") (pinfunction "1_1") (pintype "passive"))
      (node (ref "C43") (pin "1") (pinfunction "1_1") (pintype "passive"))
      (node (ref "R111") (pin "2") (pinfunction "2_2") (pintype "passive"))
      (node (ref "SIP") (pin "B9") (pinfunction "ADC_VREFP_B9") (pintype "bidirectional"))
    )
    (net (code "172") (name "Net-(SIPC-AIN7)") (class "Default")
      (node (ref "R109") (pin "2") (pinfunction "2_2") (pintype "passive"))
      (node (ref "R110") (pin "1") (pinfunction "1_1") (pintype "passive"))
      (node (ref "SIP") (pin "C9") (pinfunction "AIN7_C9") (pintype "bidirectional"))
    )
    (net (code "173") (name "Net-(SIPC-LCD_DATA11_U4)") (class "Default")
      (node (ref "R135") (pin "2") (pinfunction "2_2") (pintype "passive"))
      (node (ref "SIP") (pin "U4") (pinfunction "LCD_DATA11_U4_U4") (pintype "bidirectional"))
    )
    (net (code "174") (name "Net-(SIPC-USB0_VBUS)") (class "Default")
      (node (ref "R149") (pin "1") (pinfunction "1_1") (pintype "passive"))
      (node (ref "SIP") (pin "P15") (pinfunction "USB0_VBUS_P15") (pintype "bidirectional"))
    )
    (net (code "175") (name "Net-(SIPC-USB1_ID)") (class "Default")
      (node (ref "R150") (pin "1") (pinfunction "1_1") (pintype "passive"))
      (node (ref "SIP") (pin "P17") (pinfunction "USB1_ID_P17") (pintype "bidirectional"))
    )
    (net (code "176") (name "Net-(SIPC-USB1_VBUS)") (class "Default")
      (node (ref "R156") (pin "1") (pinfunction "1_1") (pintype "passive"))
      (node (ref "SIP") (pin "T18") (pinfunction "USB1_VBUS_T18") (pintype "bidirectional"))
    )
    (net (code "177") (name "Net-(SIPE-RTC_KALDO_ENN)") (class "Default")
      (node (ref "R158") (pin "1") (pinfunction "1_1") (pintype "passive"))
      (node (ref "SIP") (pin "B4") (pinfunction "RTC_KALDO_ENN_B4") (pintype "bidirectional"))
    )
    (net (code "178") (name "Net-(SIPE-VDDS_DDR1)") (class "Default")
      (node (ref "SIP") (pin "E5") (pinfunction "VDDS_DDR1_E5") (pintype "bidirectional"))
      (node (ref "TP8") (pin "TP") (pinfunction "TP_TP") (pintype "input"))
    )
    (net (code "179") (name "Net-(SIPE-VDD_3V3A12)") (class "Default")
      (node (ref "SIP") (pin "N15") (pinfunction "VDD_3V3A12_N15") (pintype "bidirectional"))
      (node (ref "TP2") (pin "TP") (pinfunction "TP_TP") (pintype "input"))
    )
    (net (code "180") (name "Net-(SIPE-VDD_CORE20)") (class "Default")
      (node (ref "SIP") (pin "N13") (pinfunction "VDD_CORE20_N13") (pintype "bidirectional"))
      (node (ref "TP6") (pin "TP") (pinfunction "TP_TP") (pintype "input"))
    )
    (net (code "181") (name "Net-(SIPE-VDD_MPU6)") (class "Default")
      (node (ref "SIP") (pin "J13") (pinfunction "VDD_MPU6_J13") (pintype "bidirectional"))
      (node (ref "TP3") (pin "TP") (pinfunction "TP_TP") (pintype "input"))
    )
    (net (code "182") (name "Net-(SIPE-VDD_PLL2)") (class "Default")
      (node (ref "SIP") (pin "H15") (pinfunction "VDD_PLL2_H15") (pintype "bidirectional"))
      (node (ref "TP4") (pin "TP") (pinfunction "TP_TP") (pintype "input"))
    )
    (net (code "183") (name "Net-(TP10-TP)") (class "Default")
      (node (ref "R58") (pin "1") (pinfunction "1_1") (pintype "passive"))
      (node (ref "TP10") (pin "P$1") (pinfunction "TP_P$1") (pintype "bidirectional"))
      (node (ref "U5") (pin "5") (pinfunction "WP_5") (pintype "input"))
    )
    (net (code "184") (name "Net-(U7-BT_AUD_CLK)") (class "Default")
      (node (ref "R124") (pin "2") (pinfunction "2_2") (pintype "passive"))
      (node (ref "U7") (pin "60") (pinfunction "BT_AUD_CLK_60") (pintype "bidirectional"))
    )
    (net (code "185") (name "Net-(U7-BT_AUD_FSYNC)") (class "Default")
      (node (ref "R123") (pin "2") (pinfunction "2_2") (pintype "passive"))
      (node (ref "U7") (pin "58") (pinfunction "BT_AUD_FSYNC_58") (pintype "bidirectional"))
    )
    (net (code "186") (name "Net-(U7-BT_AUD_IN)") (class "Default")
      (node (ref "R97") (pin "2") (pinfunction "2_2") (pintype "passive"))
      (node (ref "U7") (pin "56") (pinfunction "BT_AUD_IN_56") (pintype "bidirectional"))
    )
    (net (code "187") (name "Net-(U7-BT_AUD_OUT)") (class "Default")
      (node (ref "R100") (pin "2") (pinfunction "2_2") (pintype "passive"))
      (node (ref "U7") (pin "57") (pinfunction "BT_AUD_OUT_57") (pintype "bidirectional"))
    )
    (net (code "188") (name "Net-(U7-BT_HCI_CTS)") (class "Default")
      (node (ref "R86") (pin "2") (pinfunction "2_2") (pintype "passive"))
      (node (ref "U7") (pin "51") (pinfunction "BT_HCI_CTS_51") (pintype "bidirectional"))
    )
    (net (code "189") (name "Net-(U7-BT_HCI_RTS)") (class "Default")
      (node (ref "R85") (pin "2") (pinfunction "2_2") (pintype "passive"))
      (node (ref "U7") (pin "50") (pinfunction "BT_HCI_RTS_50") (pintype "bidirectional"))
    )
    (net (code "190") (name "Net-(U7-BT_HCI_RX)") (class "Default")
      (node (ref "R96") (pin "2") (pinfunction "2_2") (pintype "passive"))
      (node (ref "U7") (pin "53") (pinfunction "BT_HCI_RX_53") (pintype "bidirectional"))
    )
    (net (code "191") (name "Net-(U7-BT_HCI_TX)") (class "Default")
      (node (ref "R92") (pin "2") (pinfunction "2_2") (pintype "passive"))
      (node (ref "U7") (pin "52") (pinfunction "BT_HCI_TX_52") (pintype "bidirectional"))
    )
    (net (code "192") (name "Net-(U7-RF_ANT1)") (class "Default")
      (node (ref "C48") (pin "2") (pinfunction "2_2") (pintype "passive"))
      (node (ref "U7") (pin "32") (pinfunction "RF_ANT1_32") (pintype "bidirectional"))
    )
    (net (code "193") (name "Net-(U7-RF_ANT2)") (class "Default")
      (node (ref "C58") (pin "2") (pinfunction "2_2") (pintype "passive"))
      (node (ref "U7") (pin "18") (pinfunction "RF_ANT2_18") (pintype "bidirectional"))
    )
    (net (code "194") (name "Net-(U7-WLAN_IRQ)") (class "Default")
      (node (ref "R84") (pin "2") (pinfunction "2_2") (pintype "passive"))
      (node (ref "R9") (pin "2") (pinfunction "2_2") (pintype "passive"))
      (node (ref "U7") (pin "14") (pinfunction "WLAN_IRQ_14") (pintype "bidirectional"))
    )
    (net (code "195") (name "Net-(U7-WL_SDIO_CLK)") (class "Default")
      (node (ref "R78") (pin "2") (pinfunction "2_2") (pintype "passive"))
      (node (ref "U7") (pin "8") (pinfunction "WL_SDIO_CLK_8") (pintype "bidirectional"))
    )
    (net (code "196") (name "Net-(U7-WL_SDIO_CMD)") (class "Default")
      (node (ref "R79") (pin "2") (pinfunction "2_2") (pintype "passive"))
      (node (ref "U7") (pin "6") (pinfunction "WL_SDIO_CMD_6") (pintype "bidirectional"))
    )
    (net (code "197") (name "Net-(U7-WL_SDIO_D0)") (class "Default")
      (node (ref "R80") (pin "2") (pinfunction "2_2") (pintype "passive"))
      (node (ref "U7") (pin "10") (pinfunction "WL_SDIO_D0_10") (pintype "bidirectional"))
    )
    (net (code "198") (name "Net-(U7-WL_SDIO_D1)") (class "Default")
      (node (ref "R81") (pin "2") (pinfunction "2_2") (pintype "passive"))
      (node (ref "U7") (pin "11") (pinfunction "WL_SDIO_D1_11") (pintype "bidirectional"))
    )
    (net (code "199") (name "Net-(U7-WL_SDIO_D2)") (class "Default")
      (node (ref "R82") (pin "2") (pinfunction "2_2") (pintype "passive"))
      (node (ref "U7") (pin "12") (pinfunction "WL_SDIO_D2_12") (pintype "bidirectional"))
    )
    (net (code "200") (name "Net-(U7-WL_SDIO_D3)") (class "Default")
      (node (ref "R83") (pin "2") (pinfunction "2_2") (pintype "passive"))
      (node (ref "U7") (pin "13") (pinfunction "WL_SDIO_D3_13") (pintype "bidirectional"))
    )
    (net (code "201") (name "Net-(U10-OE)") (class "Default")
      (node (ref "R106") (pin "2") (pinfunction "2_2") (pintype "passive"))
      (node (ref "R93") (pin "2") (pinfunction "2_2") (pintype "passive"))
      (node (ref "U10") (pin "10") (pinfunction "OE_10") (pintype "bidirectional"))
      (node (ref "U2") (pin "1") (pinfunction "OE_1") (pintype "input"))
      (node (ref "U9") (pin "10") (pinfunction "OE_10") (pintype "bidirectional"))
    )
    (net (code "202") (name "Net-(U13-VDDI)") (class "Default")
      (node (ref "C36") (pin "1") (pinfunction "1_1") (pintype "passive"))
      (node (ref "U13") (pin "C2") (pinfunction "VDDI_C2") (pintype "bidirectional"))
    )
    (net (code "203") (name "Net-(X3-GND)") (class "Default")
      (node (ref "L4") (pin "2") (pinfunction "2_2") (pintype "passive"))
      (node (ref "X3") (pin "4") (pinfunction "GND_4") (pintype "bidirectional"))
    )
    (net (code "204") (name "Net-(X3-VBUS)") (class "Default")
      (node (ref "L5") (pin "2") (pinfunction "2_2") (pintype "passive"))
      (node (ref "X3") (pin "1") (pinfunction "VBUS_1") (pintype "bidirectional"))
    )
    (net (code "205") (name "PAUSE_BTN") (class "Default")
      (node (ref "PAU") (pin "2") (pinfunction "2_2") (pintype "passive"))
      (node (ref "SIP") (pin "T6") (pinfunction "TIMER5_T6_T6") (pintype "bidirectional"))
    )
    (net (code "206") (name "PMIC_INT") (class "Default")
      (node (ref "SIP") (pin "B18") (pinfunction "EXTINTN_B18") (pintype "bidirectional"))
      (node (ref "SIP") (pin "B19") (pinfunction "PMIC_OUT_NINT_B19") (pintype "output"))
    )
    (net (code "207") (name "PMIC_NWAKEUP") (class "Default")
      (node (ref "SIP") (pin "A19") (pinfunction "PMIC_OUT_NWAKEUP_A19") (pintype "output"))
      (node (ref "SIP") (pin "C5") (pinfunction "EXT_WAKEUP_C5") (pintype "bidirectional"))
    )
    (net (code "208") (name "PMIC_PGOOD") (class "Default")
      (node (ref "SIP") (pin "A20") (pinfunction "PMIC_OUT_PGOOD_A20") (pintype "output"))
      (node (ref "SIP") (pin "B15") (pinfunction "PWRONRSTN_B15") (pintype "bidirectional"))
      (node (ref "U6") (pin "2") (pinfunction "A_2") (pintype "input"))
    )
    (net (code "209") (name "POWER_BTN") (class "Default")
      (node (ref "POW") (pin "2") (pinfunction "2_2") (pintype "passive"))
      (node (ref "SIP") (pin "D20") (pinfunction "PMIC_IN_PB_IN_D20") (pintype "bidirectional"))
    )
    (net (code "210") (name "PRU_E_A") (class "Default")
      (node (ref "E4") (pin "3") (pinfunction "3_3") (pintype "bidirectional"))
      (node (ref "SIP") (pin "V13") (pinfunction "GPIO1_14_V13_V13") (pintype "bidirectional"))
    )
    (net (code "211") (name "PRU_E_B") (class "Default")
      (node (ref "E4") (pin "4") (pinfunction "4_4") (pintype "bidirectional"))
      (node (ref "SIP") (pin "U13") (pinfunction "GPIO1_15_U13_U13") (pintype "bidirectional"))
    )
    (net (code "212") (name "PWM_1A") (class "Default")
      (node (ref "H1") (pin "23") (pinfunction "PWMA_23") (pintype "bidirectional"))
      (node (ref "SIP") (pin "U14") (pinfunction "EHRPWM1A_U14_U14") (pintype "bidirectional"))
    )
    (net (code "213") (name "PWM_1B") (class "Default")
      (node (ref "H1") (pin "15") (pinfunction "PWMB_15") (pintype "bidirectional"))
      (node (ref "SIP") (pin "T14") (pinfunction "EHRPWM1B_T14_T14") (pintype "bidirectional"))
    )
    (net (code "214") (name "PWM_2A") (class "Default")
      (node (ref "H2") (pin "23") (pinfunction "PWMA_23") (pintype "bidirectional"))
      (node (ref "SIP") (pin "U10") (pinfunction "EHRPWM2A_U10_U10") (pintype "bidirectional"))
    )
    (net (code "215") (name "PWM_2B") (class "Default")
      (node (ref "H2") (pin "15") (pinfunction "PWMB_15") (pintype "bidirectional"))
      (node (ref "SIP") (pin "T10") (pinfunction "EHRPWM2B_T10_T10") (pintype "bidirectional"))
    )
    (net (code "216") (name "PWR_LED") (class "Default")
      (node (ref "ON") (pin "C") (pinfunction "C_C") (pintype "passive"))
      (node (ref "R24") (pin "1") (pinfunction "1_1") (pintype "passive"))
    )
    (net (code "217") (name "RESET") (class "Default")
      (node (ref "C33") (pin "1") (pinfunction "1_1") (pintype "passive"))
      (node (ref "R60") (pin "1") (pinfunction "1_1") (pintype "passive"))
      (node (ref "RST") (pin "2") (pinfunction "2_2") (pintype "passive"))
      (node (ref "SIP") (pin "A10") (pinfunction "WARMRSTN_A10") (pintype "bidirectional"))
      (node (ref "U6") (pin "4") (pinfunction "Y_4") (pintype "output"))
    )
    (net (code "218") (name "SD_BOOT") (class "Default")
      (node (ref "R77") (pin "2") (pinfunction "2_2") (pintype "passive"))
      (node (ref "SD") (pin "2") (pinfunction "2_2") (pintype "passive"))
    )
    (net (code "219") (name "SERVO_EN") (class "Default")
      (node (ref "6VREG") (pin "8") (pinfunction "EN_8") (pintype "bidirectional"))
      (node (ref "R46") (pin "2") (pinfunction "2_2") (pintype "passive"))
      (node (ref "SIP") (pin "U3") (pinfunction "LCD_DATA10_U3_U3") (pintype "bidirectional"))
    )
    (net (code "220") (name "SPI1_MISO") (class "Default")
      (node (ref "S1.1") (pin "4") (pinfunction "4_4") (pintype "bidirectional"))
      (node (ref "S1.2") (pin "4") (pinfunction "4_4") (pintype "bidirectional"))
      (node (ref "SIP") (pin "B13") (pinfunction "SPI1_D0_B13_B13") (pintype "bidirectional"))
    )
    (net (code "221") (name "SPI1_MOSI") (class "Default")
      (node (ref "S1.1") (pin "3") (pinfunction "3_3") (pintype "bidirectional"))
      (node (ref "S1.2") (pin "3") (pinfunction "3_3") (pintype "bidirectional"))
      (node (ref "SIP") (pin "D12") (pinfunction "SPI1_D1_D12_D12") (pintype "bidirectional"))
    )
    (net (code "222") (name "SPI1_SCK") (class "Default")
      (node (ref "S1.1") (pin "5") (pinfunction "5_5") (pintype "bidirectional"))
      (node (ref "S1.2") (pin "5") (pinfunction "5_5") (pintype "bidirectional"))
      (node (ref "SIP") (pin "A13") (pinfunction "SPI1_CLK_A13_A13") (pintype "bidirectional"))
    )
    (net (code "223") (name "SPI1_SS1") (class "Default")
      (node (ref "S1.1") (pin "6") (pinfunction "6_6") (pintype "bidirectional"))
      (node (ref "SIP") (pin "C12") (pinfunction "SPI1_CS0_C12_C12") (pintype "bidirectional"))
    )
    (net (code "224") (name "SPI1_SS2") (class "Default")
      (node (ref "S1.2") (pin "6") (pinfunction "6_6") (pintype "bidirectional"))
      (node (ref "SIP") (pin "A15") (pinfunction "GPIO0_19_A15_A15") (pintype "bidirectional"))
    )
    (net (code "225") (name "SVO1") (class "Default")
      (node (ref "R36") (pin "1") (pinfunction "1_1") (pintype "passive"))
      (node (ref "R50") (pin "1") (pinfunction "1_1") (pintype "passive"))
      (node (ref "SIP") (pin "U5") (pinfunction "LCD_VSYNC_U5_U5") (pintype "bidirectional"))
    )
    (net (code "226") (name "SVO2") (class "Default")
      (node (ref "R37") (pin "1") (pinfunction "1_1") (pintype "passive"))
      (node (ref "R51") (pin "1") (pinfunction "1_1") (pintype "passive"))
      (node (ref "SIP") (pin "V5") (pinfunction "LCD_PCLK_V5_V5") (pintype "bidirectional"))
    )
    (net (code "227") (name "SVO3") (class "Default")
      (node (ref "R38") (pin "1") (pinfunction "1_1") (pintype "passive"))
      (node (ref "R52") (pin "1") (pinfunction "1_1") (pintype "passive"))
      (node (ref "SIP") (pin "R5") (pinfunction "LCD_HSYNC_R5_R5") (pintype "bidirectional"))
    )
    (net (code "228") (name "SVO4") (class "Default")
      (node (ref "R39") (pin "1") (pinfunction "1_1") (pintype "passive"))
      (node (ref "R53") (pin "1") (pinfunction "1_1") (pintype "passive"))
      (node (ref "SIP") (pin "R6") (pinfunction "LCD_DE_R6_R6") (pintype "bidirectional"))
    )
    (net (code "229") (name "SVO5") (class "Default")
      (node (ref "R125") (pin "2") (pinfunction "2_2") (pintype "passive"))
      (node (ref "R40") (pin "1") (pinfunction "1_1") (pintype "passive"))
      (node (ref "SIP") (pin "T3") (pinfunction "LCD_DATA6_T3_T3") (pintype "bidirectional"))
    )
    (net (code "230") (name "SVO6") (class "Default")
      (node (ref "R127") (pin "2") (pinfunction "2_2") (pintype "passive"))
      (node (ref "R41") (pin "1") (pinfunction "1_1") (pintype "passive"))
      (node (ref "SIP") (pin "T4") (pinfunction "LCD_DATA7_T4_T4") (pintype "bidirectional"))
    )
    (net (code "231") (name "SVO7") (class "Default")
      (node (ref "R120") (pin "1") (pinfunction "1_1") (pintype "passive"))
      (node (ref "R42") (pin "1") (pinfunction "1_1") (pintype "passive"))
      (node (ref "SIP") (pin "T1") (pinfunction "LCD_DATA4_T1_T1") (pintype "bidirectional"))
    )
    (net (code "232") (name "SVO8") (class "Default")
      (node (ref "R122") (pin "1") (pinfunction "1_1") (pintype "passive"))
      (node (ref "R43") (pin "1") (pinfunction "1_1") (pintype "passive"))
      (node (ref "SIP") (pin "T2") (pinfunction "LCD_DATA5_T2_T2") (pintype "bidirectional"))
    )
    (net (code "233") (name "SYS_5V") (class "Default")
      (node (ref "R121") (pin "2") (pinfunction "2_2") (pintype "passive"))
      (node (ref "SIP") (pin "W4") (pinfunction "VOUT_SYS_5V_0_W4") (pintype "power_in"))
      (node (ref "SIP") (pin "Y4") (pinfunction "VOUT_SYS_5V_1_Y4") (pintype "power_in"))
      (node (ref "TP1") (pin "TP") (pinfunction "TP_TP") (pintype "input"))
    )
    (net (code "234") (name "UART0_RX") (class "Default")
      (node (ref "SIP") (pin "E15") (pinfunction "UART0_RXD_E15_E15") (pintype "bidirectional"))
      (node (ref "UT0") (pin "3") (pinfunction "3_3") (pintype "bidirectional"))
    )
    (net (code "235") (name "UART0_TX") (class "Default")
      (node (ref "SIP") (pin "E16") (pinfunction "UART0_TXD_E16_E16") (pintype "bidirectional"))
      (node (ref "UT0") (pin "4") (pinfunction "4_4") (pintype "bidirectional"))
    )
    (net (code "236") (name "UART1_RX") (class "Default")
      (node (ref "SIP") (pin "D16") (pinfunction "UART1_RXD_D16_D16") (pintype "bidirectional"))
      (node (ref "UT1") (pin "3") (pinfunction "3_3") (pintype "bidirectional"))
    )
    (net (code "237") (name "UART1_TX") (class "Default")
      (node (ref "SIP") (pin "D15") (pinfunction "UART1_TXD_D15_D15") (pintype "bidirectional"))
      (node (ref "UT1") (pin "4") (pinfunction "4_4") (pintype "bidirectional"))
    )
    (net (code "238") (name "UART2_RX") (class "Default")
      (node (ref "GPS") (pin "3") (pinfunction "3_3") (pintype "bidirectional"))
      (node (ref "SIP") (pin "A17") (pinfunction "UART2_RXD_A17_A17") (pintype "bidirectional"))
    )
    (net (code "239") (name "UART2_TX") (class "Default")
      (node (ref "GPS") (pin "4") (pinfunction "4_4") (pintype "bidirectional"))
      (node (ref "SIP") (pin "B17") (pinfunction "UART2_TXD_B17_B17") (pintype "bidirectional"))
    )
    (net (code "240") (name "UART3_CTSN") (class "Default")
      (node (ref "R89") (pin "1") (pinfunction "1_1") (pintype "passive"))
      (node (ref "SIP") (pin "M17") (pinfunction "M17_M17") (pintype "bidirectional"))
      (node (ref "U10") (pin "12") (pinfunction "B8_12") (pintype "bidirectional"))
    )
    (net (code "241") (name "UART3_RTSN") (class "Default")
      (node (ref "R108") (pin "1") (pinfunction "1_1") (pintype "passive"))
      (node (ref "SIP") (pin "M18") (pinfunction "M18_M18") (pintype "bidirectional"))
      (node (ref "U10") (pin "13") (pinfunction "B7_13") (pintype "bidirectional"))
    )
    (net (code "242") (name "UART3_RX") (class "Default")
      (node (ref "SIP") (pin "L17") (pinfunction "L17_L17") (pintype "bidirectional"))
      (node (ref "U10") (pin "14") (pinfunction "B6_14") (pintype "bidirectional"))
    )
    (net (code "243") (name "UART3_TX") (class "Default")
      (node (ref "SIP") (pin "L16") (pinfunction "L16_L16") (pintype "bidirectional"))
      (node (ref "U10") (pin "15") (pinfunction "B5_15") (pintype "bidirectional"))
    )
    (net (code "244") (name "UART4_RX") (class "Default")
      (node (ref "DSM2") (pin "P$3") (pinfunction "3_P$3") (pintype "bidirectional"))
      (node (ref "SIP") (pin "T17") (pinfunction "UART4_RXD_T17_T17") (pintype "bidirectional"))
    )
    (net (code "245") (name "UART5_RX") (class "Default")
      (node (ref "R140") (pin "1") (pinfunction "1_1") (pintype "passive"))
      (node (ref "SIP") (pin "V4") (pinfunction "LCD_DATA14_V4_V4") (pintype "bidirectional"))
      (node (ref "UT5") (pin "1") (pinfunction "1_1") (pintype "bidirectional"))
    )
    (net (code "246") (name "UART5_TX") (class "Default")
      (node (ref "R129") (pin "2") (pinfunction "2_2") (pintype "passive"))
      (node (ref "SIP") (pin "U1") (pinfunction "LCD_DATA8_U1_U1") (pintype "bidirectional"))
      (node (ref "UT5") (pin "2") (pinfunction "2_2") (pintype "bidirectional"))
    )
    (net (code "247") (name "USB0_D_N") (class "Default")
      (node (ref "SIP") (pin "N18") (pinfunction "USB0_DM_N18") (pintype "bidirectional"))
      (node (ref "U3") (pin "2") (pinfunction "D-_2") (pintype "bidirectional"))
      (node (ref "X4") (pin "D-") (pinfunction "D-_D-") (pintype "input"))
    )
    (net (code "248") (name "USB0_D_P") (class "Default")
      (node (ref "SIP") (pin "N17") (pinfunction "USB0_DP_N17") (pintype "bidirectional"))
      (node (ref "U3") (pin "1") (pinfunction "D+_1") (pintype "bidirectional"))
      (node (ref "X4") (pin "D+") (pinfunction "D+_D+") (pintype "input"))
    )
    (net (code "249") (name "USB0_ID") (class "Default")
      (node (ref "SIP") (pin "P16") (pinfunction "USB0_ID_P16") (pintype "bidirectional"))
      (node (ref "U3") (pin "3") (pinfunction "ID_3") (pintype "bidirectional"))
      (node (ref "X4") (pin "ID") (pinfunction "ID_ID") (pintype "input"))
    )
    (net (code "250") (name "USB0_VBUS") (class "Default")
      (node (ref "C54") (pin "1") (pinfunction "1_1") (pintype "passive"))
      (node (ref "R112") (pin "2") (pinfunction "2_2") (pintype "passive"))
      (node (ref "R149") (pin "2") (pinfunction "2_2") (pintype "passive"))
      (node (ref "U3") (pin "6") (pinfunction "VBUS_6") (pintype "bidirectional"))
      (node (ref "X4") (pin "VBUS") (pinfunction "VBUS_VBUS") (pintype "input"))
    )
    (net (code "251") (name "USB1_D_N") (class "Default")
      (node (ref "SIP") (pin "R18") (pinfunction "USB1_DM_R18") (pintype "bidirectional"))
      (node (ref "U4") (pin "2") (pinfunction "D-_2") (pintype "bidirectional"))
      (node (ref "X3") (pin "2") (pinfunction "D-_2") (pintype "bidirectional"))
    )
    (net (code "252") (name "USB1_D_P") (class "Default")
      (node (ref "SIP") (pin "R17") (pinfunction "USB1_DP_R17") (pintype "bidirectional"))
      (node (ref "U4") (pin "1") (pinfunction "D+_1") (pintype "bidirectional"))
      (node (ref "X3") (pin "3") (pinfunction "D+_3") (pintype "bidirectional"))
    )
    (net (code "253") (name "USB1_VBUS") (class "Default")
      (node (ref "C45") (pin "1") (pinfunction "1_1") (pintype "passive"))
      (node (ref "C46") (pin "1") (pinfunction "1_1") (pintype "passive"))
      (node (ref "C55") (pin "1") (pinfunction "1_1") (pintype "passive"))
      (node (ref "L5") (pin "1") (pinfunction "1_1") (pintype "passive"))
      (node (ref "R119") (pin "1") (pinfunction "1_1") (pintype "passive"))
      (node (ref "R121") (pin "1") (pinfunction "1_1") (pintype "passive"))
      (node (ref "R156") (pin "2") (pinfunction "2_2") (pintype "passive"))
      (node (ref "U4") (pin "6") (pinfunction "VBUS_6") (pintype "bidirectional"))
    )
    (net (code "254") (name "USB_DC") (class "Default")
      (node (ref "R112") (pin "1") (pinfunction "1_1") (pintype "passive"))
      (node (ref "SIP") (pin "Y8") (pinfunction "VIN_USB_0_Y8") (pintype "power_in"))
      (node (ref "SIP") (pin "Y9") (pinfunction "VIN_USB_1_Y9") (pintype "power_in"))
    )
    (net (code "255") (name "USR_LED0") (class "Default")
      (node (ref "0") (pin "A") (pinfunction "A_A") (pintype "passive"))
      (node (ref "SIP") (pin "V15") (pinfunction "USR0_V15_V15") (pintype "bidirectional"))
    )
    (net (code "256") (name "USR_LED1") (class "Default")
      (node (ref "1") (pin "A") (pinfunction "A_A") (pintype "passive"))
      (node (ref "SIP") (pin "U15") (pinfunction "USR1_U15_U15") (pintype "bidirectional"))
    )
    (net (code "257") (name "USR_LED2") (class "Default")
      (node (ref "2") (pin "A") (pinfunction "A_A") (pintype "passive"))
      (node (ref "SIP") (pin "T15") (pinfunction "USR2_T15_T15") (pintype "bidirectional"))
    )
    (net (code "258") (name "USR_LED3") (class "Default")
      (node (ref "3") (pin "A") (pinfunction "A_A") (pintype "passive"))
      (node (ref "SIP") (pin "V16") (pinfunction "USR3_V16_V16") (pintype "bidirectional"))
    )
    (net (code "259") (name "VCC") (class "Default")
      (node (ref "12V") (pin "IN") (pinfunction "IN_IN") (pintype "bidirectional"))
      (node (ref "C12") (pin "1") (pinfunction "1_1") (pintype "passive"))
      (node (ref "C7") (pin "1") (pinfunction "1_1") (pintype "passive"))
      (node (ref "CHG") (pin "A") (pinfunction "A_A") (pintype "passive"))
      (node (ref "CHGIC") (pin "2") (pinfunction "VIN_2") (pintype "bidirectional"))
      (node (ref "D3") (pin "A") (pinfunction "A_A") (pintype "passive"))
      (node (ref "R1") (pin "1") (pinfunction "1_1") (pintype "passive"))
    )
    (net (code "260") (name "VCC_CHG") (class "Default")
      (node (ref "C4") (pin "2") (pinfunction "2_2") (pintype "passive"))
      (node (ref "CHGIC") (pin "3") (pinfunction "VCC_3") (pintype "bidirectional"))
      (node (ref "R5") (pin "2") (pinfunction "2_2") (pintype "passive"))
    )
    (net (code "261") (name "VDD_1V8") (class "Default")
      (node (ref "C47") (pin "1") (pinfunction "1_1") (pintype "passive"))
      (node (ref "C50") (pin "1") (pinfunction "1_1") (pintype "passive"))
      (node (ref "C52") (pin "1") (pinfunction "1_1") (pintype "passive"))
      (node (ref "C57") (pin "2") (pinfunction "2_2") (pintype "passive"))
      (node (ref "OSC1") (pin "4") (pinfunction "VCC_4") (pintype "bidirectional"))
      (node (ref "R101") (pin "1") (pinfunction "1_1") (pintype "passive"))
      (node (ref "R102") (pin "1") (pinfunction "1_1") (pintype "passive"))
      (node (ref "R103") (pin "1") (pinfunction "1_1") (pintype "passive"))
      (node (ref "R105") (pin "1") (pinfunction "1_1") (pintype "passive"))
      (node (ref "R9") (pin "1") (pinfunction "1_1") (pintype "passive"))
      (node (ref "R90") (pin "2") (pinfunction "2_2") (pintype "passive"))
      (node (ref "R98") (pin "1") (pinfunction "1_1") (pintype "passive"))
      (node (ref "R99") (pin "1") (pinfunction "1_1") (pintype "passive"))
      (node (ref "SIP") (pin "D10") (pinfunction "VDD_1V84_D10") (pintype "bidirectional"))
      (node (ref "SIP") (pin "E9") (pinfunction "VDD_1V83_E9") (pintype "bidirectional"))
      (node (ref "SIP") (pin "N16") (pinfunction "VOUT_LDO3_1P8V_0_N16") (pintype "power_in"))
      (node (ref "SIP") (pin "R16") (pinfunction "VOUT_LDO3_1P8V_1_R16") (pintype "power_in"))
      (node (ref "U10") (pin "2") (pinfunction "VCCA_2") (pintype "bidirectional"))
      (node (ref "U2") (pin "5") (pinfunction "VCC_5") (pintype "power_in"))
      (node (ref "U7") (pin "38") (pinfunction "VIO_38") (pintype "bidirectional"))
      (node (ref "U9") (pin "2") (pinfunction "VCCA_2") (pintype "bidirectional"))
    )
    (net (code "262") (name "VDD_3V3AUX") (class "Default")
      (node (ref "ON") (pin "A") (pinfunction "A_A") (pintype "passive"))
      (node (ref "SIP") (pin "Y11") (pinfunction "VOUT_LDO2_3P3V_Y11") (pintype "power_in"))
    )
    (net (code "263") (name "VDD_ADC") (class "Default")
      (node (ref "ADC") (pin "2") (pinfunction "2_2") (pintype "bidirectional"))
      (node (ref "C44") (pin "1") (pinfunction "1_1") (pintype "passive"))
      (node (ref "R111") (pin "1") (pinfunction "1_1") (pintype "passive"))
      (node (ref "SIP") (pin "A4") (pinfunction "VOUT_ADC_1P8V_0_A4") (pintype "bidirectional"))
      (node (ref "SIP") (pin "A5") (pinfunction "VOUT_ADC_1P8V_1_A5") (pintype "bidirectional"))
      (node (ref "SIP") (pin "D8") (pinfunction "VDDA_ADC_D8") (pintype "bidirectional"))
    )
    (net (code "264") (name "VDD_RTC") (class "Default")
      (node (ref "SIP") (pin "E14") (pinfunction "VDD_RTC3_E14") (pintype "bidirectional"))
      (node (ref "U6") (pin "5") (pinfunction "VCC_5") (pintype "power_in"))
    )
    (net (code "265") (name "VIN_BAT_0") (class "Default")
      (node (ref "SIP") (pin "Y2") (pinfunction "VIN_BAT_0_Y2") (pintype "power_in"))
    )
    (net (code "266") (name "VIN_BAT_1") (class "Default")
      (node (ref "SIP") (pin "Y3") (pinfunction "VIN_BAT_1_Y3") (pintype "power_in"))
    )
    (net (code "267") (name "V_BATT") (class "Default")
      (node (ref "6VREG") (pin "9") (pinfunction "VIN_9") (pintype "bidirectional"))
      (node (ref "C11") (pin "+") (pinfunction "+_+") (pintype "passive"))
      (node (ref "C20") (pin "2") (pinfunction "2_2") (pintype "passive"))
      (node (ref "C25") (pin "1") (pinfunction "1_1") (pintype "passive"))
      (node (ref "C26") (pin "1") (pinfunction "1_1") (pintype "passive"))
      (node (ref "CHGIC") (pin "9") (pinfunction "BATT_9") (pintype "bidirectional"))
      (node (ref "D2") (pin "A") (pinfunction "A_A") (pintype "passive"))
      (node (ref "H1") (pin "13") (pinfunction "VM2_13") (pintype "bidirectional"))
      (node (ref "H1") (pin "14") (pinfunction "VM3_14") (pintype "bidirectional"))
      (node (ref "H1") (pin "24") (pinfunction "VM1_24") (pintype "bidirectional"))
      (node (ref "H2") (pin "13") (pinfunction "VM2_13") (pintype "bidirectional"))
      (node (ref "H2") (pin "14") (pinfunction "VM3_14") (pintype "bidirectional"))
      (node (ref "H2") (pin "24") (pinfunction "VM1_24") (pintype "bidirectional"))
      (node (ref "LIPO") (pin "P$1") (pinfunction "1_P$1") (pintype "passive"))
      (node (ref "R19") (pin "1") (pinfunction "1_1") (pintype "passive"))
      (node (ref "R28") (pin "1") (pinfunction "1_1") (pintype "passive"))
      (node (ref "R34") (pin "1") (pinfunction "1_1") (pintype "passive"))
      (node (ref "R4") (pin "1") (pinfunction "1_1") (pintype "passive"))
    )
    (net (code "268") (name "V_DIV_BAT") (class "Default")
      (node (ref "R19") (pin "2") (pinfunction "2_2") (pintype "passive"))
      (node (ref "R25") (pin "1") (pinfunction "1_1") (pintype "passive"))
      (node (ref "SIP") (pin "A8") (pinfunction "AIN6_A8") (pintype "bidirectional"))
    )
    (net (code "269") (name "V_DIV_DC") (class "Default")
      (node (ref "R1") (pin "2") (pinfunction "2_2") (pintype "passive"))
      (node (ref "R14") (pin "1") (pinfunction "1_1") (pintype "passive"))
      (node (ref "SIP") (pin "B8") (pinfunction "AIN5_B8") (pintype "bidirectional"))
    )
    (net (code "270") (name "WLAN_IRQ") (class "Default")
      (node (ref "SIP") (pin "K16") (pinfunction "K16_K16") (pintype "bidirectional"))
      (node (ref "U2") (pin "4") (pinfunction "Y_4") (pintype "output"))
    )
    (net (code "271") (name "WL_BT_OE") (class "Default")
      (node (ref "R93") (pin "1") (pinfunction "1_1") (pintype "passive"))
      (node (ref "SIP") (pin "L18") (pinfunction "L18_L18") (pintype "bidirectional"))
    )
    (net (code "272") (name "WL_EN") (class "Default")
      (node (ref "SIP") (pin "K18") (pinfunction "K18_K18") (pintype "bidirectional"))
      (node (ref "U9") (pin "20") (pinfunction "B1_20") (pintype "bidirectional"))
    )
    (net (code "273") (name "WL_EN_1V8") (class "Default")
      (node (ref "R87") (pin "1") (pinfunction "1_1") (pintype "passive"))
      (node (ref "T1") (pin "G") (pinfunction "G_G") (pintype "bidirectional"))
      (node (ref "U7") (pin "40") (pinfunction "WLAN_EN_40") (pintype "bidirectional"))
      (node (ref "U9") (pin "1") (pinfunction "A1_1") (pintype "bidirectional"))
    )
    (net (code "274") (name "WL_IRQ") (class "Default")
      (node (ref "R84") (pin "1") (pinfunction "1_1") (pintype "passive"))
      (node (ref "U2") (pin "2") (pinfunction "A_2") (pintype "input"))
    )
    (net (code "275") (name "WL_SDIO_CLK") (class "Default")
      (node (ref "R103") (pin "2") (pinfunction "2_2") (pintype "passive"))
      (node (ref "R78") (pin "1") (pinfunction "1_1") (pintype "passive"))
      (node (ref "U9") (pin "8") (pinfunction "A7_8") (pintype "bidirectional"))
    )
    (net (code "276") (name "WL_SDIO_CMD") (class "Default")
      (node (ref "R105") (pin "2") (pinfunction "2_2") (pintype "passive"))
      (node (ref "R79") (pin "1") (pinfunction "1_1") (pintype "passive"))
      (node (ref "U9") (pin "9") (pinfunction "A8_9") (pintype "bidirectional"))
    )
    (net (code "277") (name "WL_SDIO_D0") (class "Default")
      (node (ref "R80") (pin "1") (pinfunction "1_1") (pintype "passive"))
      (node (ref "R98") (pin "2") (pinfunction "2_2") (pintype "passive"))
      (node (ref "U9") (pin "7") (pinfunction "A6_7") (pintype "bidirectional"))
    )
    (net (code "278") (name "WL_SDIO_D1") (class "Default")
      (node (ref "R81") (pin "1") (pinfunction "1_1") (pintype "passive"))
      (node (ref "R99") (pin "2") (pinfunction "2_2") (pintype "passive"))
      (node (ref "U9") (pin "6") (pinfunction "A5_6") (pintype "bidirectional"))
    )
    (net (code "279") (name "WL_SDIO_D2") (class "Default")
      (node (ref "R101") (pin "2") (pinfunction "2_2") (pintype "passive"))
      (node (ref "R82") (pin "1") (pinfunction "1_1") (pintype "passive"))
      (node (ref "U9") (pin "5") (pinfunction "A4_5") (pintype "bidirectional"))
    )
    (net (code "280") (name "WL_SDIO_D3") (class "Default")
      (node (ref "R102") (pin "2") (pinfunction "2_2") (pintype "passive"))
      (node (ref "R83") (pin "1") (pinfunction "1_1") (pintype "passive"))
      (node (ref "U9") (pin "4") (pinfunction "A3_4") (pintype "bidirectional"))
    )
    (net (code "281") (name "unconnected-(12V-PadOUT_CON)") (class "Default")
      (node (ref "12V") (pin "OUT_CON") (pinfunction "OUT_CON_OUT_CON") (pintype "bidirectional"))
    )
    (net (code "282") (name "unconnected-(CHGIC-ACOK-Pad12)") (class "Default")
      (node (ref "CHGIC") (pin "12") (pinfunction "ACOK_12") (pintype "bidirectional"))
    )
    (net (code "283") (name "unconnected-(CHGIC-CELL-Pad4)") (class "Default")
      (node (ref "CHGIC") (pin "4") (pinfunction "CELL_4") (pintype "bidirectional"))
    )
    (net (code "284") (name "unconnected-(CHGIC-SEL-Pad5)") (class "Default")
      (node (ref "CHGIC") (pin "5") (pinfunction "SEL_5") (pintype "bidirectional"))
    )
    (net (code "285") (name "unconnected-(FUD1-PadP$1)") (class "Default")
      (node (ref "FUD1") (pin "P$1") (pinfunction "P$1_P$1") (pintype "no_connect"))
    )
    (net (code "286") (name "unconnected-(FUD2-PadP$1)") (class "Default")
      (node (ref "FUD2") (pin "P$1") (pinfunction "P$1_P$1") (pintype "no_connect"))
    )
    (net (code "287") (name "unconnected-(FUD3-PadP$1)") (class "Default")
      (node (ref "FUD3") (pin "P$1") (pinfunction "P$1_P$1") (pintype "no_connect"))
    )
    (net (code "288") (name "unconnected-(FUD4-PadP$1)") (class "Default")
      (node (ref "FUD4") (pin "P$1") (pinfunction "P$1_P$1") (pintype "no_connect"))
    )
    (net (code "289") (name "unconnected-(FUD5-PadP$1)") (class "Default")
      (node (ref "FUD5") (pin "P$1") (pinfunction "P$1_P$1") (pintype "no_connect"))
    )
    (net (code "290") (name "unconnected-(FUD6-PadP$1)") (class "Default")
      (node (ref "FUD6") (pin "P$1") (pinfunction "P$1_P$1") (pintype "no_connect"))
    )
    (net (code "291") (name "unconnected-(GP1-PadSS1)") (class "Default")
      (node (ref "GP1") (pin "SS1") (pinfunction "SS1_SS1") (pintype "bidirectional"))
    )
    (net (code "292") (name "unconnected-(GP1-PadSS2)") (class "Default")
      (node (ref "GP1") (pin "SS2") (pinfunction "SS2_SS2") (pintype "bidirectional"))
    )
    (net (code "293") (name "unconnected-(GPS-Pad1)") (class "Default")
      (node (ref "GPS") (pin "1") (pinfunction "1_1") (pintype "bidirectional"))
    )
    (net (code "294") (name "unconnected-(I2C1-PadSS1)") (class "Default")
      (node (ref "I2C1") (pin "SS1") (pinfunction "SS1_SS1") (pintype "bidirectional"))
    )
    (net (code "295") (name "unconnected-(I2C1-PadSS2)") (class "Default")
      (node (ref "I2C1") (pin "SS2") (pinfunction "SS2_SS2") (pintype "bidirectional"))
    )
    (net (code "296") (name "unconnected-(IMU-AUX_CL-Pad7)") (class "Default")
      (node (ref "IMU") (pin "7") (pinfunction "AUX_CL_7") (pintype "bidirectional"))
    )
    (net (code "297") (name "unconnected-(IMU-AUX_DA-Pad21)") (class "Default")
      (node (ref "IMU") (pin "21") (pinfunction "AUX_DA_21") (pintype "bidirectional"))
    )
    (net (code "298") (name "unconnected-(IMU-FSYNC-Pad11)") (class "Default")
      (node (ref "IMU") (pin "11") (pinfunction "FSYNC_11") (pintype "bidirectional"))
    )
    (net (code "299") (name "unconnected-(IMU-NC-Pad2)") (class "Default")
      (node (ref "IMU") (pin "2") (pinfunction "NC_2") (pintype "bidirectional"))
    )
    (net (code "300") (name "unconnected-(IMU-NC-Pad3)") (class "Default")
      (node (ref "IMU") (pin "3") (pinfunction "NC_3") (pintype "bidirectional"))
    )
    (net (code "301") (name "unconnected-(IMU-NC-Pad4)") (class "Default")
      (node (ref "IMU") (pin "4") (pinfunction "NC_4") (pintype "bidirectional"))
    )
    (net (code "302") (name "unconnected-(IMU-NC-Pad5)") (class "Default")
      (node (ref "IMU") (pin "5") (pinfunction "NC_5") (pintype "bidirectional"))
    )
    (net (code "303") (name "unconnected-(IMU-NC-Pad6)") (class "Default")
      (node (ref "IMU") (pin "6") (pinfunction "NC_6") (pintype "bidirectional"))
    )
    (net (code "304") (name "unconnected-(IMU-NC-Pad14)") (class "Default")
      (node (ref "IMU") (pin "14") (pinfunction "NC_14") (pintype "bidirectional"))
    )
    (net (code "305") (name "unconnected-(IMU-NC-Pad15)") (class "Default")
      (node (ref "IMU") (pin "15") (pinfunction "NC_15") (pintype "bidirectional"))
    )
    (net (code "306") (name "unconnected-(IMU-NC-Pad16)") (class "Default")
      (node (ref "IMU") (pin "16") (pinfunction "NC_16") (pintype "bidirectional"))
    )
    (net (code "307") (name "unconnected-(IMU-NC-Pad17)") (class "Default")
      (node (ref "IMU") (pin "17") (pinfunction "NC_17") (pintype "bidirectional"))
    )
    (net (code "308") (name "unconnected-(IMU-RESV-Pad19)") (class "Default")
      (node (ref "IMU") (pin "19") (pinfunction "RESV_19") (pintype "bidirectional"))
    )
    (net (code "309") (name "unconnected-(PROT-CO-Pad3)") (class "Default")
      (node (ref "PROT") (pin "3") (pinfunction "CO_3") (pintype "bidirectional"))
    )
    (net (code "310") (name "unconnected-(PROT-DP-Pad4)") (class "Default")
      (node (ref "PROT") (pin "4") (pinfunction "DP_4") (pintype "bidirectional"))
    )
    (net (code "311") (name "unconnected-(SIP-PadH18)") (class "Default")
      (node (ref "SIP") (pin "H18") (pinfunction "H18_H18") (pintype "bidirectional"))
    )
    (net (code "312") (name "unconnected-(SIPA-BAT_TEMP-PadW1)") (class "Default")
      (node (ref "SIP") (pin "W1") (pinfunction "BAT_TEMP_W1") (pintype "bidirectional"))
    )
    (net (code "313") (name "unconnected-(SIPA-BAT_VOLT-PadY1)") (class "Default")
      (node (ref "SIP") (pin "Y1") (pinfunction "BAT_VOLT_Y1") (pintype "bidirectional"))
    )
    (net (code "314") (name "unconnected-(SIPA-L1_IN-PadY14)") (class "Default")
      (node (ref "SIP") (pin "Y14") (pinfunction "L1_IN_Y14") (pintype "bidirectional"))
    )
    (net (code "315") (name "unconnected-(SIPA-L2_IN-PadY17)") (class "Default")
      (node (ref "SIP") (pin "Y17") (pinfunction "L2_IN_Y17") (pintype "bidirectional"))
    )
    (net (code "316") (name "unconnected-(SIPA-L3_IN-PadY20)") (class "Default")
      (node (ref "SIP") (pin "Y20") (pinfunction "L3_IN_Y20") (pintype "bidirectional"))
    )
    (net (code "317") (name "unconnected-(SIPC-AIN4-PadC8)") (class "Default")
      (node (ref "SIP") (pin "C8") (pinfunction "AIN4_C8") (pintype "bidirectional"))
    )
    (net (code "318") (name "unconnected-(SIPC-USB0_CE-PadM15)") (class "Default")
      (node (ref "SIP") (pin "M15") (pinfunction "USB0_CE_M15") (pintype "bidirectional"))
    )
    (net (code "319") (name "unconnected-(SIPC-USB0_DRVVBUS-PadF16)") (class "Default")
      (node (ref "SIP") (pin "F16") (pinfunction "USB0_DRVVBUS_F16") (pintype "bidirectional"))
    )
    (net (code "320") (name "unconnected-(SIPC-USB1_CE-PadP18)") (class "Default")
      (node (ref "SIP") (pin "P18") (pinfunction "USB1_CE_P18") (pintype "bidirectional"))
    )
    (net (code "321") (name "unconnected-(SIPC-USB1_DRVVBUS-PadF15)") (class "Default")
      (node (ref "SIP") (pin "F15") (pinfunction "USB1_DRVVBUS_F15") (pintype "bidirectional"))
    )
    (net (code "322") (name "unconnected-(SIPD-NC1-PadV11)") (class "Default")
      (node (ref "SIP") (pin "V11") (pinfunction "NC1_V11") (pintype "bidirectional"))
    )
    (net (code "323") (name "unconnected-(SIPD-NC2-PadU11)") (class "Default")
      (node (ref "SIP") (pin "U11") (pinfunction "NC2_U11") (pintype "bidirectional"))
    )
    (net (code "324") (name "unconnected-(SIPD-NC3-PadV10)") (class "Default")
      (node (ref "SIP") (pin "V10") (pinfunction "NC3_V10") (pintype "bidirectional"))
    )
    (net (code "325") (name "unconnected-(SIPD-NC4-PadB1)") (class "Default")
      (node (ref "SIP") (pin "B1") (pinfunction "NC4_B1") (pintype "bidirectional"))
    )
    (net (code "326") (name "unconnected-(SIPD-NC5-PadB2)") (class "Default")
      (node (ref "SIP") (pin "B2") (pinfunction "NC5_B2") (pintype "bidirectional"))
    )
    (net (code "327") (name "unconnected-(SIPD-NC6-PadB3)") (class "Default")
      (node (ref "SIP") (pin "B3") (pinfunction "NC6_B3") (pintype "bidirectional"))
    )
    (net (code "328") (name "unconnected-(SIPD-NC12-PadC1)") (class "Default")
      (node (ref "SIP") (pin "C1") (pinfunction "NC12_C1") (pintype "bidirectional"))
    )
    (net (code "329") (name "unconnected-(SIPD-NC20-PadC2)") (class "Default")
      (node (ref "SIP") (pin "C2") (pinfunction "NC20_C2") (pintype "bidirectional"))
    )
    (net (code "330") (name "unconnected-(SIPD-NC21-PadC3)") (class "Default")
      (node (ref "SIP") (pin "C3") (pinfunction "NC21_C3") (pintype "bidirectional"))
    )
    (net (code "331") (name "unconnected-(SIPD-NC22-PadC4)") (class "Default")
      (node (ref "SIP") (pin "C4") (pinfunction "NC22_C4") (pintype "bidirectional"))
    )
    (net (code "332") (name "unconnected-(SIPD-NC23-PadP2)") (class "Default")
      (node (ref "SIP") (pin "P2") (pinfunction "NC23_P2") (pintype "bidirectional"))
    )
    (net (code "333") (name "unconnected-(SIPD-NC24-PadD1)") (class "Default")
      (node (ref "SIP") (pin "D1") (pinfunction "NC24_D1") (pintype "bidirectional"))
    )
    (net (code "334") (name "unconnected-(SIPD-NC31-PadD2)") (class "Default")
      (node (ref "SIP") (pin "D2") (pinfunction "NC31_D2") (pintype "bidirectional"))
    )
    (net (code "335") (name "unconnected-(SIPD-NC32-PadD3)") (class "Default")
      (node (ref "SIP") (pin "D3") (pinfunction "NC32_D3") (pintype "bidirectional"))
    )
    (net (code "336") (name "unconnected-(SIPD-NC33-PadD4)") (class "Default")
      (node (ref "SIP") (pin "D4") (pinfunction "NC33_D4") (pintype "bidirectional"))
    )
    (net (code "337") (name "unconnected-(SIPD-NC34-PadD5)") (class "Default")
      (node (ref "SIP") (pin "D5") (pinfunction "NC34_D5") (pintype "bidirectional"))
    )
    (net (code "338") (name "unconnected-(SIPD-NC45-PadP3)") (class "Default")
      (node (ref "SIP") (pin "P3") (pinfunction "NC45_P3") (pintype "bidirectional"))
    )
    (net (code "339") (name "unconnected-(SIPD-NC46-PadE1)") (class "Default")
      (node (ref "SIP") (pin "E1") (pinfunction "NC46_E1") (pintype "bidirectional"))
    )
    (net (code "340") (name "unconnected-(SIPD-NC47-PadE2)") (class "Default")
      (node (ref "SIP") (pin "E2") (pinfunction "NC47_E2") (pintype "bidirectional"))
    )
    (net (code "341") (name "unconnected-(SIPD-NC48-PadE3)") (class "Default")
      (node (ref "SIP") (pin "E3") (pinfunction "NC48_E3") (pintype "bidirectional"))
    )
    (net (code "342") (name "unconnected-(SIPD-NC58-PadE4)") (class "Default")
      (node (ref "SIP") (pin "E4") (pinfunction "NC58_E4") (pintype "bidirectional"))
    )
    (net (code "343") (name "unconnected-(SIPD-NC59-PadF1)") (class "Default")
      (node (ref "SIP") (pin "F1") (pinfunction "NC59_F1") (pintype "bidirectional"))
    )
    (net (code "344") (name "unconnected-(SIPD-NC60-PadF2)") (class "Default")
      (node (ref "SIP") (pin "F2") (pinfunction "NC60_F2") (pintype "bidirectional"))
    )
    (net (code "345") (name "unconnected-(SIPD-NC61-PadF3)") (class "Default")
      (node (ref "SIP") (pin "F3") (pinfunction "NC61_F3") (pintype "bidirectional"))
    )
    (net (code "346") (name "unconnected-(SIPD-NC68-PadF4)") (class "Default")
      (node (ref "SIP") (pin "F4") (pinfunction "NC68_F4") (pintype "bidirectional"))
    )
    (net (code "347") (name "unconnected-(SIPD-NC69-PadG1)") (class "Default")
      (node (ref "SIP") (pin "G1") (pinfunction "NC69_G1") (pintype "bidirectional"))
    )
    (net (code "348") (name "unconnected-(SIPD-NC70-PadG2)") (class "Default")
      (node (ref "SIP") (pin "G2") (pinfunction "NC70_G2") (pintype "bidirectional"))
    )
    (net (code "349") (name "unconnected-(SIPD-NC71-PadG3)") (class "Default")
      (node (ref "SIP") (pin "G3") (pinfunction "NC71_G3") (pintype "bidirectional"))
    )
    (net (code "350") (name "unconnected-(SIPD-NC76-PadG4)") (class "Default")
      (node (ref "SIP") (pin "G4") (pinfunction "NC76_G4") (pintype "bidirectional"))
    )
    (net (code "351") (name "unconnected-(SIPD-NC77-PadH1)") (class "Default")
      (node (ref "SIP") (pin "H1") (pinfunction "NC77_H1") (pintype "bidirectional"))
    )
    (net (code "352") (name "unconnected-(SIPD-NC78-PadH2)") (class "Default")
      (node (ref "SIP") (pin "H2") (pinfunction "NC78_H2") (pintype "bidirectional"))
    )
    (net (code "353") (name "unconnected-(SIPD-NC79-PadH3)") (class "Default")
      (node (ref "SIP") (pin "H3") (pinfunction "NC79_H3") (pintype "bidirectional"))
    )
    (net (code "354") (name "unconnected-(SIPD-NC84-PadH4)") (class "Default")
      (node (ref "SIP") (pin "H4") (pinfunction "NC84_H4") (pintype "bidirectional"))
    )
    (net (code "355") (name "unconnected-(SIPD-NC85-PadJ1)") (class "Default")
      (node (ref "SIP") (pin "J1") (pinfunction "NC85_J1") (pintype "bidirectional"))
    )
    (net (code "356") (name "unconnected-(SIPD-NC86-PadJ2)") (class "Default")
      (node (ref "SIP") (pin "J2") (pinfunction "NC86_J2") (pintype "bidirectional"))
    )
    (net (code "357") (name "unconnected-(SIPD-NC87-PadJ3)") (class "Default")
      (node (ref "SIP") (pin "J3") (pinfunction "NC87_J3") (pintype "bidirectional"))
    )
    (net (code "358") (name "unconnected-(SIPD-NC94-PadJ4)") (class "Default")
      (node (ref "SIP") (pin "J4") (pinfunction "NC94_J4") (pintype "bidirectional"))
    )
    (net (code "359") (name "unconnected-(SIPD-NC95-PadK1)") (class "Default")
      (node (ref "SIP") (pin "K1") (pinfunction "NC95_K1") (pintype "bidirectional"))
    )
    (net (code "360") (name "unconnected-(SIPD-NC96-PadK2)") (class "Default")
      (node (ref "SIP") (pin "K2") (pinfunction "NC96_K2") (pintype "bidirectional"))
    )
    (net (code "361") (name "unconnected-(SIPD-NC97-PadK3)") (class "Default")
      (node (ref "SIP") (pin "K3") (pinfunction "NC97_K3") (pintype "bidirectional"))
    )
    (net (code "362") (name "unconnected-(SIPD-NC104-PadK4)") (class "Default")
      (node (ref "SIP") (pin "K4") (pinfunction "NC104_K4") (pintype "bidirectional"))
    )
    (net (code "363") (name "unconnected-(SIPD-NC105-PadL1)") (class "Default")
      (node (ref "SIP") (pin "L1") (pinfunction "NC105_L1") (pintype "bidirectional"))
    )
    (net (code "364") (name "unconnected-(SIPD-NC106-PadL2)") (class "Default")
      (node (ref "SIP") (pin "L2") (pinfunction "NC106_L2") (pintype "bidirectional"))
    )
    (net (code "365") (name "unconnected-(SIPD-NC107-PadL3)") (class "Default")
      (node (ref "SIP") (pin "L3") (pinfunction "NC107_L3") (pintype "bidirectional"))
    )
    (net (code "366") (name "unconnected-(SIPD-NC111-PadL4)") (class "Default")
      (node (ref "SIP") (pin "L4") (pinfunction "NC111_L4") (pintype "bidirectional"))
    )
    (net (code "367") (name "unconnected-(SIPD-NC112-PadM1)") (class "Default")
      (node (ref "SIP") (pin "M1") (pinfunction "NC112_M1") (pintype "bidirectional"))
    )
    (net (code "368") (name "unconnected-(SIPD-NC113-PadM2)") (class "Default")
      (node (ref "SIP") (pin "M2") (pinfunction "NC113_M2") (pintype "bidirectional"))
    )
    (net (code "369") (name "unconnected-(SIPD-NC114-PadM3)") (class "Default")
      (node (ref "SIP") (pin "M3") (pinfunction "NC114_M3") (pintype "bidirectional"))
    )
    (net (code "370") (name "unconnected-(SIPD-NC121-PadM4)") (class "Default")
      (node (ref "SIP") (pin "M4") (pinfunction "NC121_M4") (pintype "bidirectional"))
    )
    (net (code "371") (name "unconnected-(SIPD-NC122-PadP4)") (class "Default")
      (node (ref "SIP") (pin "P4") (pinfunction "NC122_P4") (pintype "bidirectional"))
    )
    (net (code "372") (name "unconnected-(SIPD-NC123-PadN1)") (class "Default")
      (node (ref "SIP") (pin "N1") (pinfunction "NC123_N1") (pintype "bidirectional"))
    )
    (net (code "373") (name "unconnected-(SIPD-NC124-PadN2)") (class "Default")
      (node (ref "SIP") (pin "N2") (pinfunction "NC124_N2") (pintype "bidirectional"))
    )
    (net (code "374") (name "unconnected-(SIPD-NC136-PadN3)") (class "Default")
      (node (ref "SIP") (pin "N3") (pinfunction "NC136_N3") (pintype "bidirectional"))
    )
    (net (code "375") (name "unconnected-(SIPD-NC137-PadN4)") (class "Default")
      (node (ref "SIP") (pin "N4") (pinfunction "NC137_N4") (pintype "bidirectional"))
    )
    (net (code "376") (name "unconnected-(SIPD-NC138-PadP1)") (class "Default")
      (node (ref "SIP") (pin "P1") (pinfunction "NC138_P1") (pintype "bidirectional"))
    )
    (net (code "377") (name "unconnected-(SIPE-CAP_VBB_MPU-PadC10)") (class "Default")
      (node (ref "SIP") (pin "C10") (pinfunction "CAP_VBB_MPU_C10") (pintype "bidirectional"))
    )
    (net (code "378") (name "unconnected-(SIPE-CAP_VDD_RTC-PadD6)") (class "Default")
      (node (ref "SIP") (pin "D6") (pinfunction "CAP_VDD_RTC_D6") (pintype "bidirectional"))
    )
    (net (code "379") (name "unconnected-(SIPE-CAP_VDD_SRAM_COR-PadD9)") (class "Default")
      (node (ref "SIP") (pin "D9") (pinfunction "CAP_VDD_SRAM_COR_D9") (pintype "bidirectional"))
    )
    (net (code "380") (name "unconnected-(SIPE-CAP_VDD_SRAM_MPU-PadD11)") (class "Default")
      (node (ref "SIP") (pin "D11") (pinfunction "CAP_VDD_SRAM_MPU_D11") (pintype "bidirectional"))
    )
    (net (code "381") (name "unconnected-(SIPE-TESTOUT-PadA3)") (class "Default")
      (node (ref "SIP") (pin "A3") (pinfunction "TESTOUT_A3") (pintype "bidirectional"))
    )
    (net (code "382") (name "unconnected-(SIPE-VDDS_DDR2-PadF5)") (class "Default")
      (node (ref "SIP") (pin "F5") (pinfunction "VDDS_DDR2_F5") (pintype "bidirectional"))
    )
    (net (code "383") (name "unconnected-(SIPE-VDDS_DDR3-PadG5)") (class "Default")
      (node (ref "SIP") (pin "G5") (pinfunction "VDDS_DDR3_G5") (pintype "bidirectional"))
    )
    (net (code "384") (name "unconnected-(SIPE-VDDS_DDR4-PadH5)") (class "Default")
      (node (ref "SIP") (pin "H5") (pinfunction "VDDS_DDR4_H5") (pintype "bidirectional"))
    )
    (net (code "385") (name "unconnected-(SIPE-VDDS_DDR5-PadJ5)") (class "Default")
      (node (ref "SIP") (pin "J5") (pinfunction "VDDS_DDR5_J5") (pintype "bidirectional"))
    )
    (net (code "386") (name "unconnected-(SIPE-VDDS_DDR6-PadK5)") (class "Default")
      (node (ref "SIP") (pin "K5") (pinfunction "VDDS_DDR6_K5") (pintype "bidirectional"))
    )
    (net (code "387") (name "unconnected-(SIPE-VDDS_DDR7-PadL5)") (class "Default")
      (node (ref "SIP") (pin "L5") (pinfunction "VDDS_DDR7_L5") (pintype "bidirectional"))
    )
    (net (code "388") (name "unconnected-(SIPE-VDD_3V3A1-PadE10)") (class "Default")
      (node (ref "SIP") (pin "E10") (pinfunction "VDD_3V3A1_E10") (pintype "bidirectional"))
    )
    (net (code "389") (name "unconnected-(SIPE-VDD_3V3A2-PadE11)") (class "Default")
      (node (ref "SIP") (pin "E11") (pinfunction "VDD_3V3A2_E11") (pintype "bidirectional"))
    )
    (net (code "390") (name "unconnected-(SIPE-VDD_3V3A3-PadE12)") (class "Default")
      (node (ref "SIP") (pin "E12") (pinfunction "VDD_3V3A3_E12") (pintype "bidirectional"))
    )
    (net (code "391") (name "unconnected-(SIPE-VDD_3V3A4-PadE13)") (class "Default")
      (node (ref "SIP") (pin "E13") (pinfunction "VDD_3V3A4_E13") (pintype "bidirectional"))
    )
    (net (code "392") (name "unconnected-(SIPE-VDD_3V3A5-PadF14)") (class "Default")
      (node (ref "SIP") (pin "F14") (pinfunction "VDD_3V3A5_F14") (pintype "bidirectional"))
    )
    (net (code "393") (name "unconnected-(SIPE-VDD_3V3A6-PadG14)") (class "Default")
      (node (ref "SIP") (pin "G14") (pinfunction "VDD_3V3A6_G14") (pintype "bidirectional"))
    )
    (net (code "394") (name "unconnected-(SIPE-VDD_3V3A7-PadH14)") (class "Default")
      (node (ref "SIP") (pin "H14") (pinfunction "VDD_3V3A7_H14") (pintype "bidirectional"))
    )
    (net (code "395") (name "unconnected-(SIPE-VDD_3V3A8-PadJ14)") (class "Default")
      (node (ref "SIP") (pin "J14") (pinfunction "VDD_3V3A8_J14") (pintype "bidirectional"))
    )
    (net (code "396") (name "unconnected-(SIPE-VDD_3V3A9-PadK14)") (class "Default")
      (node (ref "SIP") (pin "K14") (pinfunction "VDD_3V3A9_K14") (pintype "bidirectional"))
    )
    (net (code "397") (name "unconnected-(SIPE-VDD_3V3A10-PadL14)") (class "Default")
      (node (ref "SIP") (pin "L14") (pinfunction "VDD_3V3A10_L14") (pintype "bidirectional"))
    )
    (net (code "398") (name "unconnected-(SIPE-VDD_3V3A11-PadN5)") (class "Default")
      (node (ref "SIP") (pin "N5") (pinfunction "VDD_3V3A11_N5") (pintype "bidirectional"))
    )
    (net (code "399") (name "unconnected-(SIPE-VDD_3V3A13-PadP5)") (class "Default")
      (node (ref "SIP") (pin "P5") (pinfunction "VDD_3V3A13_P5") (pintype "bidirectional"))
    )
    (net (code "400") (name "unconnected-(SIPE-VDD_3V3A14-PadP6)") (class "Default")
      (node (ref "SIP") (pin "P6") (pinfunction "VDD_3V3A14_P6") (pintype "bidirectional"))
    )
    (net (code "401") (name "unconnected-(SIPE-VDD_3V3A15-PadP7)") (class "Default")
      (node (ref "SIP") (pin "P7") (pinfunction "VDD_3V3A15_P7") (pintype "bidirectional"))
    )
    (net (code "402") (name "unconnected-(SIPE-VDD_3V3A16-PadP8)") (class "Default")
      (node (ref "SIP") (pin "P8") (pinfunction "VDD_3V3A16_P8") (pintype "bidirectional"))
    )
    (net (code "403") (name "unconnected-(SIPE-VDD_3V3A17-PadP10)") (class "Default")
      (node (ref "SIP") (pin "P10") (pinfunction "VDD_3V3A17_P10") (pintype "bidirectional"))
    )
    (net (code "404") (name "unconnected-(SIPE-VDD_3V3A18-PadP11)") (class "Default")
      (node (ref "SIP") (pin "P11") (pinfunction "VDD_3V3A18_P11") (pintype "bidirectional"))
    )
    (net (code "405") (name "unconnected-(SIPE-VDD_3V3A19-PadP12)") (class "Default")
      (node (ref "SIP") (pin "P12") (pinfunction "VDD_3V3A19_P12") (pintype "bidirectional"))
    )
    (net (code "406") (name "unconnected-(SIPE-VDD_3V3A20-PadP13)") (class "Default")
      (node (ref "SIP") (pin "P13") (pinfunction "VDD_3V3A20_P13") (pintype "bidirectional"))
    )
    (net (code "407") (name "unconnected-(SIPE-VDD_3V3A21-PadR15)") (class "Default")
      (node (ref "SIP") (pin "R15") (pinfunction "VDD_3V3A21_R15") (pintype "bidirectional"))
    )
    (net (code "408") (name "unconnected-(SIPE-VDD_CORE1-PadF6)") (class "Default")
      (node (ref "SIP") (pin "F6") (pinfunction "VDD_CORE1_F6") (pintype "bidirectional"))
    )
    (net (code "409") (name "unconnected-(SIPE-VDD_CORE2-PadF7)") (class "Default")
      (node (ref "SIP") (pin "F7") (pinfunction "VDD_CORE2_F7") (pintype "bidirectional"))
    )
    (net (code "410") (name "unconnected-(SIPE-VDD_CORE3-PadG6)") (class "Default")
      (node (ref "SIP") (pin "G6") (pinfunction "VDD_CORE3_G6") (pintype "bidirectional"))
    )
    (net (code "411") (name "unconnected-(SIPE-VDD_CORE4-PadG7)") (class "Default")
      (node (ref "SIP") (pin "G7") (pinfunction "VDD_CORE4_G7") (pintype "bidirectional"))
    )
    (net (code "412") (name "unconnected-(SIPE-VDD_CORE5-PadG10)") (class "Default")
      (node (ref "SIP") (pin "G10") (pinfunction "VDD_CORE5_G10") (pintype "bidirectional"))
    )
    (net (code "413") (name "unconnected-(SIPE-VDD_CORE6-PadH11)") (class "Default")
      (node (ref "SIP") (pin "H11") (pinfunction "VDD_CORE6_H11") (pintype "bidirectional"))
    )
    (net (code "414") (name "unconnected-(SIPE-VDD_CORE7-PadJ12)") (class "Default")
      (node (ref "SIP") (pin "J12") (pinfunction "VDD_CORE7_J12") (pintype "bidirectional"))
    )
    (net (code "415") (name "unconnected-(SIPE-VDD_CORE8-PadK6)") (class "Default")
      (node (ref "SIP") (pin "K6") (pinfunction "VDD_CORE8_K6") (pintype "bidirectional"))
    )
    (net (code "416") (name "unconnected-(SIPE-VDD_CORE9-PadK8)") (class "Default")
      (node (ref "SIP") (pin "K8") (pinfunction "VDD_CORE9_K8") (pintype "bidirectional"))
    )
    (net (code "417") (name "unconnected-(SIPE-VDD_CORE10-PadK12)") (class "Default")
      (node (ref "SIP") (pin "K12") (pinfunction "VDD_CORE10_K12") (pintype "bidirectional"))
    )
    (net (code "418") (name "unconnected-(SIPE-VDD_CORE11-PadL6)") (class "Default")
      (node (ref "SIP") (pin "L6") (pinfunction "VDD_CORE11_L6") (pintype "bidirectional"))
    )
    (net (code "419") (name "unconnected-(SIPE-VDD_CORE12-PadL7)") (class "Default")
      (node (ref "SIP") (pin "L7") (pinfunction "VDD_CORE12_L7") (pintype "bidirectional"))
    )
    (net (code "420") (name "unconnected-(SIPE-VDD_CORE13-PadL8)") (class "Default")
      (node (ref "SIP") (pin "L8") (pinfunction "VDD_CORE13_L8") (pintype "bidirectional"))
    )
    (net (code "421") (name "unconnected-(SIPE-VDD_CORE14-PadL9)") (class "Default")
      (node (ref "SIP") (pin "L9") (pinfunction "VDD_CORE14_L9") (pintype "bidirectional"))
    )
    (net (code "422") (name "unconnected-(SIPE-VDD_CORE15-PadM11)") (class "Default")
      (node (ref "SIP") (pin "M11") (pinfunction "VDD_CORE15_M11") (pintype "bidirectional"))
    )
    (net (code "423") (name "unconnected-(SIPE-VDD_CORE16-PadM13)") (class "Default")
      (node (ref "SIP") (pin "M13") (pinfunction "VDD_CORE16_M13") (pintype "bidirectional"))
    )
    (net (code "424") (name "unconnected-(SIPE-VDD_CORE17-PadN8)") (class "Default")
      (node (ref "SIP") (pin "N8") (pinfunction "VDD_CORE17_N8") (pintype "bidirectional"))
    )
    (net (code "425") (name "unconnected-(SIPE-VDD_CORE18-PadN9)") (class "Default")
      (node (ref "SIP") (pin "N9") (pinfunction "VDD_CORE18_N9") (pintype "bidirectional"))
    )
    (net (code "426") (name "unconnected-(SIPE-VDD_CORE19-PadN12)") (class "Default")
      (node (ref "SIP") (pin "N12") (pinfunction "VDD_CORE19_N12") (pintype "bidirectional"))
    )
    (net (code "427") (name "unconnected-(SIPE-VDD_MPU0-PadF10)") (class "Default")
      (node (ref "SIP") (pin "F10") (pinfunction "VDD_MPU0_F10") (pintype "bidirectional"))
    )
    (net (code "428") (name "unconnected-(SIPE-VDD_MPU1-PadF11)") (class "Default")
      (node (ref "SIP") (pin "F11") (pinfunction "VDD_MPU1_F11") (pintype "bidirectional"))
    )
    (net (code "429") (name "unconnected-(SIPE-VDD_MPU2-PadF12)") (class "Default")
      (node (ref "SIP") (pin "F12") (pinfunction "VDD_MPU2_F12") (pintype "bidirectional"))
    )
    (net (code "430") (name "unconnected-(SIPE-VDD_MPU3-PadF13)") (class "Default")
      (node (ref "SIP") (pin "F13") (pinfunction "VDD_MPU3_F13") (pintype "bidirectional"))
    )
    (net (code "431") (name "unconnected-(SIPE-VDD_MPU4-PadG13)") (class "Default")
      (node (ref "SIP") (pin "G13") (pinfunction "VDD_MPU4_G13") (pintype "bidirectional"))
    )
    (net (code "432") (name "unconnected-(SIPE-VDD_MPU5-PadH13)") (class "Default")
      (node (ref "SIP") (pin "H13") (pinfunction "VDD_MPU5_H13") (pintype "bidirectional"))
    )
    (net (code "433") (name "unconnected-(SIPE-VDD_MPU_MON-PadA2)") (class "Default")
      (node (ref "SIP") (pin "A2") (pinfunction "VDD_MPU_MON_A2") (pintype "bidirectional"))
    )
    (net (code "434") (name "unconnected-(SIPE-VDD_PLL1-PadE7)") (class "Default")
      (node (ref "SIP") (pin "E7") (pinfunction "VDD_PLL1_E7") (pintype "bidirectional"))
    )
    (net (code "435") (name "unconnected-(SIPE-VDD_PLL3-PadR10)") (class "Default")
      (node (ref "SIP") (pin "R10") (pinfunction "VDD_PLL3_R10") (pintype "bidirectional"))
    )
    (net (code "436") (name "unconnected-(SIPE-VDD_PLL4-PadR11)") (class "Default")
      (node (ref "SIP") (pin "R11") (pinfunction "VDD_PLL4_R11") (pintype "bidirectional"))
    )
    (net (code "437") (name "unconnected-(SIPE-VDD_RTC1-PadD7)") (class "Default")
      (node (ref "SIP") (pin "D7") (pinfunction "VDD_RTC1_D7") (pintype "bidirectional"))
    )
    (net (code "438") (name "unconnected-(SIPE-VDD_RTC2-PadE6)") (class "Default")
      (node (ref "SIP") (pin "E6") (pinfunction "VDD_RTC2_E6") (pintype "bidirectional"))
    )
    (net (code "439") (name "unconnected-(SIPE-VDD_RTC4-PadF9)") (class "Default")
      (node (ref "SIP") (pin "F9") (pinfunction "VDD_RTC4_F9") (pintype "bidirectional"))
    )
    (net (code "440") (name "unconnected-(SIPE-VDD_RTC5-PadK13)") (class "Default")
      (node (ref "SIP") (pin "K13") (pinfunction "VDD_RTC5_K13") (pintype "bidirectional"))
    )
    (net (code "441") (name "unconnected-(SIPE-VDD_RTC6-PadN6)") (class "Default")
      (node (ref "SIP") (pin "N6") (pinfunction "VDD_RTC6_N6") (pintype "bidirectional"))
    )
    (net (code "442") (name "unconnected-(SIPE-VDD_RTC7-PadP9)") (class "Default")
      (node (ref "SIP") (pin "P9") (pinfunction "VDD_RTC7_P9") (pintype "bidirectional"))
    )
    (net (code "443") (name "unconnected-(SIPE-VDD_RTC8-PadP14)") (class "Default")
      (node (ref "SIP") (pin "P14") (pinfunction "VDD_RTC8_P14") (pintype "bidirectional"))
    )
    (net (code "444") (name "unconnected-(SIPE-VPP-PadM5)") (class "Default")
      (node (ref "SIP") (pin "M5") (pinfunction "VPP_M5") (pintype "bidirectional"))
    )
    (net (code "445") (name "unconnected-(U3-NC-Pad5)") (class "Default")
      (node (ref "U3") (pin "5") (pinfunction "NC_5") (pintype "bidirectional"))
    )
    (net (code "446") (name "unconnected-(U4-ID-Pad3)") (class "Default")
      (node (ref "U4") (pin "3") (pinfunction "ID_3") (pintype "bidirectional"))
    )
    (net (code "447") (name "unconnected-(U4-NC-Pad5)") (class "Default")
      (node (ref "U4") (pin "5") (pinfunction "NC_5") (pintype "bidirectional"))
    )
    (net (code "448") (name "unconnected-(U6-NC-Pad1)") (class "Default")
      (node (ref "U6") (pin "1") (pinfunction "NC_1") (pintype "passive"))
    )
    (net (code "449") (name "unconnected-(U7-BT_UART_DBG-Pad43)") (class "Default")
      (node (ref "U7") (pin "43") (pinfunction "BT_UART_DBG_43") (pintype "bidirectional"))
    )
    (net (code "450") (name "unconnected-(U7-GPIO1-Pad27)") (class "Default")
      (node (ref "U7") (pin "27") (pinfunction "GPIO1_27") (pintype "bidirectional"))
    )
    (net (code "451") (name "unconnected-(U7-GPIO2-Pad26)") (class "Default")
      (node (ref "U7") (pin "26") (pinfunction "GPIO2_26") (pintype "bidirectional"))
    )
    (net (code "452") (name "unconnected-(U7-GPIO4-Pad25)") (class "Default")
      (node (ref "U7") (pin "25") (pinfunction "GPIO4_25") (pintype "bidirectional"))
    )
    (net (code "453") (name "unconnected-(U7-GPIO9-Pad3)") (class "Default")
      (node (ref "U7") (pin "3") (pinfunction "GPIO9_3") (pintype "bidirectional"))
    )
    (net (code "454") (name "unconnected-(U7-GPIO10-Pad4)") (class "Default")
      (node (ref "U7") (pin "4") (pinfunction "GPIO10_4") (pintype "bidirectional"))
    )
    (net (code "455") (name "unconnected-(U7-GPIO11-Pad2)") (class "Default")
      (node (ref "U7") (pin "2") (pinfunction "GPIO11_2") (pintype "bidirectional"))
    )
    (net (code "456") (name "unconnected-(U7-GPIO12-Pad5)") (class "Default")
      (node (ref "U7") (pin "5") (pinfunction "GPIO12_5") (pintype "bidirectional"))
    )
    (net (code "457") (name "unconnected-(U7-RESERVED1-Pad21)") (class "Default")
      (node (ref "U7") (pin "21") (pinfunction "RESERVED1_21") (pintype "bidirectional"))
    )
    (net (code "458") (name "unconnected-(U7-RESERVED2-Pad22)") (class "Default")
      (node (ref "U7") (pin "22") (pinfunction "RESERVED2_22") (pintype "bidirectional"))
    )
    (net (code "459") (name "unconnected-(U7-RESERVED3-Pad62)") (class "Default")
      (node (ref "U7") (pin "62") (pinfunction "RESERVED3_62") (pintype "bidirectional"))
    )
    (net (code "460") (name "unconnected-(U7-WL_UART_DBG-Pad42)") (class "Default")
      (node (ref "U7") (pin "42") (pinfunction "WL_UART_DBG_42") (pintype "bidirectional"))
    )
    (net (code "461") (name "unconnected-(UT5-PadSS1)") (class "Default")
      (node (ref "UT5") (pin "SS1") (pinfunction "SS1_SS1") (pintype "bidirectional"))
    )
    (net (code "462") (name "unconnected-(UT5-PadSS2)") (class "Default")
      (node (ref "UT5") (pin "SS2") (pinfunction "SS2_SS2") (pintype "bidirectional"))
    )
  )
)
